# artemis_board.net
KiCad netlist of a schematic drawn in EAGLE
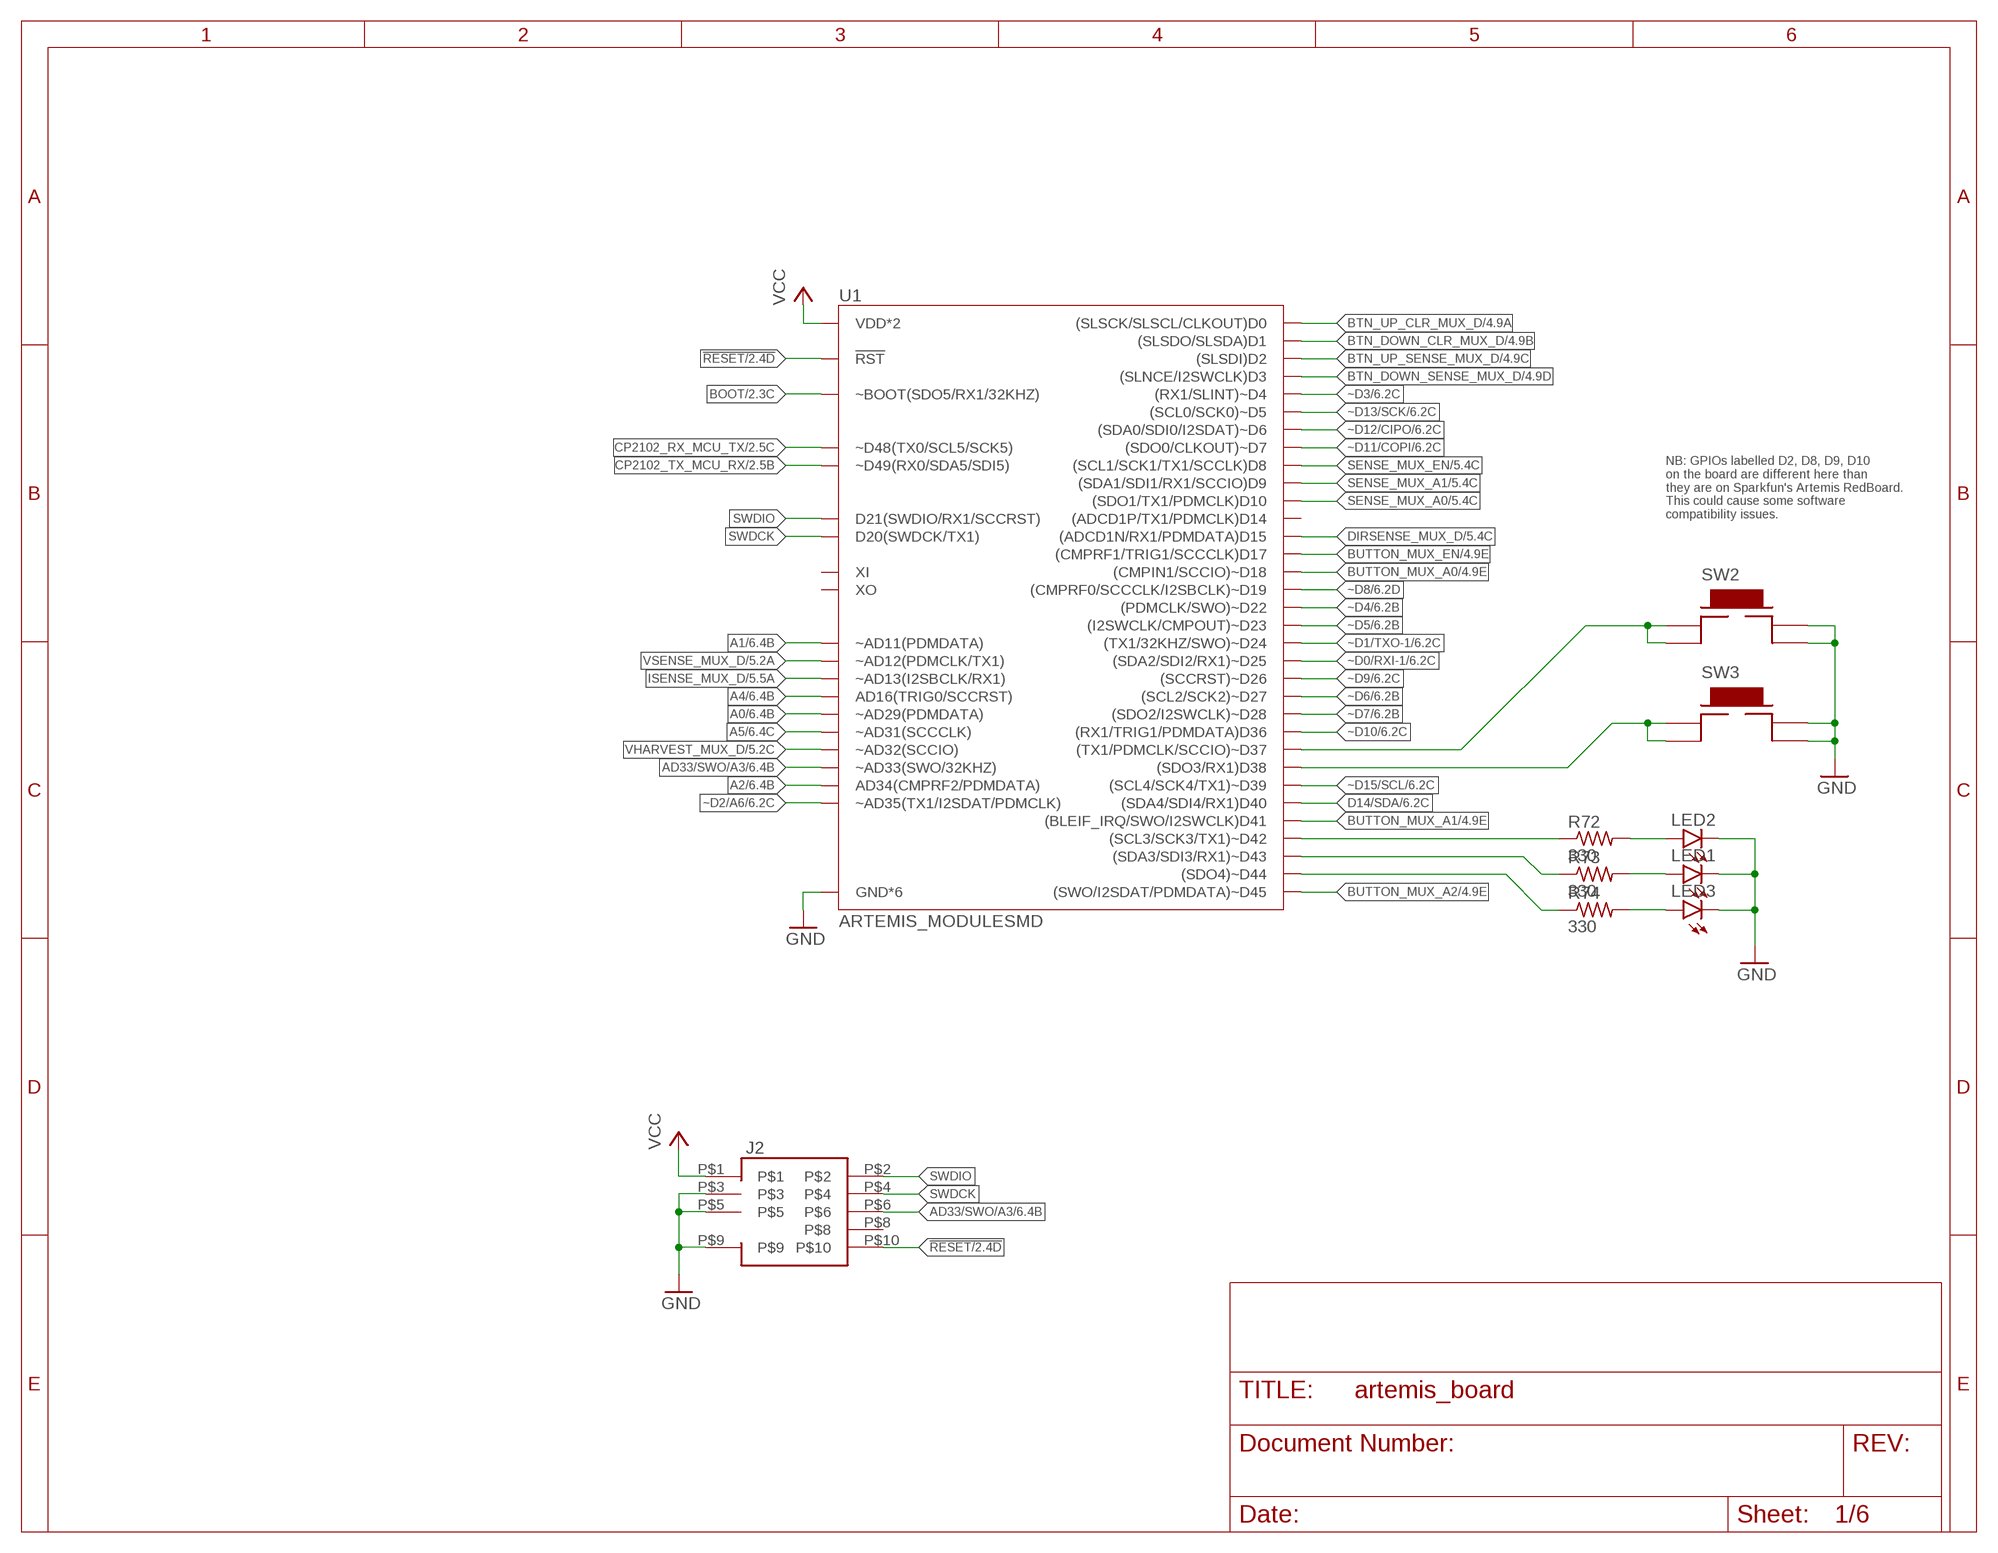
[diagram p0: schematic, sheet 1]
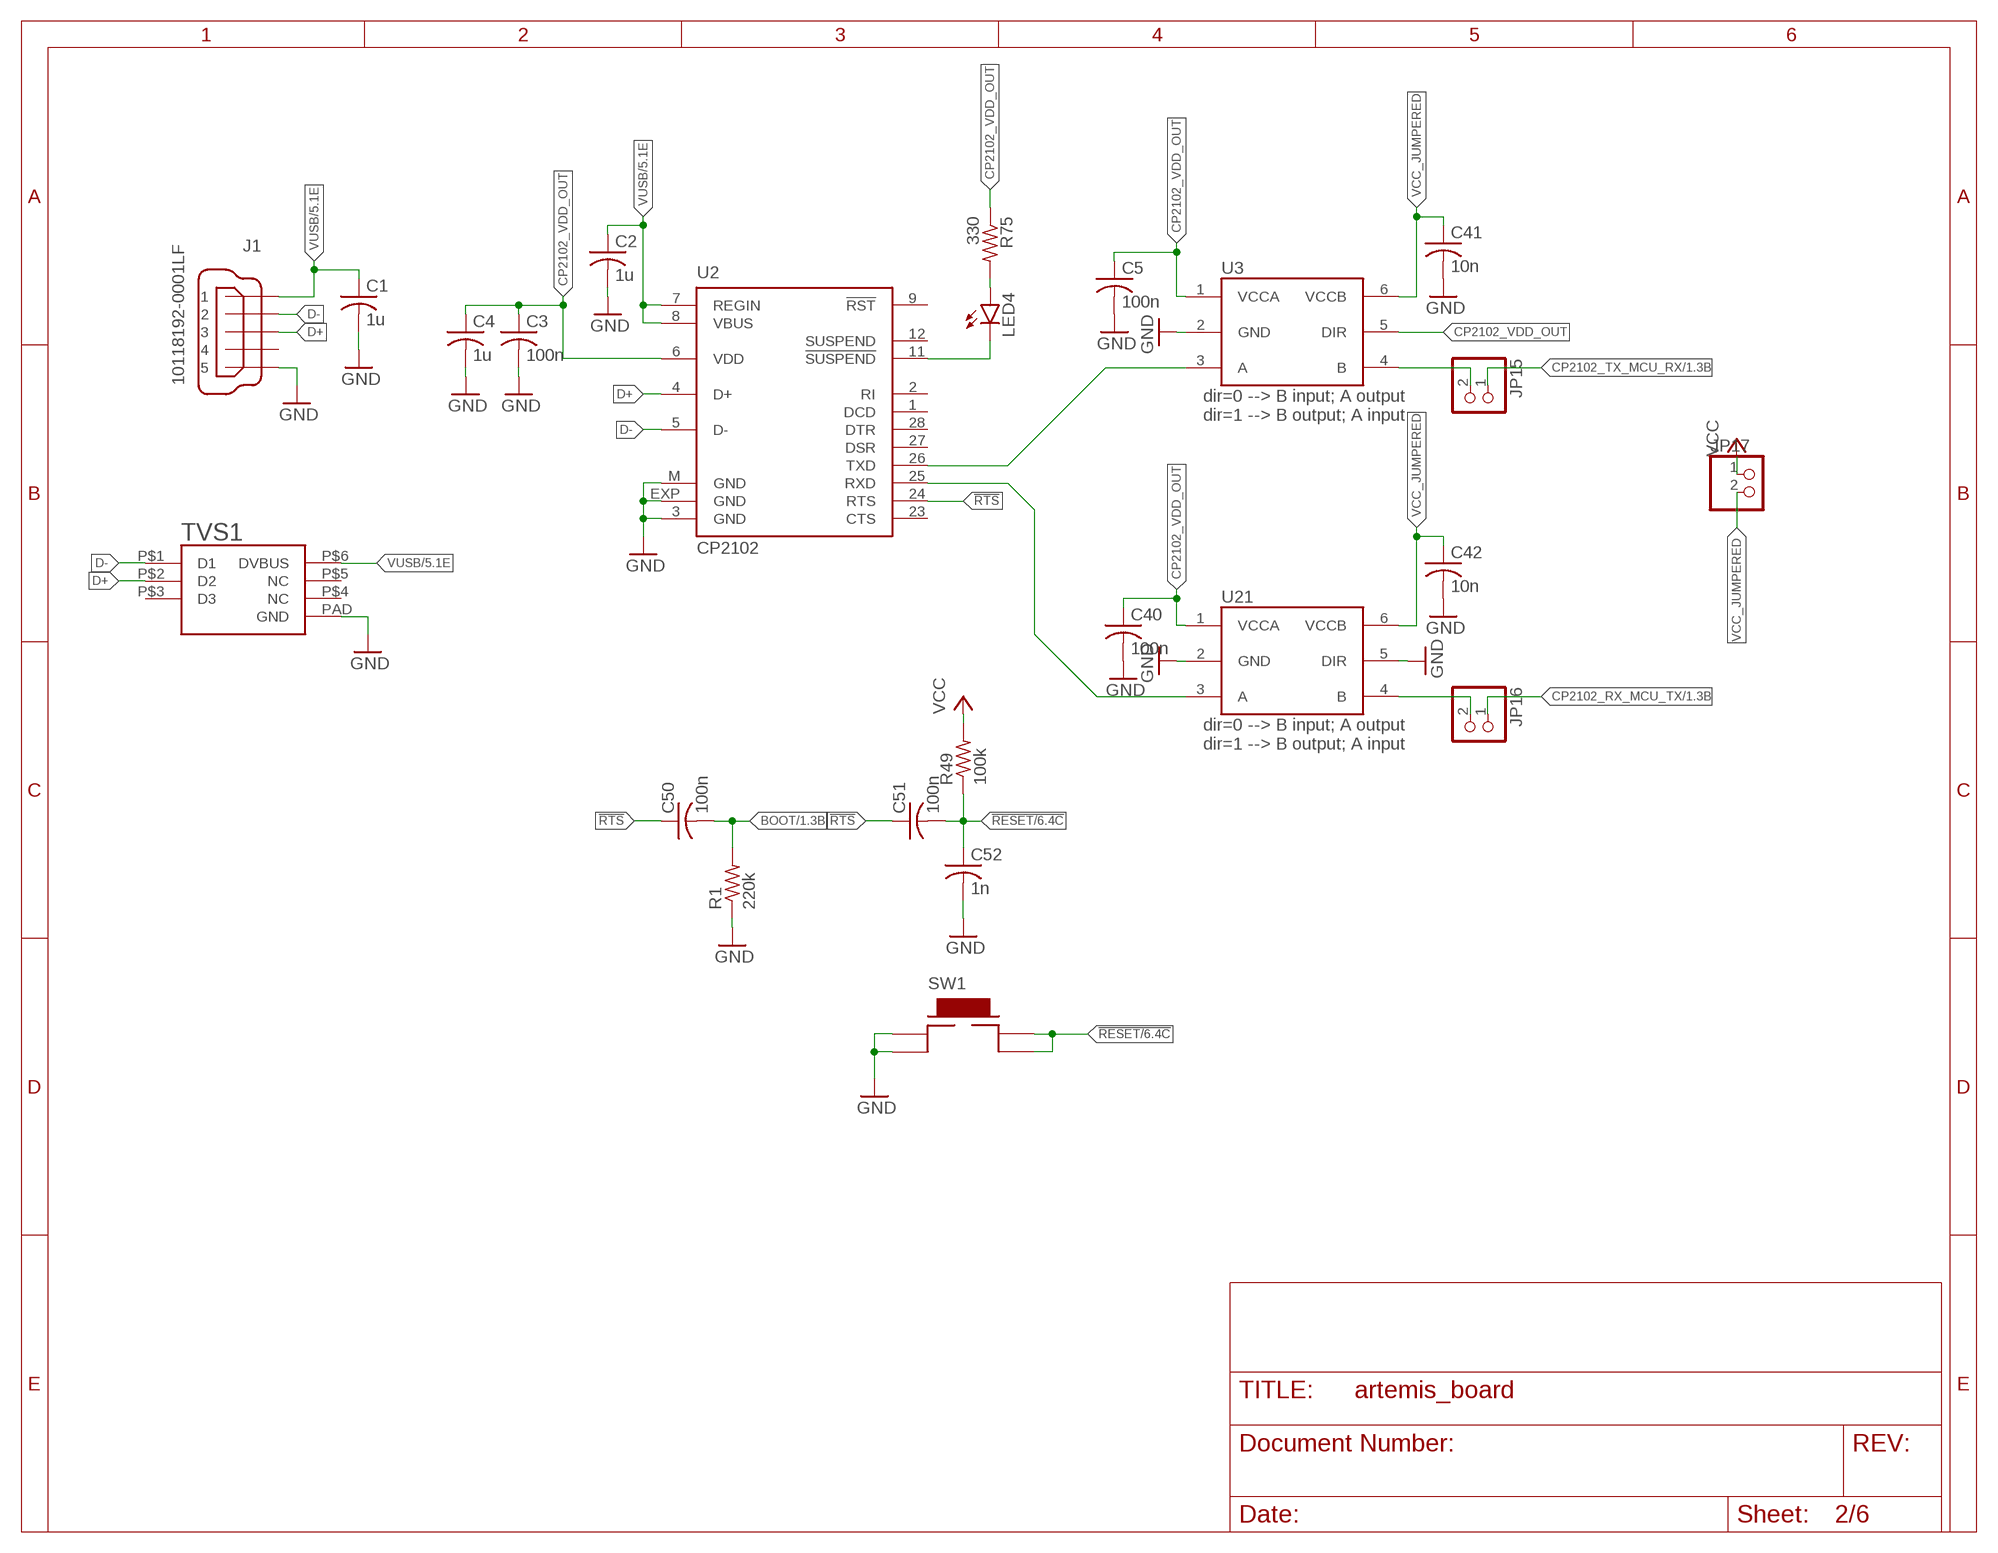
[diagram p1: schematic, sheet 2]
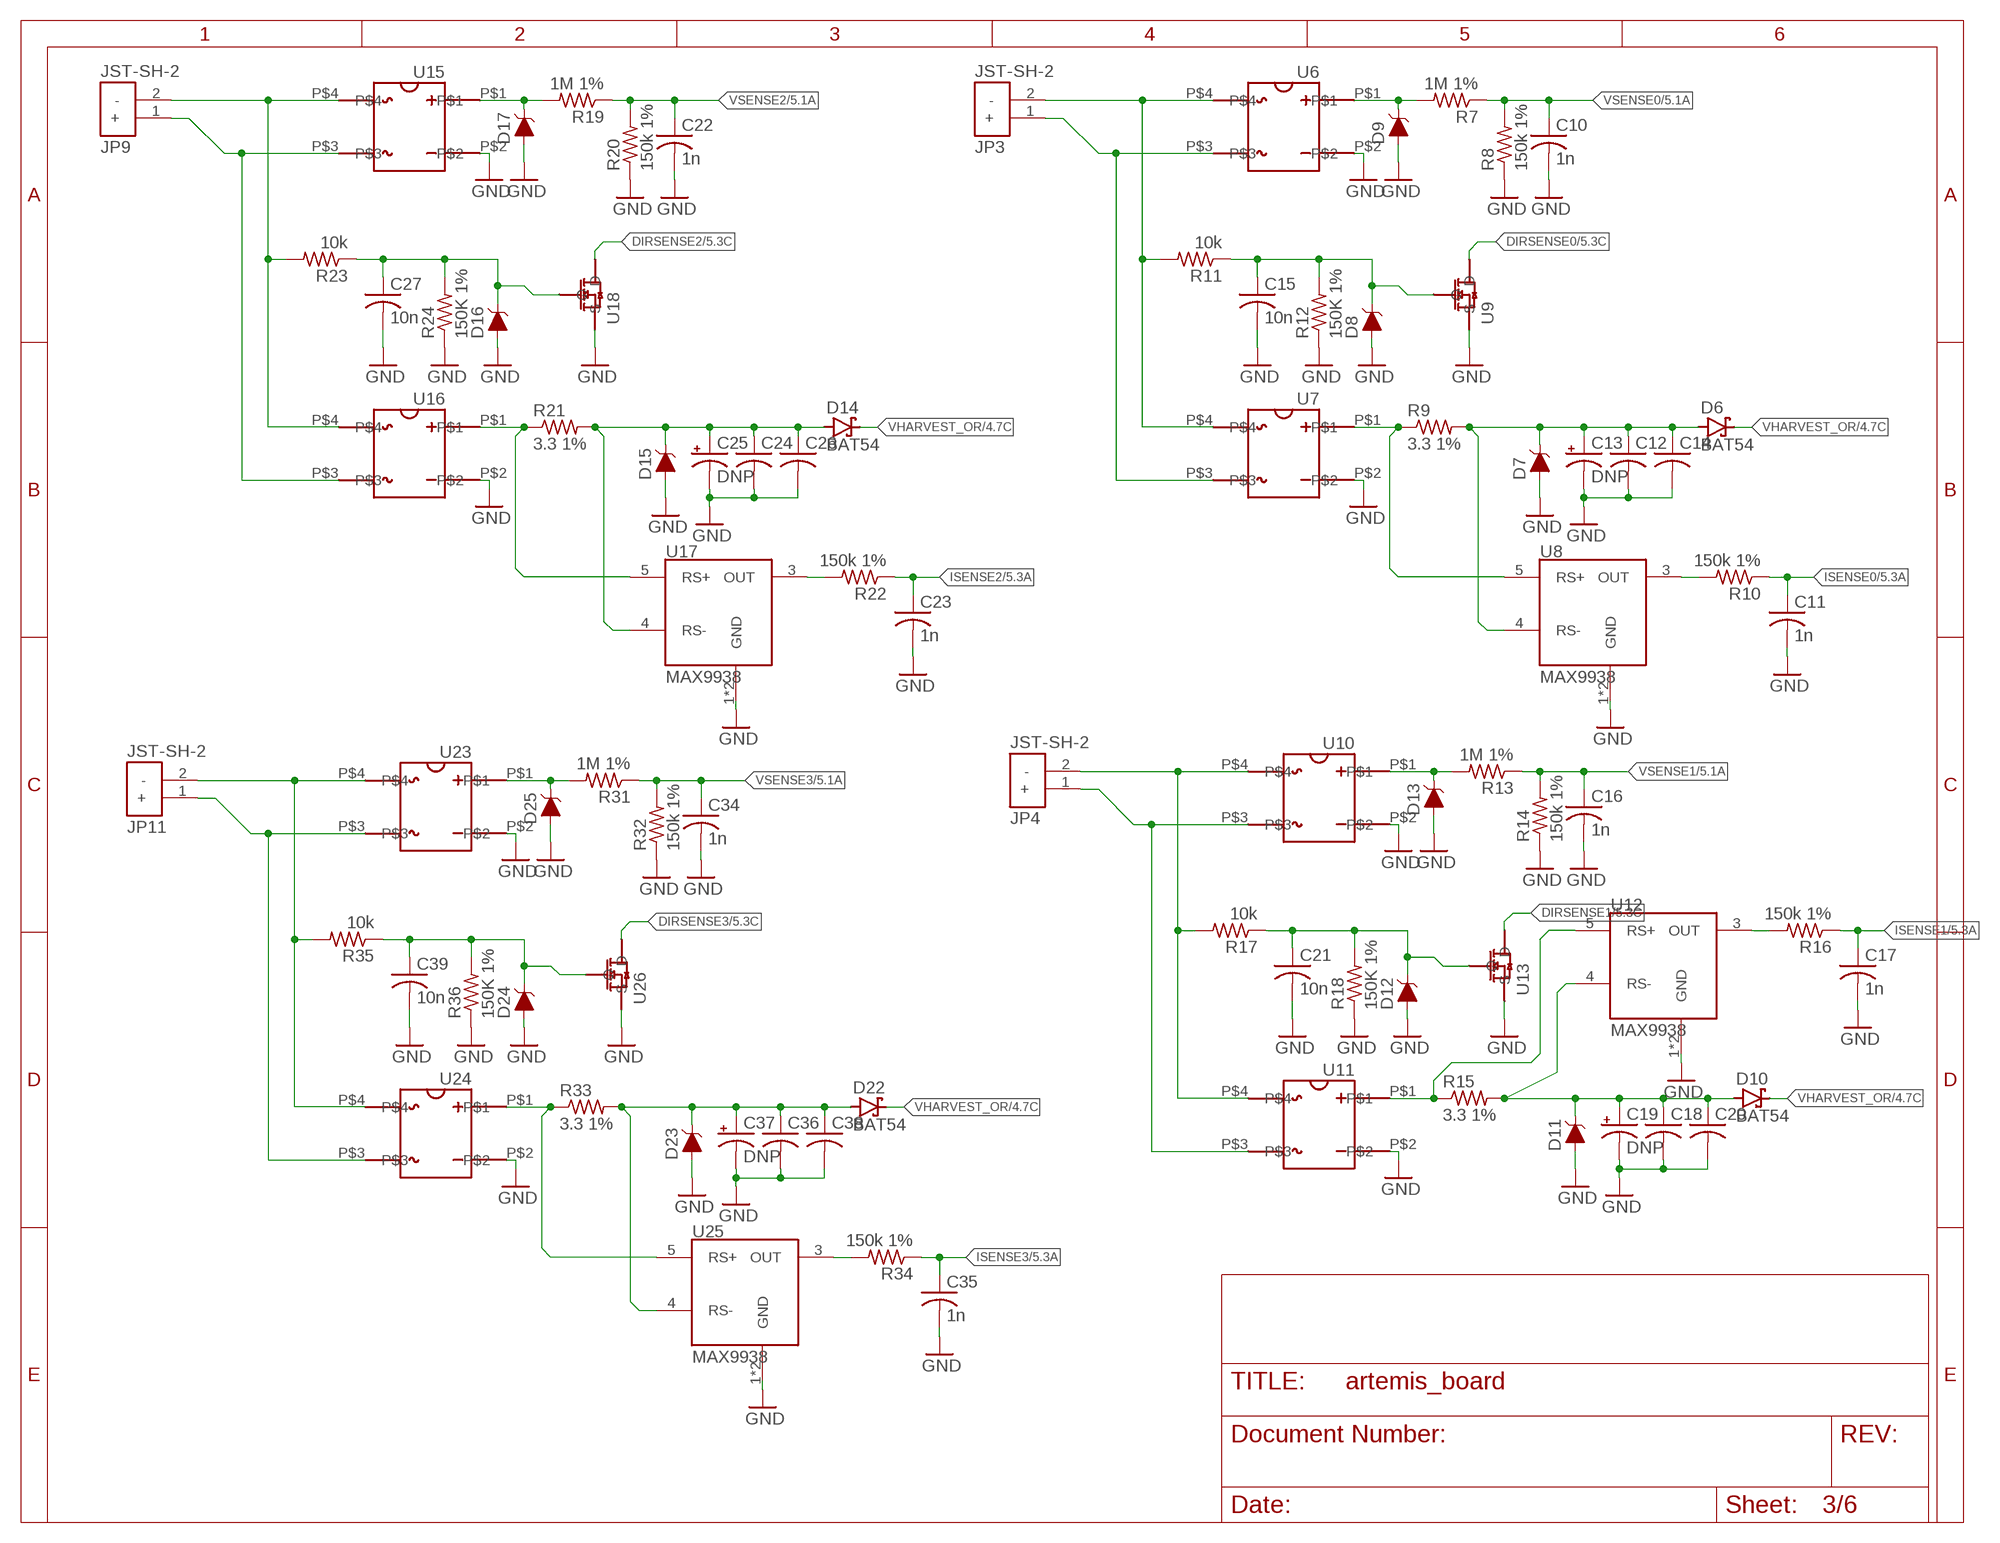
[diagram p2: schematic, sheet 3]
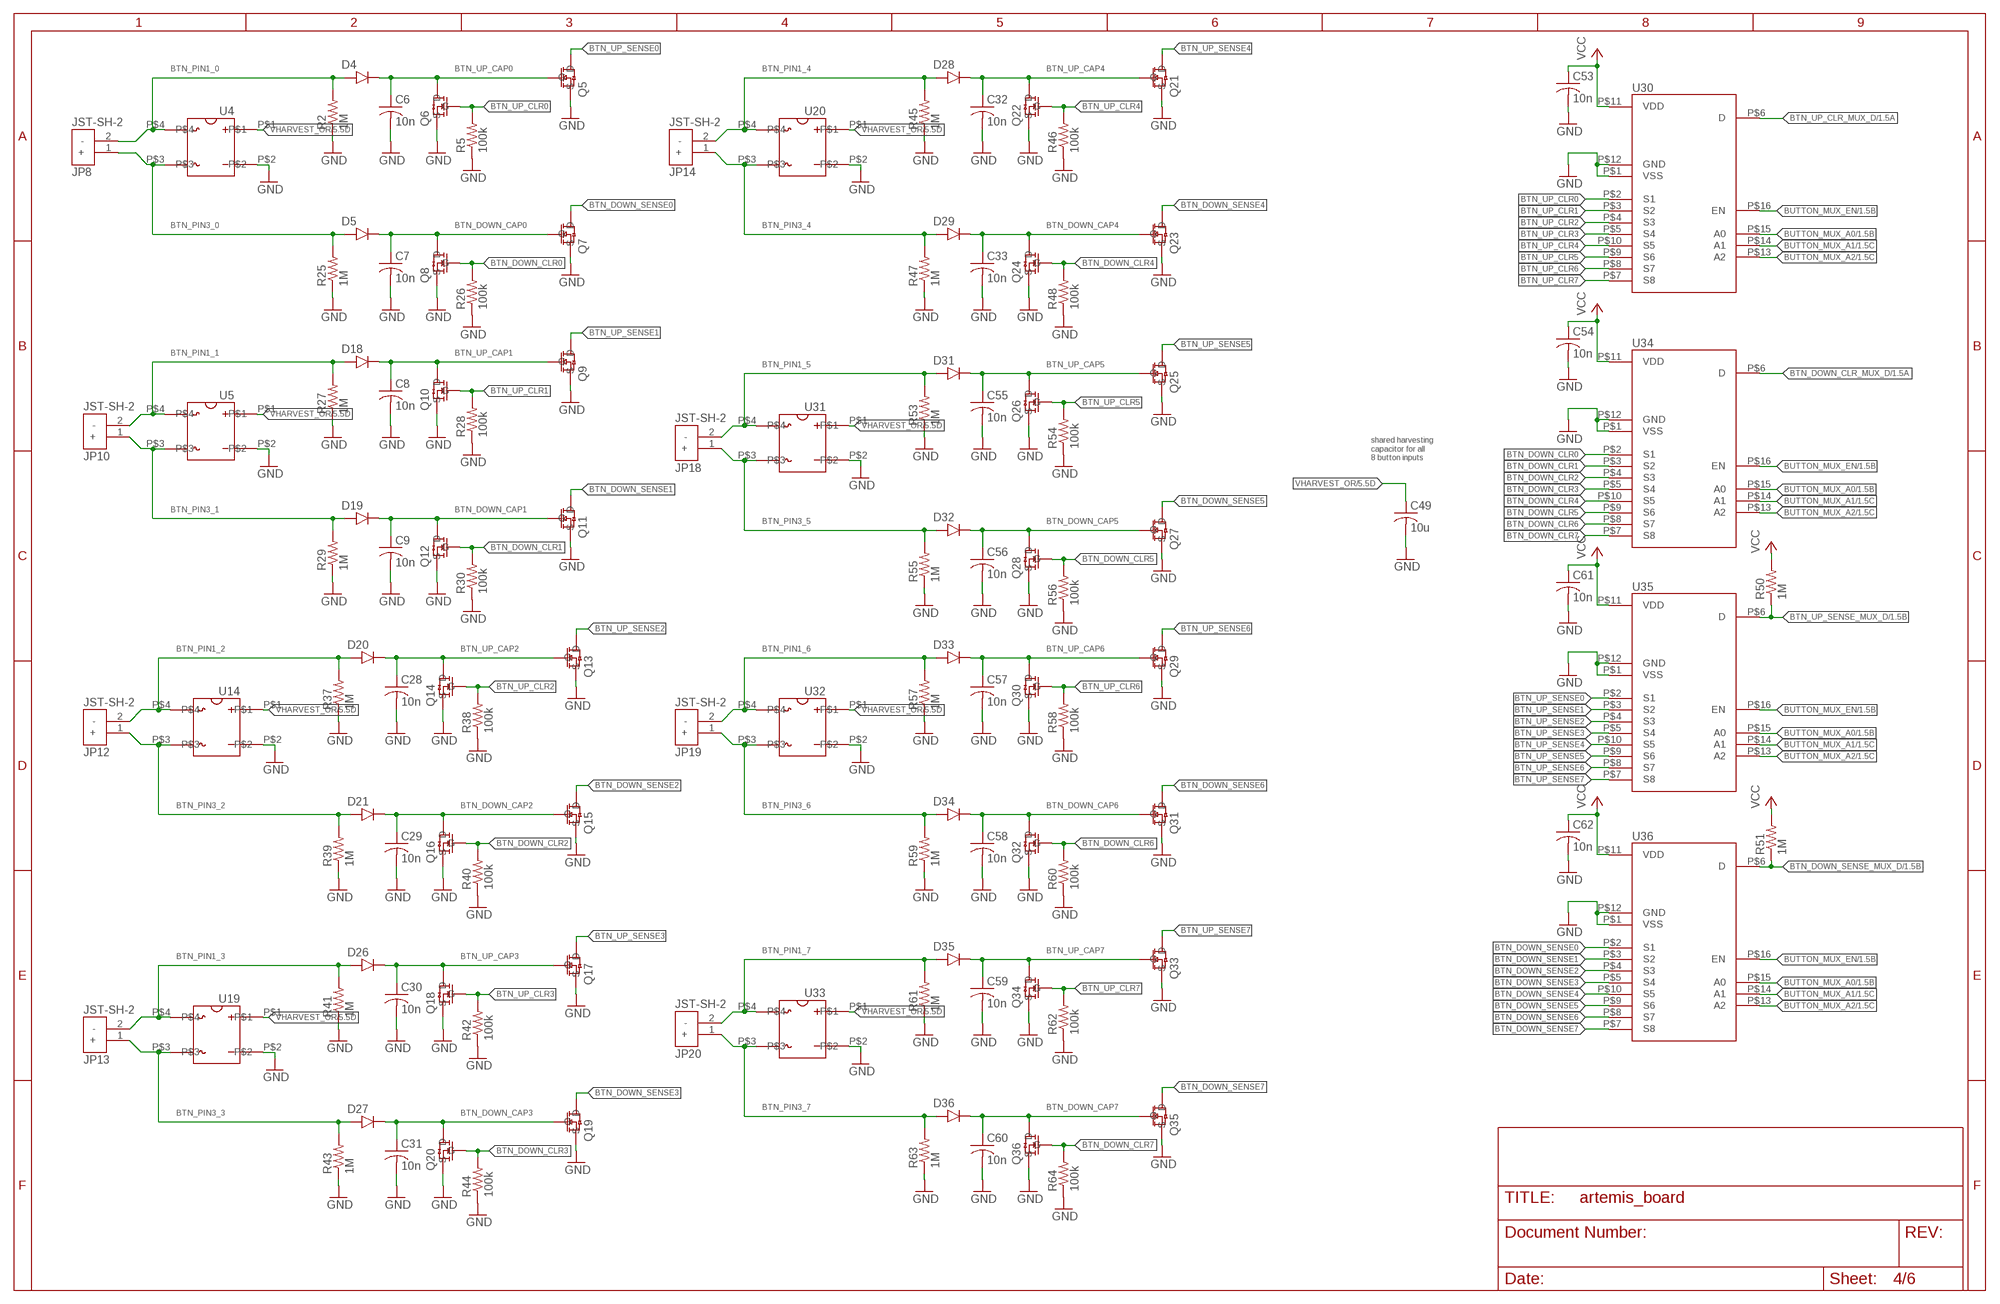
[diagram p3: schematic, sheet 4]
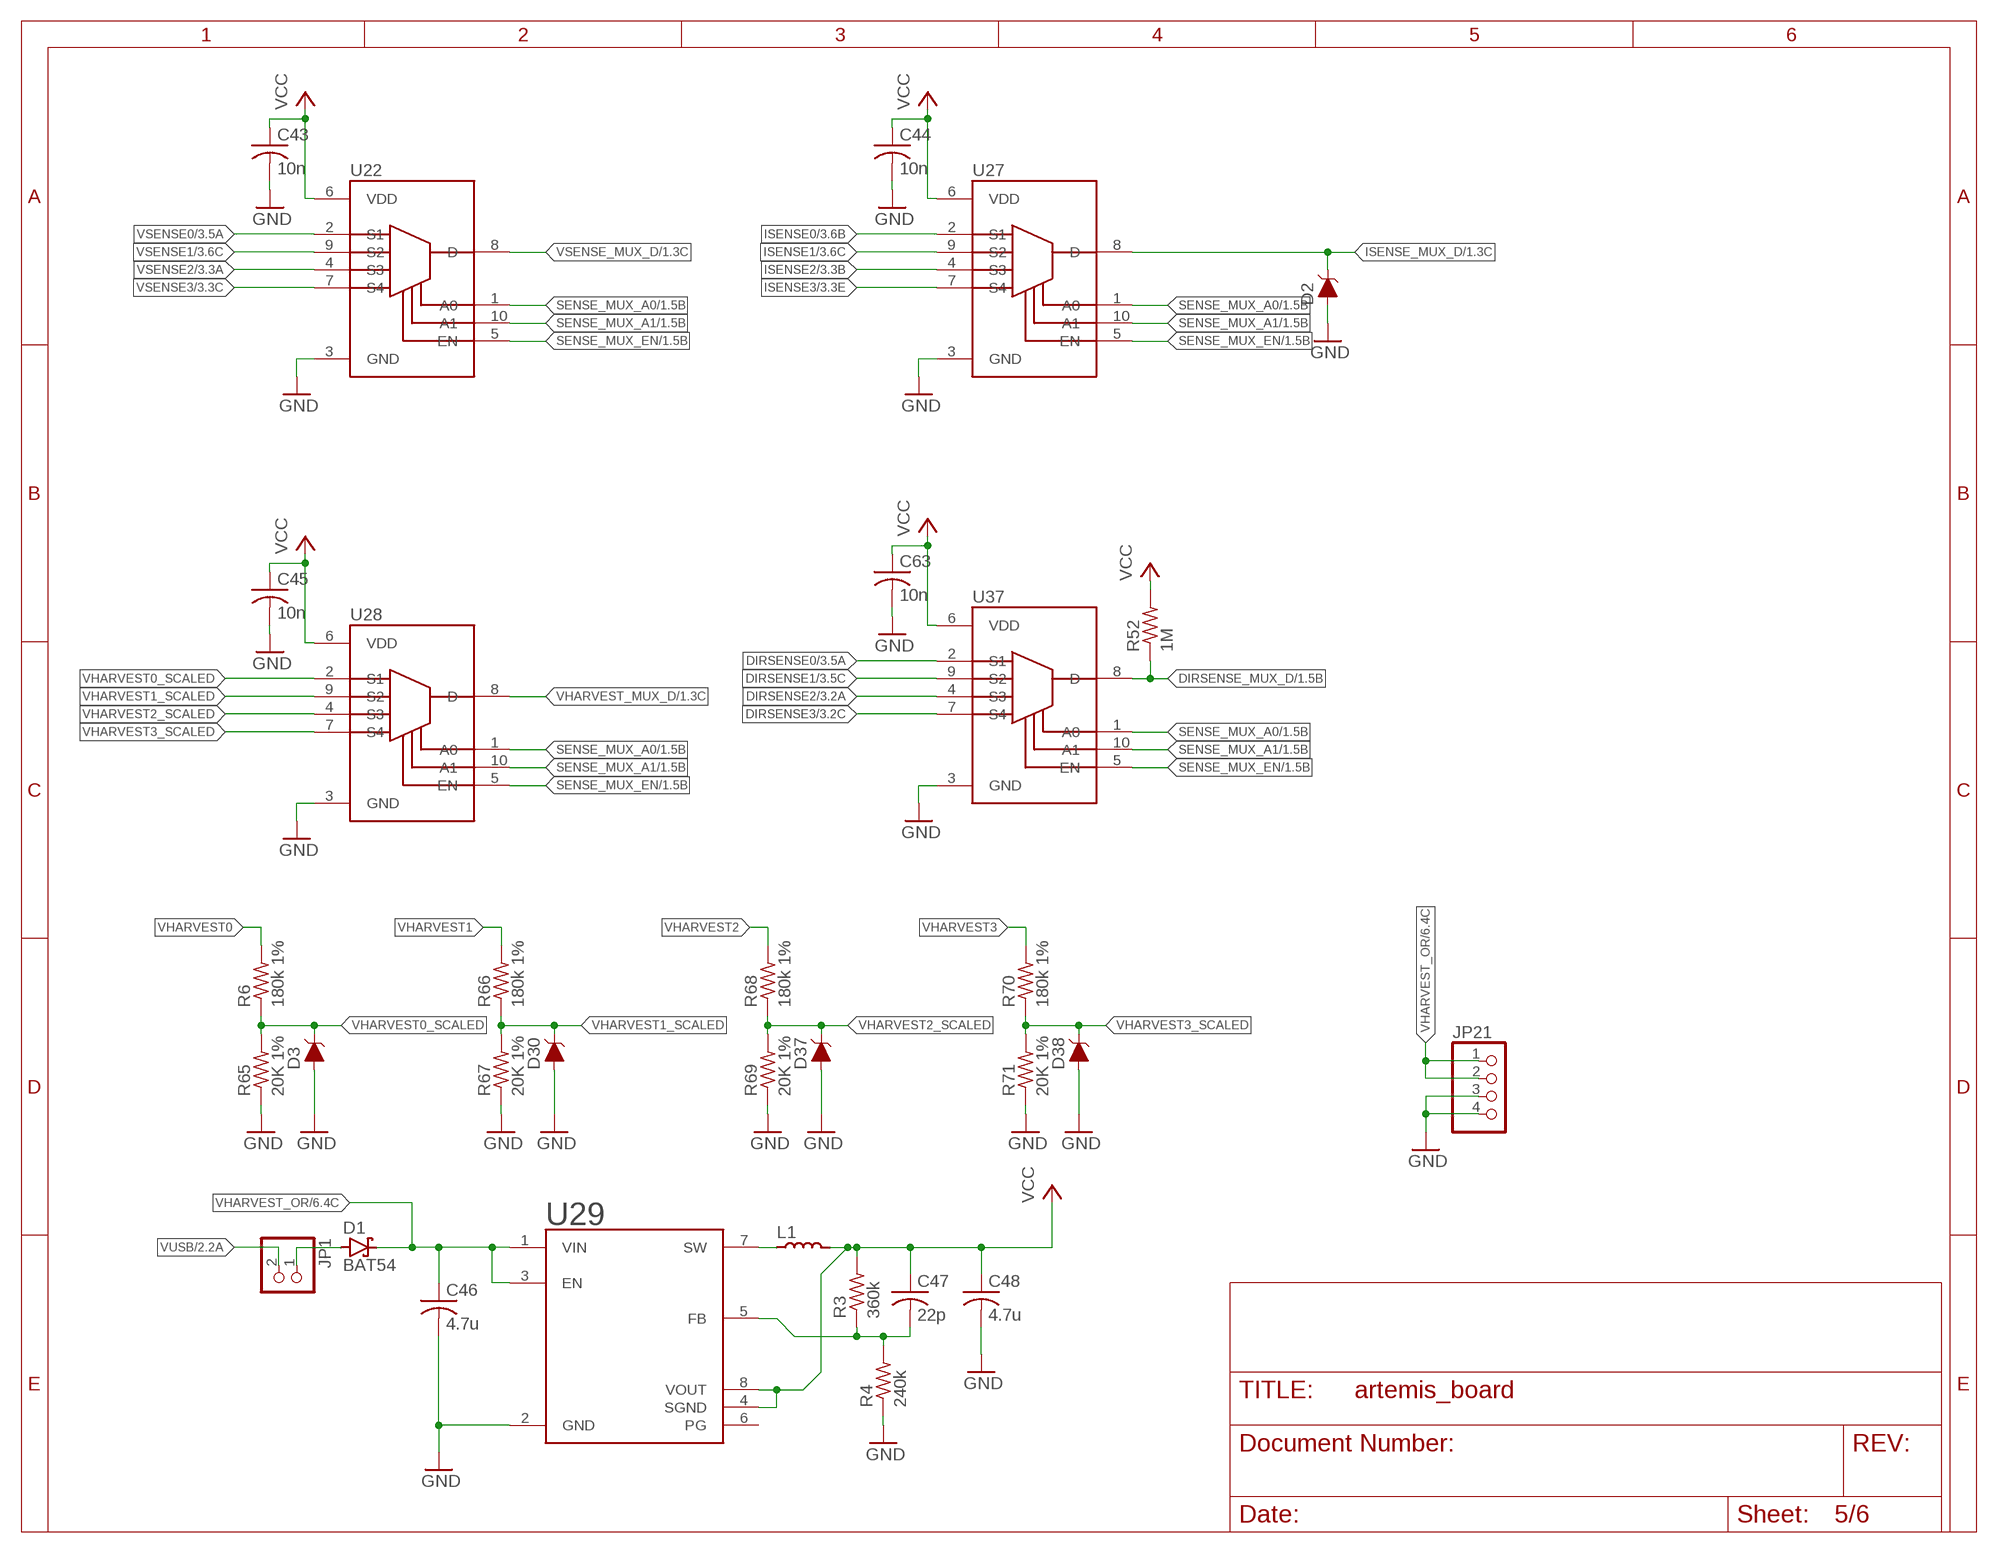
[diagram p4: schematic, sheet 5]
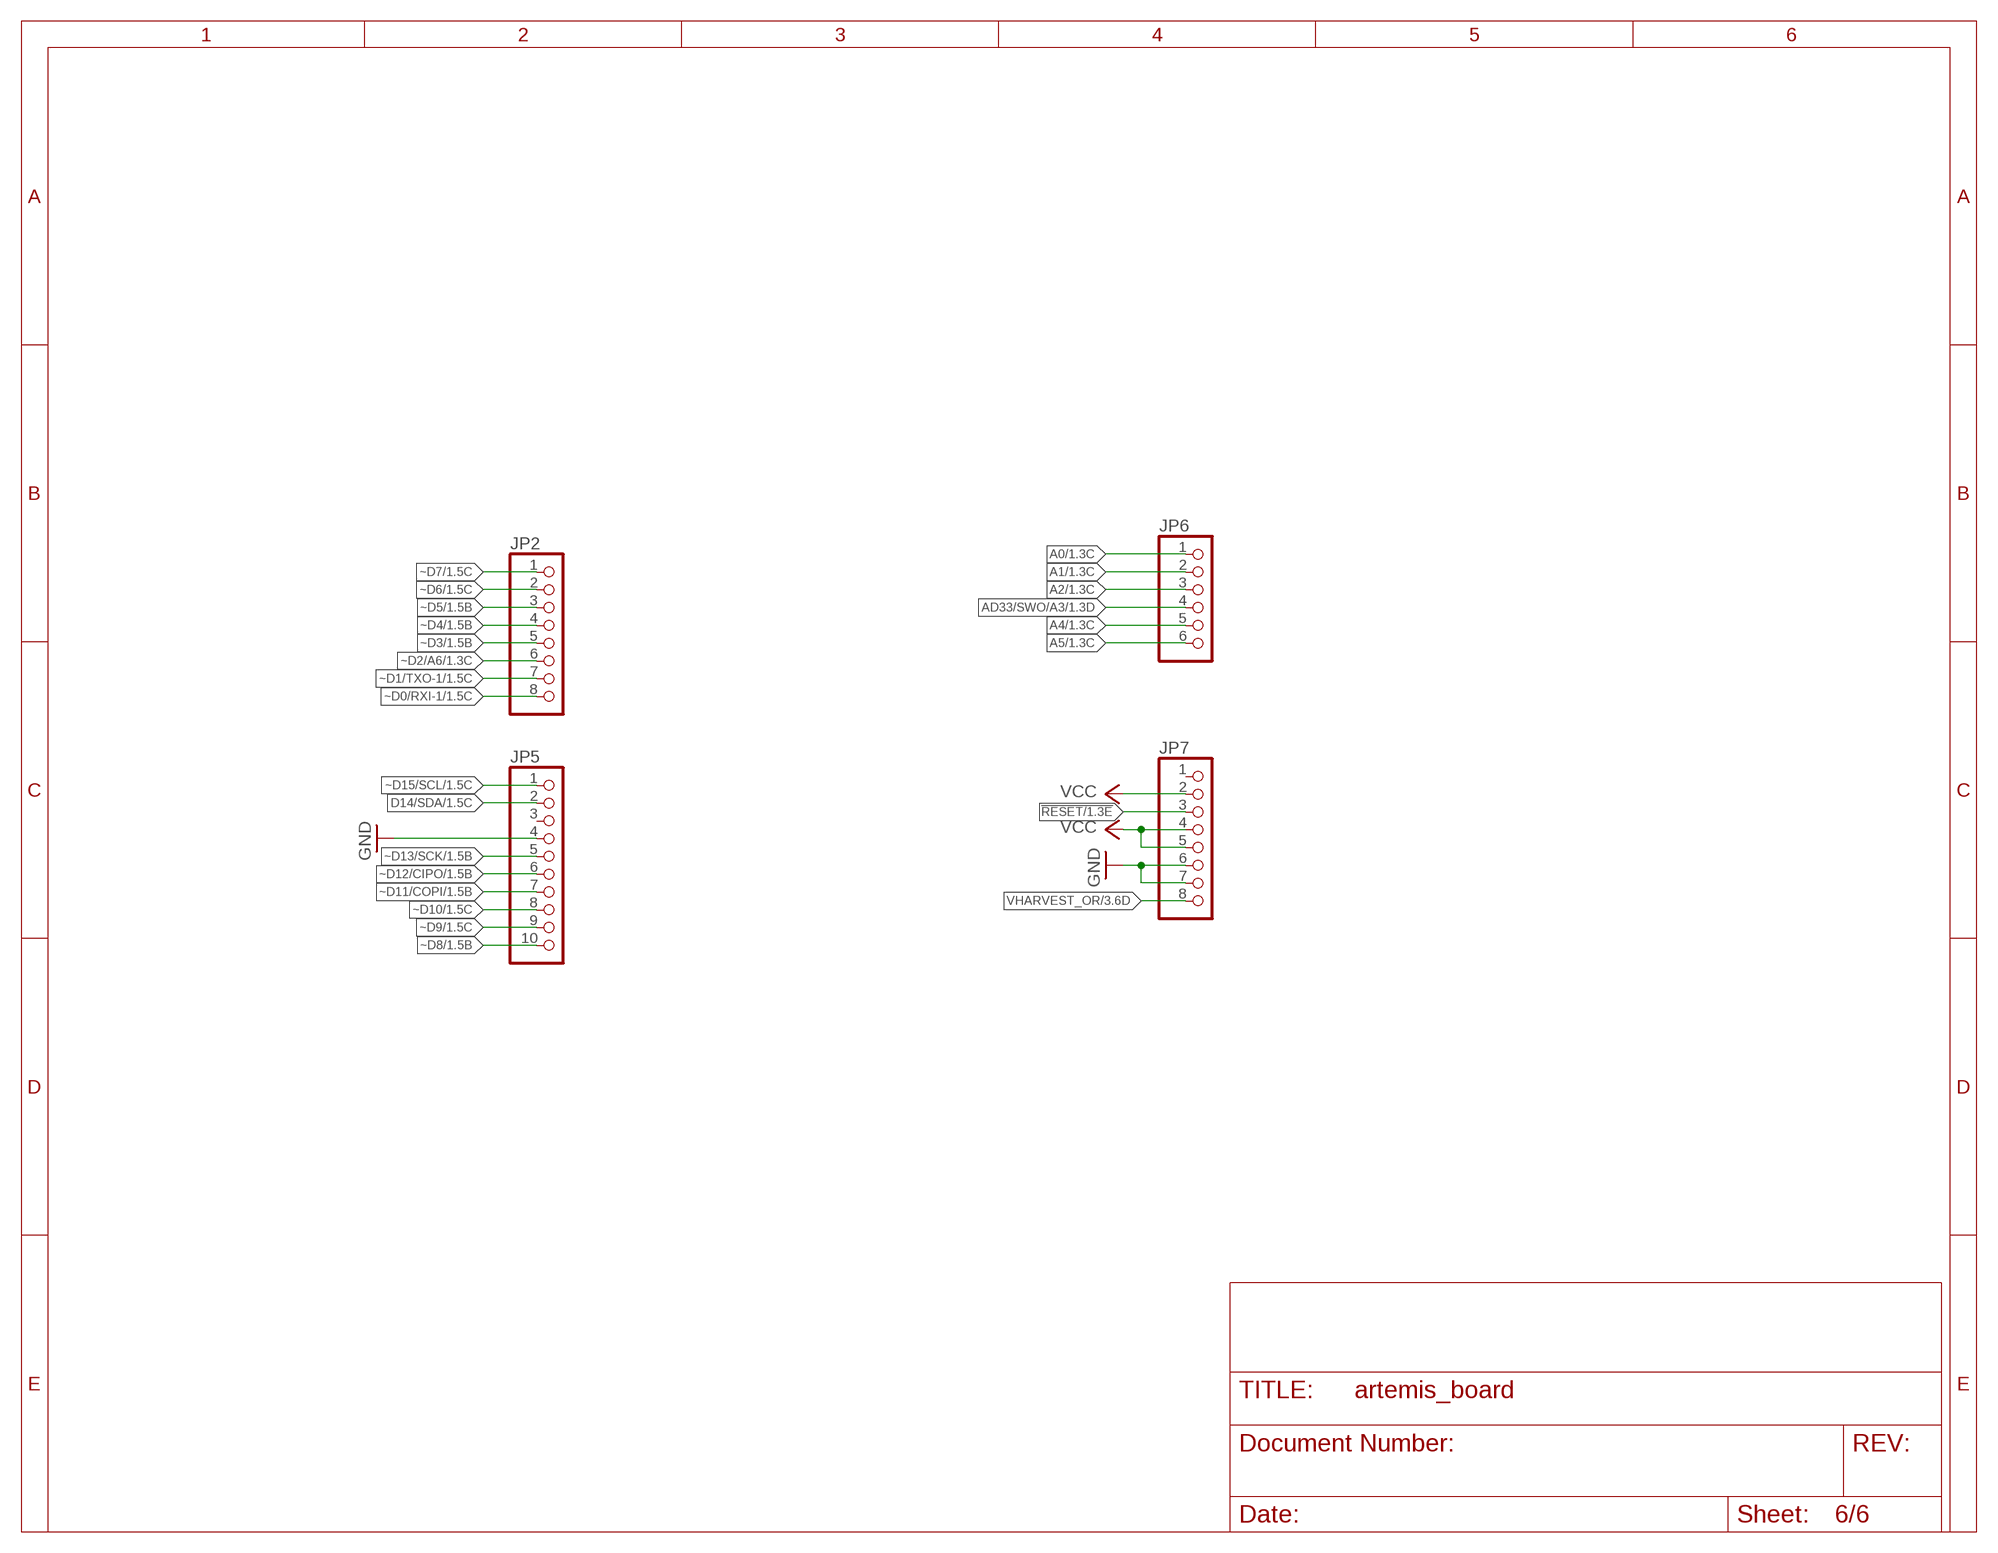
[diagram p5: schematic, sheet 6]

(export (version "E")
  (design (tool "Eeschema 10.0.6"))
  (components
    (comp (ref "C1")
      (value "1u")
      (footprint "eagle-import:C0402")
      (fields (field (name "MFR") "SAMSUNG"))
      (libsource (lib "eagle-import") (part "C-USC0402"))
    )
    (comp (ref "C2")
      (value "1u")
      (footprint "eagle-import:C0402")
      (fields (field (name "MFR") "SAMSUNG"))
      (libsource (lib "eagle-import") (part "C-USC0402"))
    )
    (comp (ref "C3")
      (value "100n")
      (footprint "eagle-import:C0402")
      (fields (field (name "MFR") "SAMSUNG"))
      (libsource (lib "eagle-import") (part "C-USC0402"))
    )
    (comp (ref "C4")
      (value "1u")
      (footprint "eagle-import:C0402")
      (fields (field (name "MFR") "SAMSUNG"))
      (libsource (lib "eagle-import") (part "C-USC0402"))
    )
    (comp (ref "C5")
      (value "100n")
      (footprint "eagle-import:C0402")
      (fields (field (name "MFR") "SAMSUNG"))
      (libsource (lib "eagle-import") (part "C-USC0402"))
    )
    (comp (ref "C40")
      (value "100n")
      (footprint "eagle-import:C0402")
      (fields (field (name "MFR") "SAMSUNG"))
      (libsource (lib "eagle-import") (part "C-USC0402"))
    )
    (comp (ref "C41")
      (value "10n")
      (footprint "eagle-import:C0402")
      (fields (field (name "MFR") "SAMSUNG"))
      (libsource (lib "eagle-import") (part "C-USC0402"))
    )
    (comp (ref "C42")
      (value "10n")
      (footprint "eagle-import:C0402")
      (fields (field (name "MFR") "SAMSUNG"))
      (libsource (lib "eagle-import") (part "C-USC0402"))
    )
    (comp (ref "C50")
      (value "100n")
      (footprint "eagle-import:C0402")
      (fields (field (name "MFR") "SAMSUNG"))
      (libsource (lib "eagle-import") (part "C-USC0402"))
    )
    (comp (ref "C51")
      (value "100n")
      (footprint "eagle-import:C0402")
      (fields (field (name "MFR") "SAMSUNG"))
      (libsource (lib "eagle-import") (part "C-USC0402"))
    )
    (comp (ref "C52")
      (value "1n")
      (footprint "eagle-import:C0402")
      (fields (field (name "MFR") "SAMSUNG"))
      (libsource (lib "eagle-import") (part "C-USC0402"))
    )
    (comp (ref "J1")
      (value "10118192-0001LF")
      (footprint "eagle-import:10118192-0001LF")
      (fields (field (name "MFR") "Amphenol ICC (FCI)"))
      (libsource (lib "eagle-import") (part "10118192-0001LF"))
    )
    (comp (ref "JP15")
      (value "PINHD-1X2")
      (footprint "eagle-import:1X02")
      (libsource (lib "eagle-import") (part "PINHD-1X2"))
    )
    (comp (ref "JP16")
      (value "PINHD-1X2")
      (footprint "eagle-import:1X02")
      (libsource (lib "eagle-import") (part "PINHD-1X2"))
    )
    (comp (ref "JP17")
      (value "PINHD-1X2")
      (footprint "eagle-import:1X02")
      (libsource (lib "eagle-import") (part "PINHD-1X2"))
    )
    (comp (ref "LED4")
      (value "LEDCHIP-LED0603")
      (footprint "eagle-import:CHIP-LED0603")
      (fields (field (name "MFR") "stanley electric co"))
      (libsource (lib "eagle-import") (part "LEDCHIP-LED0603"))
    )
    (comp (ref "R1")
      (value "220k")
      (footprint "eagle-import:R0402")
      (fields (field (name "MFR") "yageo"))
      (libsource (lib "eagle-import") (part "R-US_R0402"))
    )
    (comp (ref "R49")
      (value "100k")
      (footprint "eagle-import:R0402")
      (fields (field (name "MFR") "yageo"))
      (libsource (lib "eagle-import") (part "R-US_R0402"))
    )
    (comp (ref "R75")
      (value "330")
      (footprint "eagle-import:R0402")
      (fields (field (name "MFR") "yageo"))
      (libsource (lib "eagle-import") (part "R-US_R0402"))
    )
    (comp (ref "SW1")
      (value "TE_FSM4JSMA")
      (footprint "eagle-import:TE_FSMJSMA")
      (fields (field (name "MFR") "TE connectivity"))
      (libsource (lib "eagle-import") (part "TE_FSM4JSMA"))
    )
    (comp (ref "TVS1")
      (value "RCLAMP3654PAT")
      (footprint "eagle-import:RCLAMP3654PATCT")
      (fields (field (name "MFR") "SEMTECH"))
      (libsource (lib "eagle-import") (part "RCLAMP3654PAT"))
    )
    (comp (ref "U2")
      (value "CP2102")
      (footprint "eagle-import:MLP28")
      (fields (field (name "MF") "FARNELL") (field (name "MPN") "CP2102-GM"))
      (libsource (lib "eagle-import") (part "CP2102"))
    )
    (comp (ref "U3")
      (value "74AXP1T45GWH")
      (footprint "eagle-import:SOT65P210X110-6N")
      (fields (field (name "MFR") "NEXPERIA"))
      (libsource (lib "eagle-import") (part "74AXP1T45GWH"))
    )
    (comp (ref "U21")
      (value "74AXP1T45GWH")
      (footprint "eagle-import:SOT65P210X110-6N")
      (fields (field (name "MFR") "NEXPERIA"))
      (libsource (lib "eagle-import") (part "74AXP1T45GWH"))
    )
    (comp (ref "C10")
      (value "1n")
      (footprint "eagle-import:C0402")
      (fields (field (name "MFR") "SAMSUNG"))
      (libsource (lib "eagle-import") (part "C-USC0402"))
    )
    (comp (ref "C11")
      (value "1n")
      (footprint "eagle-import:C0402")
      (fields (field (name "MFR") "SAMSUNG"))
      (libsource (lib "eagle-import") (part "C-USC0402"))
    )
    (comp (ref "C12")
      (value "C-USC1206")
      (footprint "eagle-import:C1206")
      (fields (field (name "MFR") "TDK"))
      (libsource (lib "eagle-import") (part "C-USC1206"))
    )
    (comp (ref "C13")
      (value "DNP")
      (footprint "eagle-import:E2,5-5")
      (libsource (lib "eagle-import") (part "CPOL-USE2.5-5"))
    )
    (comp (ref "C14")
      (value "C-USC1206")
      (footprint "eagle-import:C1206")
      (fields (field (name "MFR") "TDK"))
      (libsource (lib "eagle-import") (part "C-USC1206"))
    )
    (comp (ref "C15")
      (value "10n")
      (footprint "eagle-import:C0402")
      (fields (field (name "MFR") "SAMSUNG"))
      (libsource (lib "eagle-import") (part "C-USC0402"))
    )
    (comp (ref "C16")
      (value "1n")
      (footprint "eagle-import:C0402")
      (fields (field (name "MFR") "SAMSUNG"))
      (libsource (lib "eagle-import") (part "C-USC0402"))
    )
    (comp (ref "C17")
      (value "1n")
      (footprint "eagle-import:C0402")
      (fields (field (name "MFR") "SAMSUNG"))
      (libsource (lib "eagle-import") (part "C-USC0402"))
    )
    (comp (ref "C18")
      (value "C-USC1206")
      (footprint "eagle-import:C1206")
      (fields (field (name "MFR") "TDK"))
      (libsource (lib "eagle-import") (part "C-USC1206"))
    )
    (comp (ref "C19")
      (value "DNP")
      (footprint "eagle-import:E2,5-5")
      (libsource (lib "eagle-import") (part "CPOL-USE2.5-5"))
    )
    (comp (ref "C20")
      (value "C-USC1206")
      (footprint "eagle-import:C1206")
      (fields (field (name "MFR") "TDK"))
      (libsource (lib "eagle-import") (part "C-USC1206"))
    )
    (comp (ref "C21")
      (value "10n")
      (footprint "eagle-import:C0402")
      (fields (field (name "MFR") "SAMSUNG"))
      (libsource (lib "eagle-import") (part "C-USC0402"))
    )
    (comp (ref "C22")
      (value "1n")
      (footprint "eagle-import:C0402")
      (fields (field (name "MFR") "SAMSUNG"))
      (libsource (lib "eagle-import") (part "C-USC0402"))
    )
    (comp (ref "C23")
      (value "1n")
      (footprint "eagle-import:C0402")
      (fields (field (name "MFR") "SAMSUNG"))
      (libsource (lib "eagle-import") (part "C-USC0402"))
    )
    (comp (ref "C24")
      (value "C-USC1206")
      (footprint "eagle-import:C1206")
      (fields (field (name "MFR") "TDK"))
      (libsource (lib "eagle-import") (part "C-USC1206"))
    )
    (comp (ref "C25")
      (value "DNP")
      (footprint "eagle-import:E2,5-5")
      (libsource (lib "eagle-import") (part "CPOL-USE2.5-5"))
    )
    (comp (ref "C26")
      (value "C-USC1206")
      (footprint "eagle-import:C1206")
      (fields (field (name "MFR") "TDK"))
      (libsource (lib "eagle-import") (part "C-USC1206"))
    )
    (comp (ref "C27")
      (value "10n")
      (footprint "eagle-import:C0402")
      (fields (field (name "MFR") "SAMSUNG"))
      (libsource (lib "eagle-import") (part "C-USC0402"))
    )
    (comp (ref "C34")
      (value "1n")
      (footprint "eagle-import:C0402")
      (fields (field (name "MFR") "SAMSUNG"))
      (libsource (lib "eagle-import") (part "C-USC0402"))
    )
    (comp (ref "C35")
      (value "1n")
      (footprint "eagle-import:C0402")
      (fields (field (name "MFR") "SAMSUNG"))
      (libsource (lib "eagle-import") (part "C-USC0402"))
    )
    (comp (ref "C36")
      (value "C-USC1206")
      (footprint "eagle-import:C1206")
      (fields (field (name "MFR") "TDK"))
      (libsource (lib "eagle-import") (part "C-USC1206"))
    )
    (comp (ref "C37")
      (value "DNP")
      (footprint "eagle-import:E2,5-5")
      (libsource (lib "eagle-import") (part "CPOL-USE2.5-5"))
    )
    (comp (ref "C38")
      (value "C-USC1206")
      (footprint "eagle-import:C1206")
      (fields (field (name "MFR") "TDK"))
      (libsource (lib "eagle-import") (part "C-USC1206"))
    )
    (comp (ref "C39")
      (value "10n")
      (footprint "eagle-import:C0402")
      (fields (field (name "MFR") "SAMSUNG"))
      (libsource (lib "eagle-import") (part "C-USC0402"))
    )
    (comp (ref "D6")
      (value "BAT54")
      (footprint "eagle-import:SOT23")
      (fields (field (name "MFR") "ON"))
      (libsource (lib "eagle-import") (part "BAT54"))
    )
    (comp (ref "D7")
      (value "3.3V")
      (footprint "eagle-import:SOD-323")
      (fields (field (name "MFR") "DIODES_INCORPORATED"))
      (libsource (lib "eagle-import") (part "DIODE-ZENER-MM3Z3V3T1G"))
    )
    (comp (ref "D8")
      (value "3.3V")
      (footprint "eagle-import:SOD-323")
      (fields (field (name "MFR") "diodes incorporated"))
      (libsource (lib "eagle-import") (part "DIODE-ZENER-MM3Z3V3T1G"))
    )
    (comp (ref "D9")
      (value "3.3V")
      (footprint "eagle-import:SOD-323")
      (fields (field (name "MFR") "DIODES_INCORPORATED"))
      (libsource (lib "eagle-import") (part "DIODE-ZENER-MM3Z3V3T1G"))
    )
    (comp (ref "D10")
      (value "BAT54")
      (footprint "eagle-import:SOT23")
      (fields (field (name "MFR") "ON"))
      (libsource (lib "eagle-import") (part "BAT54"))
    )
    (comp (ref "D11")
      (value "3.3V")
      (footprint "eagle-import:SOD-323")
      (fields (field (name "MFR") "DIODES_INCORPORATED"))
      (libsource (lib "eagle-import") (part "DIODE-ZENER-MM3Z3V3T1G"))
    )
    (comp (ref "D12")
      (value "3.3V")
      (footprint "eagle-import:SOD-323")
      (fields (field (name "MFR") "diodes incorporated"))
      (libsource (lib "eagle-import") (part "DIODE-ZENER-MM3Z3V3T1G"))
    )
    (comp (ref "D13")
      (value "3.3V")
      (footprint "eagle-import:SOD-323")
      (fields (field (name "MFR") "DIODES_INCORPORATED"))
      (libsource (lib "eagle-import") (part "DIODE-ZENER-MM3Z3V3T1G"))
    )
    (comp (ref "D14")
      (value "BAT54")
      (footprint "eagle-import:SOT23")
      (fields (field (name "MFR") "ON"))
      (libsource (lib "eagle-import") (part "BAT54"))
    )
    (comp (ref "D15")
      (value "3.3V")
      (footprint "eagle-import:SOD-323")
      (fields (field (name "MFR") "DIODES_INCORPORATED"))
      (libsource (lib "eagle-import") (part "DIODE-ZENER-MM3Z3V3T1G"))
    )
    (comp (ref "D16")
      (value "3.3V")
      (footprint "eagle-import:SOD-323")
      (fields (field (name "MFR") "diodes incorporated"))
      (libsource (lib "eagle-import") (part "DIODE-ZENER-MM3Z3V3T1G"))
    )
    (comp (ref "D17")
      (value "3.3V")
      (footprint "eagle-import:SOD-323")
      (fields (field (name "MFR") "DIODES_INCORPORATED"))
      (libsource (lib "eagle-import") (part "DIODE-ZENER-MM3Z3V3T1G"))
    )
    (comp (ref "D22")
      (value "BAT54")
      (footprint "eagle-import:SOT23")
      (fields (field (name "MFR") "ON"))
      (libsource (lib "eagle-import") (part "BAT54"))
    )
    (comp (ref "D23")
      (value "3.3V")
      (footprint "eagle-import:SOD-323")
      (fields (field (name "MFR") "DIODES_INCORPORATED"))
      (libsource (lib "eagle-import") (part "DIODE-ZENER-MM3Z3V3T1G"))
    )
    (comp (ref "D24")
      (value "3.3V")
      (footprint "eagle-import:SOD-323")
      (fields (field (name "MFR") "diodes incorporated"))
      (libsource (lib "eagle-import") (part "DIODE-ZENER-MM3Z3V3T1G"))
    )
    (comp (ref "D25")
      (value "3.3V")
      (footprint "eagle-import:SOD-323")
      (fields (field (name "MFR") "DIODES_INCORPORATED"))
      (libsource (lib "eagle-import") (part "DIODE-ZENER-MM3Z3V3T1G"))
    )
    (comp (ref "JP3")
      (value "JST-SH-2")
      (footprint "eagle-import:JST-SH-2")
      (fields (field (name "MFR") "jst"))
      (libsource (lib "eagle-import") (part "JST-SH-2"))
    )
    (comp (ref "JP4")
      (value "JST-SH-2")
      (footprint "eagle-import:JST-SH-2")
      (fields (field (name "MFR") "jst"))
      (libsource (lib "eagle-import") (part "JST-SH-2"))
    )
    (comp (ref "JP9")
      (value "JST-SH-2")
      (footprint "eagle-import:JST-SH-2")
      (fields (field (name "MFR") "jst"))
      (libsource (lib "eagle-import") (part "JST-SH-2"))
    )
    (comp (ref "JP11")
      (value "JST-SH-2")
      (footprint "eagle-import:JST-SH-2")
      (fields (field (name "MFR") "jst"))
      (libsource (lib "eagle-import") (part "JST-SH-2"))
    )
    (comp (ref "R7")
      (value "1M 1%")
      (footprint "eagle-import:R0402")
      (fields (field (name "MFR") "YAGEO"))
      (libsource (lib "eagle-import") (part "R-US_R0402"))
    )
    (comp (ref "R8")
      (value "150k 1%")
      (footprint "eagle-import:R0402")
      (fields (field (name "MFR") "YAGEO"))
      (libsource (lib "eagle-import") (part "R-US_R0402"))
    )
    (comp (ref "R9")
      (value "3.3 1%")
      (footprint "eagle-import:R0603")
      (fields (field (name "MFR") "PANASONIC"))
      (libsource (lib "eagle-import") (part "R-US_R0603"))
    )
    (comp (ref "R10")
      (value "150k 1%")
      (footprint "eagle-import:R0402")
      (fields (field (name "MFR") "YAGEO"))
      (libsource (lib "eagle-import") (part "R-US_R0402"))
    )
    (comp (ref "R11")
      (value "10k")
      (footprint "eagle-import:R0402")
      (fields (field (name "MFR") "YAGEO"))
      (libsource (lib "eagle-import") (part "R-US_R0402"))
    )
    (comp (ref "R12")
      (value "150K 1%")
      (footprint "eagle-import:R0402")
      (fields (field (name "MFR") "YAGEO"))
      (libsource (lib "eagle-import") (part "R-US_R0402"))
    )
    (comp (ref "R13")
      (value "1M 1%")
      (footprint "eagle-import:R0402")
      (fields (field (name "MFR") "YAGEO"))
      (libsource (lib "eagle-import") (part "R-US_R0402"))
    )
    (comp (ref "R14")
      (value "150k 1%")
      (footprint "eagle-import:R0402")
      (fields (field (name "MFR") "YAGEO"))
      (libsource (lib "eagle-import") (part "R-US_R0402"))
    )
    (comp (ref "R15")
      (value "3.3 1%")
      (footprint "eagle-import:R0603")
      (fields (field (name "MFR") "PANASONIC"))
      (libsource (lib "eagle-import") (part "R-US_R0603"))
    )
    (comp (ref "R16")
      (value "150k 1%")
      (footprint "eagle-import:R0402")
      (fields (field (name "MFR") "YAGEO"))
      (libsource (lib "eagle-import") (part "R-US_R0402"))
    )
    (comp (ref "R17")
      (value "10k")
      (footprint "eagle-import:R0402")
      (fields (field (name "MFR") "YAGEO"))
      (libsource (lib "eagle-import") (part "R-US_R0402"))
    )
    (comp (ref "R18")
      (value "150K 1%")
      (footprint "eagle-import:R0402")
      (fields (field (name "MFR") "YAGEO"))
      (libsource (lib "eagle-import") (part "R-US_R0402"))
    )
    (comp (ref "R19")
      (value "1M 1%")
      (footprint "eagle-import:R0402")
      (fields (field (name "MFR") "YAGEO"))
      (libsource (lib "eagle-import") (part "R-US_R0402"))
    )
    (comp (ref "R20")
      (value "150k 1%")
      (footprint "eagle-import:R0402")
      (fields (field (name "MFR") "YAGEO"))
      (libsource (lib "eagle-import") (part "R-US_R0402"))
    )
    (comp (ref "R21")
      (value "3.3 1%")
      (footprint "eagle-import:R0603")
      (fields (field (name "MFR") "PANASONIC"))
      (libsource (lib "eagle-import") (part "R-US_R0603"))
    )
    (comp (ref "R22")
      (value "150k 1%")
      (footprint "eagle-import:R0402")
      (fields (field (name "MFR") "YAGEO"))
      (libsource (lib "eagle-import") (part "R-US_R0402"))
    )
    (comp (ref "R23")
      (value "10k")
      (footprint "eagle-import:R0402")
      (fields (field (name "MFR") "YAGEO"))
      (libsource (lib "eagle-import") (part "R-US_R0402"))
    )
    (comp (ref "R24")
      (value "150K 1%")
      (footprint "eagle-import:R0402")
      (fields (field (name "MFR") "YAGEO"))
      (libsource (lib "eagle-import") (part "R-US_R0402"))
    )
    (comp (ref "R31")
      (value "1M 1%")
      (footprint "eagle-import:R0402")
      (fields (field (name "MFR") "YAGEO"))
      (libsource (lib "eagle-import") (part "R-US_R0402"))
    )
    (comp (ref "R32")
      (value "150k 1%")
      (footprint "eagle-import:R0402")
      (fields (field (name "MFR") "YAGEO"))
      (libsource (lib "eagle-import") (part "R-US_R0402"))
    )
    (comp (ref "R33")
      (value "3.3 1%")
      (footprint "eagle-import:R0603")
      (fields (field (name "MFR") "PANASONIC"))
      (libsource (lib "eagle-import") (part "R-US_R0603"))
    )
    (comp (ref "R34")
      (value "150k 1%")
      (footprint "eagle-import:R0402")
      (fields (field (name "MFR") "YAGEO"))
      (libsource (lib "eagle-import") (part "R-US_R0402"))
    )
    (comp (ref "R35")
      (value "10k")
      (footprint "eagle-import:R0402")
      (fields (field (name "MFR") "YAGEO"))
      (libsource (lib "eagle-import") (part "R-US_R0402"))
    )
    (comp (ref "R36")
      (value "150K 1%")
      (footprint "eagle-import:R0402")
      (fields (field (name "MFR") "YAGEO"))
      (libsource (lib "eagle-import") (part "R-US_R0402"))
    )
    (comp (ref "U6")
      (value "CDBHD140L-G")
      (footprint "eagle-import:CDBHDXX0L-G")
      (fields (field (name "MFR") "COMCHIP"))
      (libsource (lib "eagle-import") (part "CDBHD140L-G"))
    )
    (comp (ref "U7")
      (value "CDBHD140L-G")
      (footprint "eagle-import:CDBHDXX0L-G")
      (fields (field (name "MFR") "COMCHIP"))
      (libsource (lib "eagle-import") (part "CDBHD140L-G"))
    )
    (comp (ref "U8")
      (value "MAX9938")
      (footprint "eagle-import:SOT23-5")
      (fields (field (name "MFR") "MAXIM"))
      (libsource (lib "eagle-import") (part "MAX9938"))
    )
    (comp (ref "U9")
      (value "TN2106K1-G")
      (footprint "eagle-import:TN2106K1-G")
      (fields (field (name "MFR") "MICROCHIP"))
      (libsource (lib "eagle-import") (part "TN2106K1-G"))
    )
    (comp (ref "U10")
      (value "CDBHD140L-G")
      (footprint "eagle-import:CDBHDXX0L-G")
      (fields (field (name "MFR") "COMCHIP"))
      (libsource (lib "eagle-import") (part "CDBHD140L-G"))
    )
    (comp (ref "U11")
      (value "CDBHD140L-G")
      (footprint "eagle-import:CDBHDXX0L-G")
      (fields (field (name "MFR") "COMCHIP"))
      (libsource (lib "eagle-import") (part "CDBHD140L-G"))
    )
    (comp (ref "U12")
      (value "MAX9938")
      (footprint "eagle-import:SOT23-5")
      (fields (field (name "MFR") "MAXIM"))
      (libsource (lib "eagle-import") (part "MAX9938"))
    )
    (comp (ref "U13")
      (value "TN2106K1-G")
      (footprint "eagle-import:TN2106K1-G")
      (fields (field (name "MFR") "MICROCHIP"))
      (libsource (lib "eagle-import") (part "TN2106K1-G"))
    )
    (comp (ref "U15")
      (value "CDBHD140L-G")
      (footprint "eagle-import:CDBHDXX0L-G")
      (fields (field (name "MFR") "COMCHIP"))
      (libsource (lib "eagle-import") (part "CDBHD140L-G"))
    )
    (comp (ref "U16")
      (value "CDBHD140L-G")
      (footprint "eagle-import:CDBHDXX0L-G")
      (fields (field (name "MFR") "COMCHIP"))
      (libsource (lib "eagle-import") (part "CDBHD140L-G"))
    )
    (comp (ref "U17")
      (value "MAX9938")
      (footprint "eagle-import:SOT23-5")
      (fields (field (name "MFR") "MAXIM"))
      (libsource (lib "eagle-import") (part "MAX9938"))
    )
    (comp (ref "U18")
      (value "TN2106K1-G")
      (footprint "eagle-import:TN2106K1-G")
      (fields (field (name "MFR") "MICROCHIP"))
      (libsource (lib "eagle-import") (part "TN2106K1-G"))
    )
    (comp (ref "U23")
      (value "CDBHD140L-G")
      (footprint "eagle-import:CDBHDXX0L-G")
      (fields (field (name "MFR") "COMCHIP"))
      (libsource (lib "eagle-import") (part "CDBHD140L-G"))
    )
    (comp (ref "U24")
      (value "CDBHD140L-G")
      (footprint "eagle-import:CDBHDXX0L-G")
      (fields (field (name "MFR") "COMCHIP"))
      (libsource (lib "eagle-import") (part "CDBHD140L-G"))
    )
    (comp (ref "U25")
      (value "MAX9938")
      (footprint "eagle-import:SOT23-5")
      (fields (field (name "MFR") "MAXIM"))
      (libsource (lib "eagle-import") (part "MAX9938"))
    )
    (comp (ref "U26")
      (value "TN2106K1-G")
      (footprint "eagle-import:TN2106K1-G")
      (fields (field (name "MFR") "MICROCHIP"))
      (libsource (lib "eagle-import") (part "TN2106K1-G"))
    )
    (comp (ref "C43")
      (value "10n")
      (footprint "eagle-import:C0402")
      (fields (field (name "MFR") "SAMSUNG"))
      (libsource (lib "eagle-import") (part "C-USC0402"))
    )
    (comp (ref "C44")
      (value "10n")
      (footprint "eagle-import:C0402")
      (fields (field (name "MFR") "SAMSUNG"))
      (libsource (lib "eagle-import") (part "C-USC0402"))
    )
    (comp (ref "C45")
      (value "10n")
      (footprint "eagle-import:C0402")
      (fields (field (name "MFR") "SAMSUNG"))
      (libsource (lib "eagle-import") (part "C-USC0402"))
    )
    (comp (ref "C46")
      (value "4.7u")
      (footprint "eagle-import:C0603")
      (fields (field (name "MFR") "SAMSUNG"))
      (libsource (lib "eagle-import") (part "C-USC0603"))
    )
    (comp (ref "C47")
      (value "22p")
      (footprint "eagle-import:C0402")
      (fields (field (name "MFR") "KEMET"))
      (libsource (lib "eagle-import") (part "C-USC0402"))
    )
    (comp (ref "C48")
      (value "4.7u")
      (footprint "eagle-import:C0603")
      (fields (field (name "MFR") "SAMSUNG"))
      (libsource (lib "eagle-import") (part "C-USC0603"))
    )
    (comp (ref "C63")
      (value "10n")
      (footprint "eagle-import:C0402")
      (fields (field (name "MFR") "SAMSUNG"))
      (libsource (lib "eagle-import") (part "C-USC0402"))
    )
    (comp (ref "D1")
      (value "BAT54")
      (footprint "eagle-import:SOT23")
      (fields (field (name "MFR") "ON"))
      (libsource (lib "eagle-import") (part "BAT54"))
    )
    (comp (ref "D2")
      (value "3.3V")
      (footprint "eagle-import:SOD-323")
      (fields (field (name "MFR") "DIODES_INCORPORATED"))
      (libsource (lib "eagle-import") (part "DIODE-ZENER-MM3Z3V3T1G"))
    )
    (comp (ref "D3")
      (value "3.3V")
      (footprint "eagle-import:SOD-323")
      (fields (field (name "MFR") "DIODES_INCORPORATED"))
      (libsource (lib "eagle-import") (part "DIODE-ZENER-MM3Z3V3T1G"))
    )
    (comp (ref "D30")
      (value "3.3V")
      (footprint "eagle-import:SOD-323")
      (fields (field (name "MFR") "DIODES_INCORPORATED"))
      (libsource (lib "eagle-import") (part "DIODE-ZENER-MM3Z3V3T1G"))
    )
    (comp (ref "D37")
      (value "3.3V")
      (footprint "eagle-import:SOD-323")
      (fields (field (name "MFR") "DIODES_INCORPORATED"))
      (libsource (lib "eagle-import") (part "DIODE-ZENER-MM3Z3V3T1G"))
    )
    (comp (ref "D38")
      (value "3.3V")
      (footprint "eagle-import:SOD-323")
      (fields (field (name "MFR") "DIODES_INCORPORATED"))
      (libsource (lib "eagle-import") (part "DIODE-ZENER-MM3Z3V3T1G"))
    )
    (comp (ref "JP1")
      (value "PINHD-1X2")
      (footprint "eagle-import:1X02")
      (libsource (lib "eagle-import") (part "pinhead_325_PINHD-1X2"))
    )
    (comp (ref "JP21")
      (value "PINHD-1X4")
      (footprint "eagle-import:1X04")
      (libsource (lib "eagle-import") (part "PINHD-1X4"))
    )
    (comp (ref "L1")
      (value "22u")
      (footprint "eagle-import:LQH3NPNXXXXMEX")
      (fields (field (name "MFR") "MURATA"))
      (libsource (lib "eagle-import") (part "LQH3NPN220MMEL"))
    )
    (comp (ref "R3")
      (value "360k")
      (footprint "eagle-import:R0603")
      (fields (field (name "MFR") "PANASONIC"))
      (libsource (lib "eagle-import") (part "R-US_R0603"))
    )
    (comp (ref "R4")
      (value "240k")
      (footprint "eagle-import:R0603")
      (fields (field (name "MFR") "PANASONIC"))
      (libsource (lib "eagle-import") (part "R-US_R0603"))
    )
    (comp (ref "R6")
      (value "180k 1%")
      (footprint "eagle-import:R0402")
      (fields (field (name "MFR") "PANASONIC"))
      (libsource (lib "eagle-import") (part "R-US_R0402"))
    )
    (comp (ref "R52")
      (value "1M")
      (footprint "eagle-import:R0402")
      (fields (field (name "MFR") "yageo"))
      (libsource (lib "eagle-import") (part "R-US_R0402"))
    )
    (comp (ref "R65")
      (value "20K 1%")
      (footprint "eagle-import:R0402")
      (fields (field (name "MFR") "PANASONIC"))
      (libsource (lib "eagle-import") (part "R-US_R0402"))
    )
    (comp (ref "R66")
      (value "180k 1%")
      (footprint "eagle-import:R0402")
      (fields (field (name "MFR") "PANASONIC"))
      (libsource (lib "eagle-import") (part "R-US_R0402"))
    )
    (comp (ref "R67")
      (value "20K 1%")
      (footprint "eagle-import:R0402")
      (fields (field (name "MFR") "PANASONIC"))
      (libsource (lib "eagle-import") (part "R-US_R0402"))
    )
    (comp (ref "R68")
      (value "180k 1%")
      (footprint "eagle-import:R0402")
      (fields (field (name "MFR") "PANASONIC"))
      (libsource (lib "eagle-import") (part "R-US_R0402"))
    )
    (comp (ref "R69")
      (value "20K 1%")
      (footprint "eagle-import:R0402")
      (fields (field (name "MFR") "PANASONIC"))
      (libsource (lib "eagle-import") (part "R-US_R0402"))
    )
    (comp (ref "R70")
      (value "180k 1%")
      (footprint "eagle-import:R0402")
      (fields (field (name "MFR") "PANASONIC"))
      (libsource (lib "eagle-import") (part "R-US_R0402"))
    )
    (comp (ref "R71")
      (value "20K 1%")
      (footprint "eagle-import:R0402")
      (fields (field (name "MFR") "PANASONIC"))
      (libsource (lib "eagle-import") (part "R-US_R0402"))
    )
    (comp (ref "U22")
      (value "TMUX1104DGSR")
      (footprint "eagle-import:SOP50P490X110-10N")
      (fields (field (name "MFR") "texas instruments"))
      (libsource (lib "eagle-import") (part "TMUX1104DGSR"))
    )
    (comp (ref "U27")
      (value "TMUX1104DGSR")
      (footprint "eagle-import:SOP50P490X110-10N")
      (fields (field (name "MFR") "texas instruments"))
      (libsource (lib "eagle-import") (part "TMUX1104DGSR"))
    )
    (comp (ref "U28")
      (value "TMUX1104DGSR")
      (footprint "eagle-import:SOP50P490X110-10N")
      (fields (field (name "MFR") "texas instruments"))
      (libsource (lib "eagle-import") (part "TMUX1104DGSR"))
    )
    (comp (ref "U29")
      (value "TPS62120")
      (footprint "eagle-import:SOP65P280X145-8N")
      (fields (field (name "MFR") "TI"))
      (libsource (lib "eagle-import") (part "TPS62120"))
    )
    (comp (ref "U37")
      (value "TMUX1104DGSR")
      (footprint "eagle-import:SOP50P490X110-10N")
      (fields (field (name "MFR") "texas instruments"))
      (libsource (lib "eagle-import") (part "TMUX1104DGSR"))
    )
    (comp (ref "C6")
      (value "10n")
      (footprint "eagle-import:C0402")
      (fields (field (name "MFR") "SAMSUNG"))
      (libsource (lib "eagle-import") (part "C-USC0402"))
    )
    (comp (ref "C7")
      (value "10n")
      (footprint "eagle-import:C0402")
      (fields (field (name "MFR") "SAMSUNG"))
      (libsource (lib "eagle-import") (part "C-USC0402"))
    )
    (comp (ref "C8")
      (value "10n")
      (footprint "eagle-import:C0402")
      (fields (field (name "MFR") "SAMSUNG"))
      (libsource (lib "eagle-import") (part "C-USC0402"))
    )
    (comp (ref "C9")
      (value "10n")
      (footprint "eagle-import:C0402")
      (fields (field (name "MFR") "SAMSUNG"))
      (libsource (lib "eagle-import") (part "C-USC0402"))
    )
    (comp (ref "C28")
      (value "10n")
      (footprint "eagle-import:C0402")
      (fields (field (name "MFR") "SAMSUNG"))
      (libsource (lib "eagle-import") (part "C-USC0402"))
    )
    (comp (ref "C29")
      (value "10n")
      (footprint "eagle-import:C0402")
      (fields (field (name "MFR") "SAMSUNG"))
      (libsource (lib "eagle-import") (part "C-USC0402"))
    )
    (comp (ref "C30")
      (value "10n")
      (footprint "eagle-import:C0402")
      (fields (field (name "MFR") "SAMSUNG"))
      (libsource (lib "eagle-import") (part "C-USC0402"))
    )
    (comp (ref "C31")
      (value "10n")
      (footprint "eagle-import:C0402")
      (fields (field (name "MFR") "SAMSUNG"))
      (libsource (lib "eagle-import") (part "C-USC0402"))
    )
    (comp (ref "C32")
      (value "10n")
      (footprint "eagle-import:C0402")
      (fields (field (name "MFR") "SAMSUNG"))
      (libsource (lib "eagle-import") (part "C-USC0402"))
    )
    (comp (ref "C33")
      (value "10n")
      (footprint "eagle-import:C0402")
      (fields (field (name "MFR") "SAMSUNG"))
      (libsource (lib "eagle-import") (part "C-USC0402"))
    )
    (comp (ref "C49")
      (value "10u")
      (footprint "eagle-import:C0603")
      (fields (field (name "MFR") "SAMSUNG"))
      (libsource (lib "eagle-import") (part "C-USC0603"))
    )
    (comp (ref "C53")
      (value "10n")
      (footprint "eagle-import:C0402")
      (fields (field (name "MFR") "SAMSUNG"))
      (libsource (lib "eagle-import") (part "C-USC0402"))
    )
    (comp (ref "C54")
      (value "10n")
      (footprint "eagle-import:C0402")
      (fields (field (name "MFR") "SAMSUNG"))
      (libsource (lib "eagle-import") (part "C-USC0402"))
    )
    (comp (ref "C55")
      (value "10n")
      (footprint "eagle-import:C0402")
      (fields (field (name "MFR") "SAMSUNG"))
      (libsource (lib "eagle-import") (part "C-USC0402"))
    )
    (comp (ref "C56")
      (value "10n")
      (footprint "eagle-import:C0402")
      (fields (field (name "MFR") "SAMSUNG"))
      (libsource (lib "eagle-import") (part "C-USC0402"))
    )
    (comp (ref "C57")
      (value "10n")
      (footprint "eagle-import:C0402")
      (fields (field (name "MFR") "SAMSUNG"))
      (libsource (lib "eagle-import") (part "C-USC0402"))
    )
    (comp (ref "C58")
      (value "10n")
      (footprint "eagle-import:C0402")
      (fields (field (name "MFR") "SAMSUNG"))
      (libsource (lib "eagle-import") (part "C-USC0402"))
    )
    (comp (ref "C59")
      (value "10n")
      (footprint "eagle-import:C0402")
      (fields (field (name "MFR") "SAMSUNG"))
      (libsource (lib "eagle-import") (part "C-USC0402"))
    )
    (comp (ref "C60")
      (value "10n")
      (footprint "eagle-import:C0402")
      (fields (field (name "MFR") "SAMSUNG"))
      (libsource (lib "eagle-import") (part "C-USC0402"))
    )
    (comp (ref "C61")
      (value "10n")
      (footprint "eagle-import:C0402")
      (fields (field (name "MFR") "SAMSUNG"))
      (libsource (lib "eagle-import") (part "C-USC0402"))
    )
    (comp (ref "C62")
      (value "10n")
      (footprint "eagle-import:C0402")
      (fields (field (name "MFR") "SAMSUNG"))
      (libsource (lib "eagle-import") (part "C-USC0402"))
    )
    (comp (ref "D4")
      (value "DFLU1200")
      (footprint "eagle-import:DFLU1200")
      (fields (field (name "MFR") "diodes incorporated"))
      (libsource (lib "eagle-import") (part "DFLU1200"))
    )
    (comp (ref "D5")
      (value "DFLU1200")
      (footprint "eagle-import:DFLU1200")
      (fields (field (name "MFR") "diodes incorporated"))
      (libsource (lib "eagle-import") (part "DFLU1200"))
    )
    (comp (ref "D18")
      (value "DFLU1200")
      (footprint "eagle-import:DFLU1200")
      (fields (field (name "MFR") "diodes incorporated"))
      (libsource (lib "eagle-import") (part "DFLU1200"))
    )
    (comp (ref "D19")
      (value "DFLU1200")
      (footprint "eagle-import:DFLU1200")
      (fields (field (name "MFR") "diodes incorporated"))
      (libsource (lib "eagle-import") (part "DFLU1200"))
    )
    (comp (ref "D20")
      (value "DFLU1200")
      (footprint "eagle-import:DFLU1200")
      (fields (field (name "MFR") "diodes incorporated"))
      (libsource (lib "eagle-import") (part "DFLU1200"))
    )
    (comp (ref "D21")
      (value "DFLU1200")
      (footprint "eagle-import:DFLU1200")
      (fields (field (name "MFR") "diodes incorporated"))
      (libsource (lib "eagle-import") (part "DFLU1200"))
    )
    (comp (ref "D26")
      (value "DFLU1200")
      (footprint "eagle-import:DFLU1200")
      (fields (field (name "MFR") "diodes incorporated"))
      (libsource (lib "eagle-import") (part "DFLU1200"))
    )
    (comp (ref "D27")
      (value "DFLU1200")
      (footprint "eagle-import:DFLU1200")
      (fields (field (name "MFR") "diodes incorporated"))
      (libsource (lib "eagle-import") (part "DFLU1200"))
    )
    (comp (ref "D28")
      (value "DFLU1200")
      (footprint "eagle-import:DFLU1200")
      (fields (field (name "MFR") "diodes incorporated"))
      (libsource (lib "eagle-import") (part "DFLU1200"))
    )
    (comp (ref "D29")
      (value "DFLU1200")
      (footprint "eagle-import:DFLU1200")
      (fields (field (name "MFR") "diodes incorporated"))
      (libsource (lib "eagle-import") (part "DFLU1200"))
    )
    (comp (ref "D31")
      (value "DFLU1200")
      (footprint "eagle-import:DFLU1200")
      (fields (field (name "MFR") "diodes incorporated"))
      (libsource (lib "eagle-import") (part "DFLU1200"))
    )
    (comp (ref "D32")
      (value "DFLU1200")
      (footprint "eagle-import:DFLU1200")
      (fields (field (name "MFR") "diodes incorporated"))
      (libsource (lib "eagle-import") (part "DFLU1200"))
    )
    (comp (ref "D33")
      (value "DFLU1200")
      (footprint "eagle-import:DFLU1200")
      (fields (field (name "MFR") "diodes incorporated"))
      (libsource (lib "eagle-import") (part "DFLU1200"))
    )
    (comp (ref "D34")
      (value "DFLU1200")
      (footprint "eagle-import:DFLU1200")
      (fields (field (name "MFR") "diodes incorporated"))
      (libsource (lib "eagle-import") (part "DFLU1200"))
    )
    (comp (ref "D35")
      (value "DFLU1200")
      (footprint "eagle-import:DFLU1200")
      (fields (field (name "MFR") "diodes incorporated"))
      (libsource (lib "eagle-import") (part "DFLU1200"))
    )
    (comp (ref "D36")
      (value "DFLU1200")
      (footprint "eagle-import:DFLU1200")
      (fields (field (name "MFR") "diodes incorporated"))
      (libsource (lib "eagle-import") (part "DFLU1200"))
    )
    (comp (ref "JP8")
      (value "JST-SH-2")
      (footprint "eagle-import:JST-SH-2")
      (fields (field (name "MFR") "jst"))
      (libsource (lib "eagle-import") (part "JST-SH-2"))
    )
    (comp (ref "JP10")
      (value "JST-SH-2")
      (footprint "eagle-import:JST-SH-2")
      (fields (field (name "MFR") "jst"))
      (libsource (lib "eagle-import") (part "JST-SH-2"))
    )
    (comp (ref "JP12")
      (value "JST-SH-2")
      (footprint "eagle-import:JST-SH-2")
      (fields (field (name "MFR") "jst"))
      (libsource (lib "eagle-import") (part "JST-SH-2"))
    )
    (comp (ref "JP13")
      (value "JST-SH-2")
      (footprint "eagle-import:JST-SH-2")
      (fields (field (name "MFR") "jst"))
      (libsource (lib "eagle-import") (part "JST-SH-2"))
    )
    (comp (ref "JP14")
      (value "JST-SH-2")
      (footprint "eagle-import:JST-SH-2")
      (fields (field (name "MFR") "jst"))
      (libsource (lib "eagle-import") (part "JST-SH-2"))
    )
    (comp (ref "JP18")
      (value "JST-SH-2")
      (footprint "eagle-import:JST-SH-2")
      (fields (field (name "MFR") "jst"))
      (libsource (lib "eagle-import") (part "JST-SH-2"))
    )
    (comp (ref "JP19")
      (value "JST-SH-2")
      (footprint "eagle-import:JST-SH-2")
      (fields (field (name "MFR") "jst"))
      (libsource (lib "eagle-import") (part "JST-SH-2"))
    )
    (comp (ref "JP20")
      (value "JST-SH-2")
      (footprint "eagle-import:JST-SH-2")
      (fields (field (name "MFR") "jst"))
      (libsource (lib "eagle-import") (part "JST-SH-2"))
    )
    (comp (ref "Q5")
      (value "2N7002K-7")
      (footprint "eagle-import:2N7002K-7")
      (fields (field (name "MFR") "diodes incorporated"))
      (libsource (lib "eagle-import") (part "2N7002K-7"))
    )
    (comp (ref "Q6")
      (value "BSS138K")
      (footprint "eagle-import:BSS138K")
      (fields (field (name "MFR") "on semiconductor"))
      (libsource (lib "eagle-import") (part "BSS138K"))
    )
    (comp (ref "Q7")
      (value "2N7002K-7")
      (footprint "eagle-import:2N7002K-7")
      (fields (field (name "MFR") "diodes incorporated"))
      (libsource (lib "eagle-import") (part "2N7002K-7"))
    )
    (comp (ref "Q8")
      (value "BSS138K")
      (footprint "eagle-import:BSS138K")
      (fields (field (name "MFR") "on semiconductor"))
      (libsource (lib "eagle-import") (part "BSS138K"))
    )
    (comp (ref "Q9")
      (value "2N7002K-7")
      (footprint "eagle-import:2N7002K-7")
      (fields (field (name "MFR") "diodes incorporated"))
      (libsource (lib "eagle-import") (part "2N7002K-7"))
    )
    (comp (ref "Q10")
      (value "BSS138K")
      (footprint "eagle-import:BSS138K")
      (fields (field (name "MFR") "on semiconductor"))
      (libsource (lib "eagle-import") (part "BSS138K"))
    )
    (comp (ref "Q11")
      (value "2N7002K-7")
      (footprint "eagle-import:2N7002K-7")
      (fields (field (name "MFR") "diodes incorporated"))
      (libsource (lib "eagle-import") (part "2N7002K-7"))
    )
    (comp (ref "Q12")
      (value "BSS138K")
      (footprint "eagle-import:BSS138K")
      (fields (field (name "MFR") "on semiconductor"))
      (libsource (lib "eagle-import") (part "BSS138K"))
    )
    (comp (ref "Q13")
      (value "2N7002K-7")
      (footprint "eagle-import:2N7002K-7")
      (fields (field (name "MFR") "diodes incorporated"))
      (libsource (lib "eagle-import") (part "2N7002K-7"))
    )
    (comp (ref "Q14")
      (value "BSS138K")
      (footprint "eagle-import:BSS138K")
      (fields (field (name "MFR") "on semiconductor"))
      (libsource (lib "eagle-import") (part "BSS138K"))
    )
    (comp (ref "Q15")
      (value "2N7002K-7")
      (footprint "eagle-import:2N7002K-7")
      (fields (field (name "MFR") "diodes incorporated"))
      (libsource (lib "eagle-import") (part "2N7002K-7"))
    )
    (comp (ref "Q16")
      (value "BSS138K")
      (footprint "eagle-import:BSS138K")
      (fields (field (name "MFR") "on semiconductor"))
      (libsource (lib "eagle-import") (part "BSS138K"))
    )
    (comp (ref "Q17")
      (value "2N7002K-7")
      (footprint "eagle-import:2N7002K-7")
      (fields (field (name "MFR") "diodes incorporated"))
      (libsource (lib "eagle-import") (part "2N7002K-7"))
    )
    (comp (ref "Q18")
      (value "BSS138K")
      (footprint "eagle-import:BSS138K")
      (fields (field (name "MFR") "on semiconductor"))
      (libsource (lib "eagle-import") (part "BSS138K"))
    )
    (comp (ref "Q19")
      (value "2N7002K-7")
      (footprint "eagle-import:2N7002K-7")
      (fields (field (name "MFR") "diodes incorporated"))
      (libsource (lib "eagle-import") (part "2N7002K-7"))
    )
    (comp (ref "Q20")
      (value "BSS138K")
      (footprint "eagle-import:BSS138K")
      (fields (field (name "MFR") "on semiconductor"))
      (libsource (lib "eagle-import") (part "BSS138K"))
    )
    (comp (ref "Q21")
      (value "2N7002K-7")
      (footprint "eagle-import:2N7002K-7")
      (fields (field (name "MFR") "diodes incorporated"))
      (libsource (lib "eagle-import") (part "2N7002K-7"))
    )
    (comp (ref "Q22")
      (value "BSS138K")
      (footprint "eagle-import:BSS138K")
      (fields (field (name "MFR") "on semiconductor"))
      (libsource (lib "eagle-import") (part "BSS138K"))
    )
    (comp (ref "Q23")
      (value "2N7002K-7")
      (footprint "eagle-import:2N7002K-7")
      (fields (field (name "MFR") "diodes incorporated"))
      (libsource (lib "eagle-import") (part "2N7002K-7"))
    )
    (comp (ref "Q24")
      (value "BSS138K")
      (footprint "eagle-import:BSS138K")
      (fields (field (name "MFR") "on semiconductor"))
      (libsource (lib "eagle-import") (part "BSS138K"))
    )
    (comp (ref "Q25")
      (value "2N7002K-7")
      (footprint "eagle-import:2N7002K-7")
      (fields (field (name "MFR") "diodes incorporated"))
      (libsource (lib "eagle-import") (part "2N7002K-7"))
    )
    (comp (ref "Q26")
      (value "BSS138K")
      (footprint "eagle-import:BSS138K")
      (fields (field (name "MFR") "on semiconductor"))
      (libsource (lib "eagle-import") (part "BSS138K"))
    )
    (comp (ref "Q27")
      (value "2N7002K-7")
      (footprint "eagle-import:2N7002K-7")
      (fields (field (name "MFR") "diodes incorporated"))
      (libsource (lib "eagle-import") (part "2N7002K-7"))
    )
    (comp (ref "Q28")
      (value "BSS138K")
      (footprint "eagle-import:BSS138K")
      (fields (field (name "MFR") "on semiconductor"))
      (libsource (lib "eagle-import") (part "BSS138K"))
    )
    (comp (ref "Q29")
      (value "2N7002K-7")
      (footprint "eagle-import:2N7002K-7")
      (fields (field (name "MFR") "diodes incorporated"))
      (libsource (lib "eagle-import") (part "2N7002K-7"))
    )
    (comp (ref "Q30")
      (value "BSS138K")
      (footprint "eagle-import:BSS138K")
      (fields (field (name "MFR") "on semiconductor"))
      (libsource (lib "eagle-import") (part "BSS138K"))
    )
    (comp (ref "Q31")
      (value "2N7002K-7")
      (footprint "eagle-import:2N7002K-7")
      (fields (field (name "MFR") "diodes incorporated"))
      (libsource (lib "eagle-import") (part "2N7002K-7"))
    )
    (comp (ref "Q32")
      (value "BSS138K")
      (footprint "eagle-import:BSS138K")
      (fields (field (name "MFR") "on semiconductor"))
      (libsource (lib "eagle-import") (part "BSS138K"))
    )
    (comp (ref "Q33")
      (value "2N7002K-7")
      (footprint "eagle-import:2N7002K-7")
      (fields (field (name "MFR") "diodes incorporated"))
      (libsource (lib "eagle-import") (part "2N7002K-7"))
    )
    (comp (ref "Q34")
      (value "BSS138K")
      (footprint "eagle-import:BSS138K")
      (fields (field (name "MFR") "on semiconductor"))
      (libsource (lib "eagle-import") (part "BSS138K"))
    )
    (comp (ref "Q35")
      (value "2N7002K-7")
      (footprint "eagle-import:2N7002K-7")
      (fields (field (name "MFR") "diodes incorporated"))
      (libsource (lib "eagle-import") (part "2N7002K-7"))
    )
    (comp (ref "Q36")
      (value "BSS138K")
      (footprint "eagle-import:BSS138K")
      (fields (field (name "MFR") "on semiconductor"))
      (libsource (lib "eagle-import") (part "BSS138K"))
    )
    (comp (ref "R2")
      (value "1M")
      (footprint "eagle-import:R0402")
      (fields (field (name "MFR") "yageo"))
      (libsource (lib "eagle-import") (part "R-US_R0402"))
    )
    (comp (ref "R5")
      (value "100k")
      (footprint "eagle-import:R0402")
      (fields (field (name "MFR") "yageo"))
      (libsource (lib "eagle-import") (part "R-US_R0402"))
    )
    (comp (ref "R25")
      (value "1M")
      (footprint "eagle-import:R0402")
      (fields (field (name "MFR") "yageo"))
      (libsource (lib "eagle-import") (part "R-US_R0402"))
    )
    (comp (ref "R26")
      (value "100k")
      (footprint "eagle-import:R0402")
      (fields (field (name "MFR") "yageo"))
      (libsource (lib "eagle-import") (part "R-US_R0402"))
    )
    (comp (ref "R27")
      (value "1M")
      (footprint "eagle-import:R0402")
      (fields (field (name "MFR") "yageo"))
      (libsource (lib "eagle-import") (part "R-US_R0402"))
    )
    (comp (ref "R28")
      (value "100k")
      (footprint "eagle-import:R0402")
      (fields (field (name "MFR") "yageo"))
      (libsource (lib "eagle-import") (part "R-US_R0402"))
    )
    (comp (ref "R29")
      (value "1M")
      (footprint "eagle-import:R0402")
      (fields (field (name "MFR") "yageo"))
      (libsource (lib "eagle-import") (part "R-US_R0402"))
    )
    (comp (ref "R30")
      (value "100k")
      (footprint "eagle-import:R0402")
      (fields (field (name "MFR") "yageo"))
      (libsource (lib "eagle-import") (part "R-US_R0402"))
    )
    (comp (ref "R37")
      (value "1M")
      (footprint "eagle-import:R0402")
      (fields (field (name "MFR") "yageo"))
      (libsource (lib "eagle-import") (part "R-US_R0402"))
    )
    (comp (ref "R38")
      (value "100k")
      (footprint "eagle-import:R0402")
      (fields (field (name "MFR") "yageo"))
      (libsource (lib "eagle-import") (part "R-US_R0402"))
    )
    (comp (ref "R39")
      (value "1M")
      (footprint "eagle-import:R0402")
      (fields (field (name "MFR") "yageo"))
      (libsource (lib "eagle-import") (part "R-US_R0402"))
    )
    (comp (ref "R40")
      (value "100k")
      (footprint "eagle-import:R0402")
      (fields (field (name "MFR") "yageo"))
      (libsource (lib "eagle-import") (part "R-US_R0402"))
    )
    (comp (ref "R41")
      (value "1M")
      (footprint "eagle-import:R0402")
      (fields (field (name "MFR") "yageo"))
      (libsource (lib "eagle-import") (part "R-US_R0402"))
    )
    (comp (ref "R42")
      (value "100k")
      (footprint "eagle-import:R0402")
      (fields (field (name "MFR") "yageo"))
      (libsource (lib "eagle-import") (part "R-US_R0402"))
    )
    (comp (ref "R43")
      (value "1M")
      (footprint "eagle-import:R0402")
      (fields (field (name "MFR") "yageo"))
      (libsource (lib "eagle-import") (part "R-US_R0402"))
    )
    (comp (ref "R44")
      (value "100k")
      (footprint "eagle-import:R0402")
      (fields (field (name "MFR") "yageo"))
      (libsource (lib "eagle-import") (part "R-US_R0402"))
    )
    (comp (ref "R45")
      (value "1M")
      (footprint "eagle-import:R0402")
      (fields (field (name "MFR") "yageo"))
      (libsource (lib "eagle-import") (part "R-US_R0402"))
    )
    (comp (ref "R46")
      (value "100k")
      (footprint "eagle-import:R0402")
      (fields (field (name "MFR") "yageo"))
      (libsource (lib "eagle-import") (part "R-US_R0402"))
    )
    (comp (ref "R47")
      (value "1M")
      (footprint "eagle-import:R0402")
      (fields (field (name "MFR") "yageo"))
      (libsource (lib "eagle-import") (part "R-US_R0402"))
    )
    (comp (ref "R48")
      (value "100k")
      (footprint "eagle-import:R0402")
      (fields (field (name "MFR") "yageo"))
      (libsource (lib "eagle-import") (part "R-US_R0402"))
    )
    (comp (ref "R50")
      (value "1M")
      (footprint "eagle-import:R0402")
      (fields (field (name "MFR") "yageo"))
      (libsource (lib "eagle-import") (part "R-US_R0402"))
    )
    (comp (ref "R51")
      (value "1M")
      (footprint "eagle-import:R0402")
      (fields (field (name "MFR") "yageo"))
      (libsource (lib "eagle-import") (part "R-US_R0402"))
    )
    (comp (ref "R53")
      (value "1M")
      (footprint "eagle-import:R0402")
      (fields (field (name "MFR") "yageo"))
      (libsource (lib "eagle-import") (part "R-US_R0402"))
    )
    (comp (ref "R54")
      (value "100k")
      (footprint "eagle-import:R0402")
      (fields (field (name "MFR") "yageo"))
      (libsource (lib "eagle-import") (part "R-US_R0402"))
    )
    (comp (ref "R55")
      (value "1M")
      (footprint "eagle-import:R0402")
      (fields (field (name "MFR") "yageo"))
      (libsource (lib "eagle-import") (part "R-US_R0402"))
    )
    (comp (ref "R56")
      (value "100k")
      (footprint "eagle-import:R0402")
      (fields (field (name "MFR") "yageo"))
      (libsource (lib "eagle-import") (part "R-US_R0402"))
    )
    (comp (ref "R57")
      (value "1M")
      (footprint "eagle-import:R0402")
      (fields (field (name "MFR") "yageo"))
      (libsource (lib "eagle-import") (part "R-US_R0402"))
    )
    (comp (ref "R58")
      (value "100k")
      (footprint "eagle-import:R0402")
      (fields (field (name "MFR") "yageo"))
      (libsource (lib "eagle-import") (part "R-US_R0402"))
    )
    (comp (ref "R59")
      (value "1M")
      (footprint "eagle-import:R0402")
      (fields (field (name "MFR") "yageo"))
      (libsource (lib "eagle-import") (part "R-US_R0402"))
    )
    (comp (ref "R60")
      (value "100k")
      (footprint "eagle-import:R0402")
      (fields (field (name "MFR") "yageo"))
      (libsource (lib "eagle-import") (part "R-US_R0402"))
    )
    (comp (ref "R61")
      (value "1M")
      (footprint "eagle-import:R0402")
      (fields (field (name "MFR") "yageo"))
      (libsource (lib "eagle-import") (part "R-US_R0402"))
    )
    (comp (ref "R62")
      (value "100k")
      (footprint "eagle-import:R0402")
      (fields (field (name "MFR") "yageo"))
      (libsource (lib "eagle-import") (part "R-US_R0402"))
    )
    (comp (ref "R63")
      (value "1M")
      (footprint "eagle-import:R0402")
      (fields (field (name "MFR") "yageo"))
      (libsource (lib "eagle-import") (part "R-US_R0402"))
    )
    (comp (ref "R64")
      (value "100k")
      (footprint "eagle-import:R0402")
      (fields (field (name "MFR") "yageo"))
      (libsource (lib "eagle-import") (part "R-US_R0402"))
    )
    (comp (ref "U4")
      (value "CDBHD140L-G")
      (footprint "eagle-import:CDBHDXX0L-G")
      (fields (field (name "MFR") "comchip"))
      (libsource (lib "eagle-import") (part "CDBHD140L-G"))
    )
    (comp (ref "U5")
      (value "CDBHD140L-G")
      (footprint "eagle-import:CDBHDXX0L-G")
      (fields (field (name "MFR") "comchip"))
      (libsource (lib "eagle-import") (part "CDBHD140L-G"))
    )
    (comp (ref "U14")
      (value "CDBHD140L-G")
      (footprint "eagle-import:CDBHDXX0L-G")
      (fields (field (name "MFR") "comchip"))
      (libsource (lib "eagle-import") (part "CDBHD140L-G"))
    )
    (comp (ref "U19")
      (value "CDBHD140L-G")
      (footprint "eagle-import:CDBHDXX0L-G")
      (fields (field (name "MFR") "comchip"))
      (libsource (lib "eagle-import") (part "CDBHD140L-G"))
    )
    (comp (ref "U20")
      (value "CDBHD140L-G")
      (footprint "eagle-import:CDBHDXX0L-G")
      (fields (field (name "MFR") "comchip"))
      (libsource (lib "eagle-import") (part "CDBHD140L-G"))
    )
    (comp (ref "U30")
      (value "TMUX1108RSVR")
      (footprint "eagle-import:UQFN16-RSV0016A")
      (fields (field (name "MFR") "TI"))
      (libsource (lib "eagle-import") (part "TMUX1108RSVR"))
    )
    (comp (ref "U31")
      (value "CDBHD140L-G")
      (footprint "eagle-import:CDBHDXX0L-G")
      (fields (field (name "MFR") "comchip"))
      (libsource (lib "eagle-import") (part "CDBHD140L-G"))
    )
    (comp (ref "U32")
      (value "CDBHD140L-G")
      (footprint "eagle-import:CDBHDXX0L-G")
      (fields (field (name "MFR") "comchip"))
      (libsource (lib "eagle-import") (part "CDBHD140L-G"))
    )
    (comp (ref "U33")
      (value "CDBHD140L-G")
      (footprint "eagle-import:CDBHDXX0L-G")
      (fields (field (name "MFR") "comchip"))
      (libsource (lib "eagle-import") (part "CDBHD140L-G"))
    )
    (comp (ref "U34")
      (value "TMUX1108RSVR")
      (footprint "eagle-import:UQFN16-RSV0016A")
      (fields (field (name "MFR") "TI"))
      (libsource (lib "eagle-import") (part "TMUX1108RSVR"))
    )
    (comp (ref "U35")
      (value "TMUX1108RSVR")
      (footprint "eagle-import:UQFN16-RSV0016A")
      (fields (field (name "MFR") "TI"))
      (libsource (lib "eagle-import") (part "TMUX1108RSVR"))
    )
    (comp (ref "U36")
      (value "TMUX1108RSVR")
      (footprint "eagle-import:UQFN16-RSV0016A")
      (fields (field (name "MFR") "TI"))
      (libsource (lib "eagle-import") (part "TMUX1108RSVR"))
    )
    (comp (ref "JP2")
      (value "PINHD-1X8")
      (footprint "eagle-import:1X08")
      (libsource (lib "eagle-import") (part "PINHD-1X8"))
    )
    (comp (ref "JP5")
      (value "PINHD-1X10")
      (footprint "eagle-import:1X10")
      (libsource (lib "eagle-import") (part "PINHD-1X10"))
    )
    (comp (ref "JP6")
      (value "PINHD-1X6")
      (footprint "eagle-import:1X06")
      (libsource (lib "eagle-import") (part "PINHD-1X6"))
    )
    (comp (ref "JP7")
      (value "PINHD-1X8")
      (footprint "eagle-import:1X08")
      (libsource (lib "eagle-import") (part "PINHD-1X8"))
    )
    (comp (ref "J2")
      (value "FTSH-105-01-F-DV-007-K-P")
      (footprint "eagle-import:FTSH-105-01-F-DV-007-K-P")
      (fields (field (name "MFR") "samtec"))
      (libsource (lib "eagle-import") (part "FTSH-105-01-F-DV-007-K-P"))
    )
    (comp (ref "LED1")
      (value "LEDCHIP-LED0603")
      (footprint "eagle-import:CHIP-LED0603")
      (fields (field (name "MFR") "stanley electric co"))
      (libsource (lib "eagle-import") (part "LEDCHIP-LED0603"))
    )
    (comp (ref "LED2")
      (value "LEDCHIP-LED0603")
      (footprint "eagle-import:CHIP-LED0603")
      (fields (field (name "MFR") "stanley electric co"))
      (libsource (lib "eagle-import") (part "LEDCHIP-LED0603"))
    )
    (comp (ref "LED3")
      (value "LEDCHIP-LED0603")
      (footprint "eagle-import:CHIP-LED0603")
      (fields (field (name "MFR") "stanley electric co"))
      (libsource (lib "eagle-import") (part "LEDCHIP-LED0603"))
    )
    (comp (ref "R72")
      (value "330")
      (footprint "eagle-import:R0402")
      (fields (field (name "MFR") "yageo"))
      (libsource (lib "eagle-import") (part "R-US_R0402"))
    )
    (comp (ref "R73")
      (value "330")
      (footprint "eagle-import:R0402")
      (fields (field (name "MFR") "yageo"))
      (libsource (lib "eagle-import") (part "R-US_R0402"))
    )
    (comp (ref "R74")
      (value "330")
      (footprint "eagle-import:R0402")
      (fields (field (name "MFR") "yageo"))
      (libsource (lib "eagle-import") (part "R-US_R0402"))
    )
    (comp (ref "SW2")
      (value "TE_FSM4JSMA")
      (footprint "eagle-import:TE_FSMJSMA")
      (fields (field (name "MFR") "TE connectivity"))
      (libsource (lib "eagle-import") (part "TE_FSM4JSMA"))
    )
    (comp (ref "SW3")
      (value "TE_FSM4JSMA")
      (footprint "eagle-import:TE_FSMJSMA")
      (fields (field (name "MFR") "TE connectivity"))
      (libsource (lib "eagle-import") (part "TE_FSM4JSMA"))
    )
    (comp (ref "U1")
      (value "ARTEMIS_MODULESMD")
      (footprint "eagle-import:ARTEMIS_FP")
      (fields (field (name "MFR") "sparkfun"))
      (libsource (lib "eagle-import") (part "ARTEMIS_MODULESMD"))
    )
  )
  (nets
    (net (code "1") (name "A0") (class "Default")
      (node (ref "JP6") (pin "1") (pinfunction "1_1") (pintype "passive"))
      (node (ref "U1") (pin "~AD29") (pinfunction "~{AD29(PDMDATA})_~AD29") (pintype "bidirectional"))
    )
    (net (code "2") (name "A1") (class "Default")
      (node (ref "JP6") (pin "2") (pinfunction "2_2") (pintype "passive"))
      (node (ref "U1") (pin "~AD11") (pinfunction "~{AD11(PDMDATA})_~AD11") (pintype "bidirectional"))
    )
    (net (code "3") (name "A2") (class "Default")
      (node (ref "JP6") (pin "3") (pinfunction "3_3") (pintype "passive"))
      (node (ref "U1") (pin "AD34") (pinfunction "AD34(CMPRF2/PDMDATA)_AD34") (pintype "bidirectional"))
    )
    (net (code "4") (name "A4") (class "Default")
      (node (ref "JP6") (pin "5") (pinfunction "5_5") (pintype "passive"))
      (node (ref "U1") (pin "AD16") (pinfunction "AD16(TRIG0/SCCRST)_AD16") (pintype "bidirectional"))
    )
    (net (code "5") (name "A5") (class "Default")
      (node (ref "JP6") (pin "6") (pinfunction "6_6") (pintype "passive"))
      (node (ref "U1") (pin "~AD31") (pinfunction "~{AD31(SCCCLK})_~AD31") (pintype "bidirectional"))
    )
    (net (code "6") (name "AD33{slash}SWO{slash}A3") (class "Default")
      (node (ref "J2") (pin "P$6") (pinfunction "P$6_P$6") (pintype "bidirectional"))
      (node (ref "JP6") (pin "4") (pinfunction "4_4") (pintype "passive"))
      (node (ref "U1") (pin "~AD33/SWO") (pinfunction "~{AD33(SWO/32KHZ})_~AD33/SWO") (pintype "bidirectional"))
    )
    (net (code "7") (name "BOOT") (class "Default")
      (node (ref "C50") (pin "2") (pinfunction "2_2") (pintype "passive"))
      (node (ref "R1") (pin "2") (pinfunction "2_2") (pintype "passive"))
      (node (ref "U1") (pin "BOOT") (pinfunction "~{BOOT(SDO5/RX1/32KHZ})_BOOT") (pintype "bidirectional"))
    )
    (net (code "8") (name "BTN_DOWN_CAP0") (class "Default")
      (node (ref "C7") (pin "1") (pinfunction "1_1") (pintype "passive"))
      (node (ref "D5") (pin "K") (pinfunction "K_K") (pintype "bidirectional"))
      (node (ref "Q7") (pin "G") (pinfunction "G_G") (pintype "bidirectional"))
      (node (ref "Q8") (pin "D") (pinfunction "D_D") (pintype "bidirectional"))
    )
    (net (code "9") (name "BTN_DOWN_CAP1") (class "Default")
      (node (ref "C9") (pin "1") (pinfunction "1_1") (pintype "passive"))
      (node (ref "D19") (pin "K") (pinfunction "K_K") (pintype "bidirectional"))
      (node (ref "Q11") (pin "G") (pinfunction "G_G") (pintype "bidirectional"))
      (node (ref "Q12") (pin "D") (pinfunction "D_D") (pintype "bidirectional"))
    )
    (net (code "10") (name "BTN_DOWN_CAP2") (class "Default")
      (node (ref "C29") (pin "1") (pinfunction "1_1") (pintype "passive"))
      (node (ref "D21") (pin "K") (pinfunction "K_K") (pintype "bidirectional"))
      (node (ref "Q15") (pin "G") (pinfunction "G_G") (pintype "bidirectional"))
      (node (ref "Q16") (pin "D") (pinfunction "D_D") (pintype "bidirectional"))
    )
    (net (code "11") (name "BTN_DOWN_CAP3") (class "Default")
      (node (ref "C31") (pin "1") (pinfunction "1_1") (pintype "passive"))
      (node (ref "D27") (pin "K") (pinfunction "K_K") (pintype "bidirectional"))
      (node (ref "Q19") (pin "G") (pinfunction "G_G") (pintype "bidirectional"))
      (node (ref "Q20") (pin "D") (pinfunction "D_D") (pintype "bidirectional"))
    )
    (net (code "12") (name "BTN_DOWN_CAP4") (class "Default")
      (node (ref "C33") (pin "1") (pinfunction "1_1") (pintype "passive"))
      (node (ref "D29") (pin "K") (pinfunction "K_K") (pintype "bidirectional"))
      (node (ref "Q23") (pin "G") (pinfunction "G_G") (pintype "bidirectional"))
      (node (ref "Q24") (pin "D") (pinfunction "D_D") (pintype "bidirectional"))
    )
    (net (code "13") (name "BTN_DOWN_CAP5") (class "Default")
      (node (ref "C56") (pin "1") (pinfunction "1_1") (pintype "passive"))
      (node (ref "D32") (pin "K") (pinfunction "K_K") (pintype "bidirectional"))
      (node (ref "Q27") (pin "G") (pinfunction "G_G") (pintype "bidirectional"))
      (node (ref "Q28") (pin "D") (pinfunction "D_D") (pintype "bidirectional"))
    )
    (net (code "14") (name "BTN_DOWN_CAP6") (class "Default")
      (node (ref "C58") (pin "1") (pinfunction "1_1") (pintype "passive"))
      (node (ref "D34") (pin "K") (pinfunction "K_K") (pintype "bidirectional"))
      (node (ref "Q31") (pin "G") (pinfunction "G_G") (pintype "bidirectional"))
      (node (ref "Q32") (pin "D") (pinfunction "D_D") (pintype "bidirectional"))
    )
    (net (code "15") (name "BTN_DOWN_CAP7") (class "Default")
      (node (ref "C60") (pin "1") (pinfunction "1_1") (pintype "passive"))
      (node (ref "D36") (pin "K") (pinfunction "K_K") (pintype "bidirectional"))
      (node (ref "Q35") (pin "G") (pinfunction "G_G") (pintype "bidirectional"))
      (node (ref "Q36") (pin "D") (pinfunction "D_D") (pintype "bidirectional"))
    )
    (net (code "16") (name "BTN_DOWN_CLR0") (class "Default")
      (node (ref "Q8") (pin "G") (pinfunction "G_G") (pintype "bidirectional"))
      (node (ref "R26") (pin "2") (pinfunction "2_2") (pintype "passive"))
      (node (ref "U34") (pin "P$2") (pinfunction "S1_P$2") (pintype "bidirectional"))
    )
    (net (code "17") (name "BTN_DOWN_CLR1") (class "Default")
      (node (ref "Q12") (pin "G") (pinfunction "G_G") (pintype "bidirectional"))
      (node (ref "R30") (pin "2") (pinfunction "2_2") (pintype "passive"))
      (node (ref "U34") (pin "P$3") (pinfunction "S2_P$3") (pintype "bidirectional"))
    )
    (net (code "18") (name "BTN_DOWN_CLR2") (class "Default")
      (node (ref "Q16") (pin "G") (pinfunction "G_G") (pintype "bidirectional"))
      (node (ref "R40") (pin "2") (pinfunction "2_2") (pintype "passive"))
      (node (ref "U34") (pin "P$4") (pinfunction "S3_P$4") (pintype "bidirectional"))
    )
    (net (code "19") (name "BTN_DOWN_CLR3") (class "Default")
      (node (ref "Q20") (pin "G") (pinfunction "G_G") (pintype "bidirectional"))
      (node (ref "R44") (pin "2") (pinfunction "2_2") (pintype "passive"))
      (node (ref "U34") (pin "P$5") (pinfunction "S4_P$5") (pintype "bidirectional"))
    )
    (net (code "20") (name "BTN_DOWN_CLR4") (class "Default")
      (node (ref "Q24") (pin "G") (pinfunction "G_G") (pintype "bidirectional"))
      (node (ref "R48") (pin "2") (pinfunction "2_2") (pintype "passive"))
      (node (ref "U34") (pin "P$10") (pinfunction "S5_P$10") (pintype "bidirectional"))
    )
    (net (code "21") (name "BTN_DOWN_CLR5") (class "Default")
      (node (ref "Q28") (pin "G") (pinfunction "G_G") (pintype "bidirectional"))
      (node (ref "R56") (pin "2") (pinfunction "2_2") (pintype "passive"))
      (node (ref "U34") (pin "P$9") (pinfunction "S6_P$9") (pintype "bidirectional"))
    )
    (net (code "22") (name "BTN_DOWN_CLR6") (class "Default")
      (node (ref "Q32") (pin "G") (pinfunction "G_G") (pintype "bidirectional"))
      (node (ref "R60") (pin "2") (pinfunction "2_2") (pintype "passive"))
      (node (ref "U34") (pin "P$8") (pinfunction "S7_P$8") (pintype "bidirectional"))
    )
    (net (code "23") (name "BTN_DOWN_CLR7") (class "Default")
      (node (ref "Q36") (pin "G") (pinfunction "G_G") (pintype "bidirectional"))
      (node (ref "R64") (pin "2") (pinfunction "2_2") (pintype "passive"))
      (node (ref "U34") (pin "P$7") (pinfunction "S8_P$7") (pintype "bidirectional"))
    )
    (net (code "24") (name "BTN_DOWN_CLR_MUX_D") (class "Default")
      (node (ref "U1") (pin "D1") (pinfunction "(SLSDO/SLSDA)D1_D1") (pintype "bidirectional"))
      (node (ref "U34") (pin "P$6") (pinfunction "D_P$6") (pintype "bidirectional"))
    )
    (net (code "25") (name "BTN_DOWN_SENSE0") (class "Default")
      (node (ref "Q7") (pin "D") (pinfunction "D_D") (pintype "bidirectional"))
      (node (ref "U36") (pin "P$2") (pinfunction "S1_P$2") (pintype "bidirectional"))
    )
    (net (code "26") (name "BTN_DOWN_SENSE1") (class "Default")
      (node (ref "Q11") (pin "D") (pinfunction "D_D") (pintype "bidirectional"))
      (node (ref "U36") (pin "P$3") (pinfunction "S2_P$3") (pintype "bidirectional"))
    )
    (net (code "27") (name "BTN_DOWN_SENSE2") (class "Default")
      (node (ref "Q15") (pin "D") (pinfunction "D_D") (pintype "bidirectional"))
      (node (ref "U36") (pin "P$4") (pinfunction "S3_P$4") (pintype "bidirectional"))
    )
    (net (code "28") (name "BTN_DOWN_SENSE3") (class "Default")
      (node (ref "Q19") (pin "D") (pinfunction "D_D") (pintype "bidirectional"))
      (node (ref "U36") (pin "P$5") (pinfunction "S4_P$5") (pintype "bidirectional"))
    )
    (net (code "29") (name "BTN_DOWN_SENSE4") (class "Default")
      (node (ref "Q23") (pin "D") (pinfunction "D_D") (pintype "bidirectional"))
      (node (ref "U36") (pin "P$10") (pinfunction "S5_P$10") (pintype "bidirectional"))
    )
    (net (code "30") (name "BTN_DOWN_SENSE5") (class "Default")
      (node (ref "Q27") (pin "D") (pinfunction "D_D") (pintype "bidirectional"))
      (node (ref "U36") (pin "P$9") (pinfunction "S6_P$9") (pintype "bidirectional"))
    )
    (net (code "31") (name "BTN_DOWN_SENSE6") (class "Default")
      (node (ref "Q31") (pin "D") (pinfunction "D_D") (pintype "bidirectional"))
      (node (ref "U36") (pin "P$8") (pinfunction "S7_P$8") (pintype "bidirectional"))
    )
    (net (code "32") (name "BTN_DOWN_SENSE7") (class "Default")
      (node (ref "Q35") (pin "D") (pinfunction "D_D") (pintype "bidirectional"))
      (node (ref "U36") (pin "P$7") (pinfunction "S8_P$7") (pintype "bidirectional"))
    )
    (net (code "33") (name "BTN_DOWN_SENSE_MUX_D") (class "Default")
      (node (ref "R51") (pin "1") (pinfunction "1_1") (pintype "passive"))
      (node (ref "U1") (pin "D3") (pinfunction "(SLNCE/I2SWCLK)D3_D3") (pintype "bidirectional"))
      (node (ref "U36") (pin "P$6") (pinfunction "D_P$6") (pintype "bidirectional"))
    )
    (net (code "34") (name "BTN_PIN1_0") (class "Default")
      (node (ref "D4") (pin "A") (pinfunction "A_A") (pintype "bidirectional"))
      (node (ref "JP8") (pin "2") (pinfunction "-_2") (pintype "bidirectional"))
      (node (ref "R2") (pin "2") (pinfunction "2_2") (pintype "passive"))
      (node (ref "U4") (pin "P$4") (pinfunction "P$4_P$4") (pintype "bidirectional"))
    )
    (net (code "35") (name "BTN_PIN1_1") (class "Default")
      (node (ref "D18") (pin "A") (pinfunction "A_A") (pintype "bidirectional"))
      (node (ref "JP10") (pin "2") (pinfunction "-_2") (pintype "bidirectional"))
      (node (ref "R27") (pin "2") (pinfunction "2_2") (pintype "passive"))
      (node (ref "U5") (pin "P$4") (pinfunction "P$4_P$4") (pintype "bidirectional"))
    )
    (net (code "36") (name "BTN_PIN1_2") (class "Default")
      (node (ref "D20") (pin "A") (pinfunction "A_A") (pintype "bidirectional"))
      (node (ref "JP12") (pin "2") (pinfunction "-_2") (pintype "bidirectional"))
      (node (ref "R37") (pin "2") (pinfunction "2_2") (pintype "passive"))
      (node (ref "U14") (pin "P$4") (pinfunction "P$4_P$4") (pintype "bidirectional"))
    )
    (net (code "37") (name "BTN_PIN1_3") (class "Default")
      (node (ref "D26") (pin "A") (pinfunction "A_A") (pintype "bidirectional"))
      (node (ref "JP13") (pin "2") (pinfunction "-_2") (pintype "bidirectional"))
      (node (ref "R41") (pin "2") (pinfunction "2_2") (pintype "passive"))
      (node (ref "U19") (pin "P$4") (pinfunction "P$4_P$4") (pintype "bidirectional"))
    )
    (net (code "38") (name "BTN_PIN1_4") (class "Default")
      (node (ref "D28") (pin "A") (pinfunction "A_A") (pintype "bidirectional"))
      (node (ref "JP14") (pin "2") (pinfunction "-_2") (pintype "bidirectional"))
      (node (ref "R45") (pin "2") (pinfunction "2_2") (pintype "passive"))
      (node (ref "U20") (pin "P$4") (pinfunction "P$4_P$4") (pintype "bidirectional"))
    )
    (net (code "39") (name "BTN_PIN1_5") (class "Default")
      (node (ref "D31") (pin "A") (pinfunction "A_A") (pintype "bidirectional"))
      (node (ref "JP18") (pin "2") (pinfunction "-_2") (pintype "bidirectional"))
      (node (ref "R53") (pin "2") (pinfunction "2_2") (pintype "passive"))
      (node (ref "U31") (pin "P$4") (pinfunction "P$4_P$4") (pintype "bidirectional"))
    )
    (net (code "40") (name "BTN_PIN1_6") (class "Default")
      (node (ref "D33") (pin "A") (pinfunction "A_A") (pintype "bidirectional"))
      (node (ref "JP19") (pin "2") (pinfunction "-_2") (pintype "bidirectional"))
      (node (ref "R57") (pin "2") (pinfunction "2_2") (pintype "passive"))
      (node (ref "U32") (pin "P$4") (pinfunction "P$4_P$4") (pintype "bidirectional"))
    )
    (net (code "41") (name "BTN_PIN1_7") (class "Default")
      (node (ref "D35") (pin "A") (pinfunction "A_A") (pintype "bidirectional"))
      (node (ref "JP20") (pin "2") (pinfunction "-_2") (pintype "bidirectional"))
      (node (ref "R61") (pin "2") (pinfunction "2_2") (pintype "passive"))
      (node (ref "U33") (pin "P$4") (pinfunction "P$4_P$4") (pintype "bidirectional"))
    )
    (net (code "42") (name "BTN_PIN3_0") (class "Default")
      (node (ref "D5") (pin "A") (pinfunction "A_A") (pintype "bidirectional"))
      (node (ref "JP8") (pin "1") (pinfunction "+_1") (pintype "bidirectional"))
      (node (ref "R25") (pin "2") (pinfunction "2_2") (pintype "passive"))
      (node (ref "U4") (pin "P$3") (pinfunction "P$3_P$3") (pintype "bidirectional"))
    )
    (net (code "43") (name "BTN_PIN3_1") (class "Default")
      (node (ref "D19") (pin "A") (pinfunction "A_A") (pintype "bidirectional"))
      (node (ref "JP10") (pin "1") (pinfunction "+_1") (pintype "bidirectional"))
      (node (ref "R29") (pin "2") (pinfunction "2_2") (pintype "passive"))
      (node (ref "U5") (pin "P$3") (pinfunction "P$3_P$3") (pintype "bidirectional"))
    )
    (net (code "44") (name "BTN_PIN3_2") (class "Default")
      (node (ref "D21") (pin "A") (pinfunction "A_A") (pintype "bidirectional"))
      (node (ref "JP12") (pin "1") (pinfunction "+_1") (pintype "bidirectional"))
      (node (ref "R39") (pin "2") (pinfunction "2_2") (pintype "passive"))
      (node (ref "U14") (pin "P$3") (pinfunction "P$3_P$3") (pintype "bidirectional"))
    )
    (net (code "45") (name "BTN_PIN3_3") (class "Default")
      (node (ref "D27") (pin "A") (pinfunction "A_A") (pintype "bidirectional"))
      (node (ref "JP13") (pin "1") (pinfunction "+_1") (pintype "bidirectional"))
      (node (ref "R43") (pin "2") (pinfunction "2_2") (pintype "passive"))
      (node (ref "U19") (pin "P$3") (pinfunction "P$3_P$3") (pintype "bidirectional"))
    )
    (net (code "46") (name "BTN_PIN3_4") (class "Default")
      (node (ref "D29") (pin "A") (pinfunction "A_A") (pintype "bidirectional"))
      (node (ref "JP14") (pin "1") (pinfunction "+_1") (pintype "bidirectional"))
      (node (ref "R47") (pin "2") (pinfunction "2_2") (pintype "passive"))
      (node (ref "U20") (pin "P$3") (pinfunction "P$3_P$3") (pintype "bidirectional"))
    )
    (net (code "47") (name "BTN_PIN3_5") (class "Default")
      (node (ref "D32") (pin "A") (pinfunction "A_A") (pintype "bidirectional"))
      (node (ref "JP18") (pin "1") (pinfunction "+_1") (pintype "bidirectional"))
      (node (ref "R55") (pin "2") (pinfunction "2_2") (pintype "passive"))
      (node (ref "U31") (pin "P$3") (pinfunction "P$3_P$3") (pintype "bidirectional"))
    )
    (net (code "48") (name "BTN_PIN3_6") (class "Default")
      (node (ref "D34") (pin "A") (pinfunction "A_A") (pintype "bidirectional"))
      (node (ref "JP19") (pin "1") (pinfunction "+_1") (pintype "bidirectional"))
      (node (ref "R59") (pin "2") (pinfunction "2_2") (pintype "passive"))
      (node (ref "U32") (pin "P$3") (pinfunction "P$3_P$3") (pintype "bidirectional"))
    )
    (net (code "49") (name "BTN_PIN3_7") (class "Default")
      (node (ref "D36") (pin "A") (pinfunction "A_A") (pintype "bidirectional"))
      (node (ref "JP20") (pin "1") (pinfunction "+_1") (pintype "bidirectional"))
      (node (ref "R63") (pin "2") (pinfunction "2_2") (pintype "passive"))
      (node (ref "U33") (pin "P$3") (pinfunction "P$3_P$3") (pintype "bidirectional"))
    )
    (net (code "50") (name "BTN_UP_CAP0") (class "Default")
      (node (ref "C6") (pin "1") (pinfunction "1_1") (pintype "passive"))
      (node (ref "D4") (pin "K") (pinfunction "K_K") (pintype "bidirectional"))
      (node (ref "Q5") (pin "G") (pinfunction "G_G") (pintype "bidirectional"))
      (node (ref "Q6") (pin "D") (pinfunction "D_D") (pintype "bidirectional"))
    )
    (net (code "51") (name "BTN_UP_CAP1") (class "Default")
      (node (ref "C8") (pin "1") (pinfunction "1_1") (pintype "passive"))
      (node (ref "D18") (pin "K") (pinfunction "K_K") (pintype "bidirectional"))
      (node (ref "Q10") (pin "D") (pinfunction "D_D") (pintype "bidirectional"))
      (node (ref "Q9") (pin "G") (pinfunction "G_G") (pintype "bidirectional"))
    )
    (net (code "52") (name "BTN_UP_CAP2") (class "Default")
      (node (ref "C28") (pin "1") (pinfunction "1_1") (pintype "passive"))
      (node (ref "D20") (pin "K") (pinfunction "K_K") (pintype "bidirectional"))
      (node (ref "Q13") (pin "G") (pinfunction "G_G") (pintype "bidirectional"))
      (node (ref "Q14") (pin "D") (pinfunction "D_D") (pintype "bidirectional"))
    )
    (net (code "53") (name "BTN_UP_CAP3") (class "Default")
      (node (ref "C30") (pin "1") (pinfunction "1_1") (pintype "passive"))
      (node (ref "D26") (pin "K") (pinfunction "K_K") (pintype "bidirectional"))
      (node (ref "Q17") (pin "G") (pinfunction "G_G") (pintype "bidirectional"))
      (node (ref "Q18") (pin "D") (pinfunction "D_D") (pintype "bidirectional"))
    )
    (net (code "54") (name "BTN_UP_CAP4") (class "Default")
      (node (ref "C32") (pin "1") (pinfunction "1_1") (pintype "passive"))
      (node (ref "D28") (pin "K") (pinfunction "K_K") (pintype "bidirectional"))
      (node (ref "Q21") (pin "G") (pinfunction "G_G") (pintype "bidirectional"))
      (node (ref "Q22") (pin "D") (pinfunction "D_D") (pintype "bidirectional"))
    )
    (net (code "55") (name "BTN_UP_CAP5") (class "Default")
      (node (ref "C55") (pin "1") (pinfunction "1_1") (pintype "passive"))
      (node (ref "D31") (pin "K") (pinfunction "K_K") (pintype "bidirectional"))
      (node (ref "Q25") (pin "G") (pinfunction "G_G") (pintype "bidirectional"))
      (node (ref "Q26") (pin "D") (pinfunction "D_D") (pintype "bidirectional"))
    )
    (net (code "56") (name "BTN_UP_CAP6") (class "Default")
      (node (ref "C57") (pin "1") (pinfunction "1_1") (pintype "passive"))
      (node (ref "D33") (pin "K") (pinfunction "K_K") (pintype "bidirectional"))
      (node (ref "Q29") (pin "G") (pinfunction "G_G") (pintype "bidirectional"))
      (node (ref "Q30") (pin "D") (pinfunction "D_D") (pintype "bidirectional"))
    )
    (net (code "57") (name "BTN_UP_CAP7") (class "Default")
      (node (ref "C59") (pin "1") (pinfunction "1_1") (pintype "passive"))
      (node (ref "D35") (pin "K") (pinfunction "K_K") (pintype "bidirectional"))
      (node (ref "Q33") (pin "G") (pinfunction "G_G") (pintype "bidirectional"))
      (node (ref "Q34") (pin "D") (pinfunction "D_D") (pintype "bidirectional"))
    )
    (net (code "58") (name "BTN_UP_CLR0") (class "Default")
      (node (ref "Q6") (pin "G") (pinfunction "G_G") (pintype "bidirectional"))
      (node (ref "R5") (pin "2") (pinfunction "2_2") (pintype "passive"))
      (node (ref "U30") (pin "P$2") (pinfunction "S1_P$2") (pintype "bidirectional"))
    )
    (net (code "59") (name "BTN_UP_CLR1") (class "Default")
      (node (ref "Q10") (pin "G") (pinfunction "G_G") (pintype "bidirectional"))
      (node (ref "R28") (pin "2") (pinfunction "2_2") (pintype "passive"))
      (node (ref "U30") (pin "P$3") (pinfunction "S2_P$3") (pintype "bidirectional"))
    )
    (net (code "60") (name "BTN_UP_CLR2") (class "Default")
      (node (ref "Q14") (pin "G") (pinfunction "G_G") (pintype "bidirectional"))
      (node (ref "R38") (pin "2") (pinfunction "2_2") (pintype "passive"))
      (node (ref "U30") (pin "P$4") (pinfunction "S3_P$4") (pintype "bidirectional"))
    )
    (net (code "61") (name "BTN_UP_CLR3") (class "Default")
      (node (ref "Q18") (pin "G") (pinfunction "G_G") (pintype "bidirectional"))
      (node (ref "R42") (pin "2") (pinfunction "2_2") (pintype "passive"))
      (node (ref "U30") (pin "P$5") (pinfunction "S4_P$5") (pintype "bidirectional"))
    )
    (net (code "62") (name "BTN_UP_CLR4") (class "Default")
      (node (ref "Q22") (pin "G") (pinfunction "G_G") (pintype "bidirectional"))
      (node (ref "R46") (pin "2") (pinfunction "2_2") (pintype "passive"))
      (node (ref "U30") (pin "P$10") (pinfunction "S5_P$10") (pintype "bidirectional"))
    )
    (net (code "63") (name "BTN_UP_CLR5") (class "Default")
      (node (ref "Q26") (pin "G") (pinfunction "G_G") (pintype "bidirectional"))
      (node (ref "R54") (pin "2") (pinfunction "2_2") (pintype "passive"))
      (node (ref "U30") (pin "P$9") (pinfunction "S6_P$9") (pintype "bidirectional"))
    )
    (net (code "64") (name "BTN_UP_CLR6") (class "Default")
      (node (ref "Q30") (pin "G") (pinfunction "G_G") (pintype "bidirectional"))
      (node (ref "R58") (pin "2") (pinfunction "2_2") (pintype "passive"))
      (node (ref "U30") (pin "P$8") (pinfunction "S7_P$8") (pintype "bidirectional"))
    )
    (net (code "65") (name "BTN_UP_CLR7") (class "Default")
      (node (ref "Q34") (pin "G") (pinfunction "G_G") (pintype "bidirectional"))
      (node (ref "R62") (pin "2") (pinfunction "2_2") (pintype "passive"))
      (node (ref "U30") (pin "P$7") (pinfunction "S8_P$7") (pintype "bidirectional"))
    )
    (net (code "66") (name "BTN_UP_CLR_MUX_D") (class "Default")
      (node (ref "U1") (pin "D0") (pinfunction "(SLSCK/SLSCL/CLKOUT)D0_D0") (pintype "bidirectional"))
      (node (ref "U30") (pin "P$6") (pinfunction "D_P$6") (pintype "bidirectional"))
    )
    (net (code "67") (name "BTN_UP_SENSE0") (class "Default")
      (node (ref "Q5") (pin "D") (pinfunction "D_D") (pintype "bidirectional"))
      (node (ref "U35") (pin "P$2") (pinfunction "S1_P$2") (pintype "bidirectional"))
    )
    (net (code "68") (name "BTN_UP_SENSE1") (class "Default")
      (node (ref "Q9") (pin "D") (pinfunction "D_D") (pintype "bidirectional"))
      (node (ref "U35") (pin "P$3") (pinfunction "S2_P$3") (pintype "bidirectional"))
    )
    (net (code "69") (name "BTN_UP_SENSE2") (class "Default")
      (node (ref "Q13") (pin "D") (pinfunction "D_D") (pintype "bidirectional"))
      (node (ref "U35") (pin "P$4") (pinfunction "S3_P$4") (pintype "bidirectional"))
    )
    (net (code "70") (name "BTN_UP_SENSE3") (class "Default")
      (node (ref "Q17") (pin "D") (pinfunction "D_D") (pintype "bidirectional"))
      (node (ref "U35") (pin "P$5") (pinfunction "S4_P$5") (pintype "bidirectional"))
    )
    (net (code "71") (name "BTN_UP_SENSE4") (class "Default")
      (node (ref "Q21") (pin "D") (pinfunction "D_D") (pintype "bidirectional"))
      (node (ref "U35") (pin "P$10") (pinfunction "S5_P$10") (pintype "bidirectional"))
    )
    (net (code "72") (name "BTN_UP_SENSE5") (class "Default")
      (node (ref "Q25") (pin "D") (pinfunction "D_D") (pintype "bidirectional"))
      (node (ref "U35") (pin "P$9") (pinfunction "S6_P$9") (pintype "bidirectional"))
    )
    (net (code "73") (name "BTN_UP_SENSE6") (class "Default")
      (node (ref "Q29") (pin "D") (pinfunction "D_D") (pintype "bidirectional"))
      (node (ref "U35") (pin "P$8") (pinfunction "S7_P$8") (pintype "bidirectional"))
    )
    (net (code "74") (name "BTN_UP_SENSE7") (class "Default")
      (node (ref "Q33") (pin "D") (pinfunction "D_D") (pintype "bidirectional"))
      (node (ref "U35") (pin "P$7") (pinfunction "S8_P$7") (pintype "bidirectional"))
    )
    (net (code "75") (name "BTN_UP_SENSE_MUX_D") (class "Default")
      (node (ref "R50") (pin "1") (pinfunction "1_1") (pintype "passive"))
      (node (ref "U1") (pin "D2") (pinfunction "(SLSDI)D2_D2") (pintype "bidirectional"))
      (node (ref "U35") (pin "P$6") (pinfunction "D_P$6") (pintype "bidirectional"))
    )
    (net (code "76") (name "BUTTON_MUX_A0") (class "Default")
      (node (ref "U1") (pin "~D18") (pinfunction "(CMPIN1/SCCIO)~{D18}_~D18") (pintype "bidirectional"))
      (node (ref "U30") (pin "P$15") (pinfunction "A0_P$15") (pintype "bidirectional"))
      (node (ref "U34") (pin "P$15") (pinfunction "A0_P$15") (pintype "bidirectional"))
      (node (ref "U35") (pin "P$15") (pinfunction "A0_P$15") (pintype "bidirectional"))
      (node (ref "U36") (pin "P$15") (pinfunction "A0_P$15") (pintype "bidirectional"))
    )
    (net (code "77") (name "BUTTON_MUX_A1") (class "Default")
      (node (ref "U1") (pin "D41") (pinfunction "(BLEIF_IRQ/SWO/I2SWCLK)D41_D41") (pintype "bidirectional"))
      (node (ref "U30") (pin "P$14") (pinfunction "A1_P$14") (pintype "bidirectional"))
      (node (ref "U34") (pin "P$14") (pinfunction "A1_P$14") (pintype "bidirectional"))
      (node (ref "U35") (pin "P$14") (pinfunction "A1_P$14") (pintype "bidirectional"))
      (node (ref "U36") (pin "P$14") (pinfunction "A1_P$14") (pintype "bidirectional"))
    )
    (net (code "78") (name "BUTTON_MUX_A2") (class "Default")
      (node (ref "U1") (pin "~D45") (pinfunction "(SWO/I2SDAT/PDMDATA)~{D45}_~D45") (pintype "bidirectional"))
      (node (ref "U30") (pin "P$13") (pinfunction "A2_P$13") (pintype "bidirectional"))
      (node (ref "U34") (pin "P$13") (pinfunction "A2_P$13") (pintype "bidirectional"))
      (node (ref "U35") (pin "P$13") (pinfunction "A2_P$13") (pintype "bidirectional"))
      (node (ref "U36") (pin "P$13") (pinfunction "A2_P$13") (pintype "bidirectional"))
    )
    (net (code "79") (name "BUTTON_MUX_EN") (class "Default")
      (node (ref "U1") (pin "D17") (pinfunction "(CMPRF1/TRIG1/SCCCLK)D17_D17") (pintype "bidirectional"))
      (node (ref "U30") (pin "P$16") (pinfunction "EN_P$16") (pintype "bidirectional"))
      (node (ref "U34") (pin "P$16") (pinfunction "EN_P$16") (pintype "bidirectional"))
      (node (ref "U35") (pin "P$16") (pinfunction "EN_P$16") (pintype "bidirectional"))
      (node (ref "U36") (pin "P$16") (pinfunction "EN_P$16") (pintype "bidirectional"))
    )
    (net (code "80") (name "CP2102_RX_MCU_TX") (class "Default")
      (node (ref "JP16") (pin "1") (pinfunction "1_1") (pintype "passive"))
      (node (ref "U1") (pin "TXO-0") (pinfunction "~{D48(TX0/SCL5/SCK5})_TXO-0") (pintype "bidirectional"))
    )
    (net (code "81") (name "CP2102_TX_MCU_RX") (class "Default")
      (node (ref "JP15") (pin "1") (pinfunction "1_1") (pintype "passive"))
      (node (ref "U1") (pin "RXI-0") (pinfunction "~{D49(RX0/SDA5/SDI5})_RXI-0") (pintype "bidirectional"))
    )
    (net (code "82") (name "CP2102_VDD_OUT") (class "Default")
      (node (ref "C3") (pin "1") (pinfunction "1_1") (pintype "passive"))
      (node (ref "C4") (pin "1") (pinfunction "1_1") (pintype "passive"))
      (node (ref "C40") (pin "1") (pinfunction "1_1") (pintype "passive"))
      (node (ref "C5") (pin "1") (pinfunction "1_1") (pintype "passive"))
      (node (ref "R75") (pin "1") (pinfunction "1_1") (pintype "passive"))
      (node (ref "U2") (pin "6") (pinfunction "VDD_6") (pintype "power_in"))
      (node (ref "U21") (pin "1") (pinfunction "VCCA_1") (pintype "bidirectional"))
      (node (ref "U3") (pin "1") (pinfunction "VCCA_1") (pintype "bidirectional"))
      (node (ref "U3") (pin "5") (pinfunction "DIR_5") (pintype "bidirectional"))
    )
    (net (code "83") (name "D+") (class "Default")
      (node (ref "J1") (pin "3") (pinfunction "3_3") (pintype "bidirectional"))
      (node (ref "TVS1") (pin "P$2") (pinfunction "D2_P$2") (pintype "bidirectional"))
      (node (ref "U2") (pin "4") (pinfunction "D+_4") (pintype "bidirectional"))
    )
    (net (code "84") (name "D-") (class "Default")
      (node (ref "J1") (pin "2") (pinfunction "2_2") (pintype "bidirectional"))
      (node (ref "TVS1") (pin "P$1") (pinfunction "D1_P$1") (pintype "bidirectional"))
      (node (ref "U2") (pin "5") (pinfunction "D-_5") (pintype "bidirectional"))
    )
    (net (code "85") (name "D14{slash}SDA") (class "Default")
      (node (ref "JP5") (pin "2") (pinfunction "2_2") (pintype "passive"))
      (node (ref "U1") (pin "D40") (pinfunction "(SDA4/SDI4/RX1)D40_D40") (pintype "bidirectional"))
    )
    (net (code "86") (name "DIRSENSE0") (class "Default")
      (node (ref "U37") (pin "2") (pinfunction "S1_2") (pintype "bidirectional"))
      (node (ref "U9") (pin "D") (pinfunction "D_D") (pintype "bidirectional"))
    )
    (net (code "87") (name "DIRSENSE1") (class "Default")
      (node (ref "U13") (pin "D") (pinfunction "D_D") (pintype "bidirectional"))
      (node (ref "U37") (pin "9") (pinfunction "S2_9") (pintype "bidirectional"))
    )
    (net (code "88") (name "DIRSENSE2") (class "Default")
      (node (ref "U18") (pin "D") (pinfunction "D_D") (pintype "bidirectional"))
      (node (ref "U37") (pin "4") (pinfunction "S3_4") (pintype "bidirectional"))
    )
    (net (code "89") (name "DIRSENSE3") (class "Default")
      (node (ref "U26") (pin "D") (pinfunction "D_D") (pintype "bidirectional"))
      (node (ref "U37") (pin "7") (pinfunction "S4_7") (pintype "bidirectional"))
    )
    (net (code "90") (name "DIRSENSE_MUX_D") (class "Default")
      (node (ref "R52") (pin "1") (pinfunction "1_1") (pintype "passive"))
      (node (ref "U1") (pin "D15") (pinfunction "(ADCD1N/RX1/PDMDATA)D15_D15") (pintype "bidirectional"))
      (node (ref "U37") (pin "8") (pinfunction "D_8") (pintype "bidirectional"))
    )
    (net (code "91") (name "GND") (class "Default")
      (node (ref "C1") (pin "2") (pinfunction "2_2") (pintype "passive"))
      (node (ref "C10") (pin "2") (pinfunction "2_2") (pintype "passive"))
      (node (ref "C11") (pin "2") (pinfunction "2_2") (pintype "passive"))
      (node (ref "C12") (pin "2") (pinfunction "2_2") (pintype "passive"))
      (node (ref "C13") (pin "-") (pinfunction "-_-") (pintype "passive"))
      (node (ref "C14") (pin "2") (pinfunction "2_2") (pintype "passive"))
      (node (ref "C15") (pin "2") (pinfunction "2_2") (pintype "passive"))
      (node (ref "C16") (pin "2") (pinfunction "2_2") (pintype "passive"))
      (node (ref "C17") (pin "2") (pinfunction "2_2") (pintype "passive"))
      (node (ref "C18") (pin "2") (pinfunction "2_2") (pintype "passive"))
      (node (ref "C19") (pin "-") (pinfunction "-_-") (pintype "passive"))
      (node (ref "C2") (pin "2") (pinfunction "2_2") (pintype "passive"))
      (node (ref "C20") (pin "2") (pinfunction "2_2") (pintype "passive"))
      (node (ref "C21") (pin "2") (pinfunction "2_2") (pintype "passive"))
      (node (ref "C22") (pin "2") (pinfunction "2_2") (pintype "passive"))
      (node (ref "C23") (pin "2") (pinfunction "2_2") (pintype "passive"))
      (node (ref "C24") (pin "2") (pinfunction "2_2") (pintype "passive"))
      (node (ref "C25") (pin "-") (pinfunction "-_-") (pintype "passive"))
      (node (ref "C26") (pin "2") (pinfunction "2_2") (pintype "passive"))
      (node (ref "C27") (pin "2") (pinfunction "2_2") (pintype "passive"))
      (node (ref "C28") (pin "2") (pinfunction "2_2") (pintype "passive"))
      (node (ref "C29") (pin "2") (pinfunction "2_2") (pintype "passive"))
      (node (ref "C3") (pin "2") (pinfunction "2_2") (pintype "passive"))
      (node (ref "C30") (pin "2") (pinfunction "2_2") (pintype "passive"))
      (node (ref "C31") (pin "2") (pinfunction "2_2") (pintype "passive"))
      (node (ref "C32") (pin "2") (pinfunction "2_2") (pintype "passive"))
      (node (ref "C33") (pin "2") (pinfunction "2_2") (pintype "passive"))
      (node (ref "C34") (pin "2") (pinfunction "2_2") (pintype "passive"))
      (node (ref "C35") (pin "2") (pinfunction "2_2") (pintype "passive"))
      (node (ref "C36") (pin "2") (pinfunction "2_2") (pintype "passive"))
      (node (ref "C37") (pin "-") (pinfunction "-_-") (pintype "passive"))
      (node (ref "C38") (pin "2") (pinfunction "2_2") (pintype "passive"))
      (node (ref "C39") (pin "2") (pinfunction "2_2") (pintype "passive"))
      (node (ref "C4") (pin "2") (pinfunction "2_2") (pintype "passive"))
      (node (ref "C40") (pin "2") (pinfunction "2_2") (pintype "passive"))
      (node (ref "C41") (pin "2") (pinfunction "2_2") (pintype "passive"))
      (node (ref "C42") (pin "2") (pinfunction "2_2") (pintype "passive"))
      (node (ref "C43") (pin "2") (pinfunction "2_2") (pintype "passive"))
      (node (ref "C44") (pin "2") (pinfunction "2_2") (pintype "passive"))
      (node (ref "C45") (pin "2") (pinfunction "2_2") (pintype "passive"))
      (node (ref "C46") (pin "2") (pinfunction "2_2") (pintype "passive"))
      (node (ref "C48") (pin "2") (pinfunction "2_2") (pintype "passive"))
      (node (ref "C49") (pin "2") (pinfunction "2_2") (pintype "passive"))
      (node (ref "C5") (pin "2") (pinfunction "2_2") (pintype "passive"))
      (node (ref "C52") (pin "2") (pinfunction "2_2") (pintype "passive"))
      (node (ref "C53") (pin "2") (pinfunction "2_2") (pintype "passive"))
      (node (ref "C54") (pin "2") (pinfunction "2_2") (pintype "passive"))
      (node (ref "C55") (pin "2") (pinfunction "2_2") (pintype "passive"))
      (node (ref "C56") (pin "2") (pinfunction "2_2") (pintype "passive"))
      (node (ref "C57") (pin "2") (pinfunction "2_2") (pintype "passive"))
      (node (ref "C58") (pin "2") (pinfunction "2_2") (pintype "passive"))
      (node (ref "C59") (pin "2") (pinfunction "2_2") (pintype "passive"))
      (node (ref "C6") (pin "2") (pinfunction "2_2") (pintype "passive"))
      (node (ref "C60") (pin "2") (pinfunction "2_2") (pintype "passive"))
      (node (ref "C61") (pin "2") (pinfunction "2_2") (pintype "passive"))
      (node (ref "C62") (pin "2") (pinfunction "2_2") (pintype "passive"))
      (node (ref "C63") (pin "2") (pinfunction "2_2") (pintype "passive"))
      (node (ref "C7") (pin "2") (pinfunction "2_2") (pintype "passive"))
      (node (ref "C8") (pin "2") (pinfunction "2_2") (pintype "passive"))
      (node (ref "C9") (pin "2") (pinfunction "2_2") (pintype "passive"))
      (node (ref "D11") (pin "A") (pinfunction "A_A") (pintype "passive"))
      (node (ref "D12") (pin "A") (pinfunction "A_A") (pintype "passive"))
      (node (ref "D13") (pin "A") (pinfunction "A_A") (pintype "passive"))
      (node (ref "D15") (pin "A") (pinfunction "A_A") (pintype "passive"))
      (node (ref "D16") (pin "A") (pinfunction "A_A") (pintype "passive"))
      (node (ref "D17") (pin "A") (pinfunction "A_A") (pintype "passive"))
      (node (ref "D2") (pin "A") (pinfunction "A_A") (pintype "passive"))
      (node (ref "D23") (pin "A") (pinfunction "A_A") (pintype "passive"))
      (node (ref "D24") (pin "A") (pinfunction "A_A") (pintype "passive"))
      (node (ref "D25") (pin "A") (pinfunction "A_A") (pintype "passive"))
      (node (ref "D3") (pin "A") (pinfunction "A_A") (pintype "passive"))
      (node (ref "D30") (pin "A") (pinfunction "A_A") (pintype "passive"))
      (node (ref "D37") (pin "A") (pinfunction "A_A") (pintype "passive"))
      (node (ref "D38") (pin "A") (pinfunction "A_A") (pintype "passive"))
      (node (ref "D7") (pin "A") (pinfunction "A_A") (pintype "passive"))
      (node (ref "D8") (pin "A") (pinfunction "A_A") (pintype "passive"))
      (node (ref "D9") (pin "A") (pinfunction "A_A") (pintype "passive"))
      (node (ref "J1") (pin "5") (pinfunction "5_5") (pintype "power_in"))
      (node (ref "J2") (pin "P$3") (pinfunction "P$3_P$3") (pintype "bidirectional"))
      (node (ref "J2") (pin "P$5") (pinfunction "P$5_P$5") (pintype "bidirectional"))
      (node (ref "J2") (pin "P$9") (pinfunction "P$9_P$9") (pintype "bidirectional"))
      (node (ref "JP21") (pin "3") (pinfunction "3_3") (pintype "passive"))
      (node (ref "JP21") (pin "4") (pinfunction "4_4") (pintype "passive"))
      (node (ref "JP5") (pin "4") (pinfunction "4_4") (pintype "passive"))
      (node (ref "JP7") (pin "6") (pinfunction "6_6") (pintype "passive"))
      (node (ref "JP7") (pin "7") (pinfunction "7_7") (pintype "passive"))
      (node (ref "LED1") (pin "C") (pinfunction "C_C") (pintype "passive"))
      (node (ref "LED2") (pin "C") (pinfunction "C_C") (pintype "passive"))
      (node (ref "LED3") (pin "C") (pinfunction "C_C") (pintype "passive"))
      (node (ref "Q10") (pin "S") (pinfunction "S_S") (pintype "bidirectional"))
      (node (ref "Q11") (pin "S") (pinfunction "S_S") (pintype "bidirectional"))
      (node (ref "Q12") (pin "S") (pinfunction "S_S") (pintype "bidirectional"))
      (node (ref "Q13") (pin "S") (pinfunction "S_S") (pintype "bidirectional"))
      (node (ref "Q14") (pin "S") (pinfunction "S_S") (pintype "bidirectional"))
      (node (ref "Q15") (pin "S") (pinfunction "S_S") (pintype "bidirectional"))
      (node (ref "Q16") (pin "S") (pinfunction "S_S") (pintype "bidirectional"))
      (node (ref "Q17") (pin "S") (pinfunction "S_S") (pintype "bidirectional"))
      (node (ref "Q18") (pin "S") (pinfunction "S_S") (pintype "bidirectional"))
      (node (ref "Q19") (pin "S") (pinfunction "S_S") (pintype "bidirectional"))
      (node (ref "Q20") (pin "S") (pinfunction "S_S") (pintype "bidirectional"))
      (node (ref "Q21") (pin "S") (pinfunction "S_S") (pintype "bidirectional"))
      (node (ref "Q22") (pin "S") (pinfunction "S_S") (pintype "bidirectional"))
      (node (ref "Q23") (pin "S") (pinfunction "S_S") (pintype "bidirectional"))
      (node (ref "Q24") (pin "S") (pinfunction "S_S") (pintype "bidirectional"))
      (node (ref "Q25") (pin "S") (pinfunction "S_S") (pintype "bidirectional"))
      (node (ref "Q26") (pin "S") (pinfunction "S_S") (pintype "bidirectional"))
      (node (ref "Q27") (pin "S") (pinfunction "S_S") (pintype "bidirectional"))
      (node (ref "Q28") (pin "S") (pinfunction "S_S") (pintype "bidirectional"))
      (node (ref "Q29") (pin "S") (pinfunction "S_S") (pintype "bidirectional"))
      (node (ref "Q30") (pin "S") (pinfunction "S_S") (pintype "bidirectional"))
      (node (ref "Q31") (pin "S") (pinfunction "S_S") (pintype "bidirectional"))
      (node (ref "Q32") (pin "S") (pinfunction "S_S") (pintype "bidirectional"))
      (node (ref "Q33") (pin "S") (pinfunction "S_S") (pintype "bidirectional"))
      (node (ref "Q34") (pin "S") (pinfunction "S_S") (pintype "bidirectional"))
      (node (ref "Q35") (pin "S") (pinfunction "S_S") (pintype "bidirectional"))
      (node (ref "Q36") (pin "S") (pinfunction "S_S") (pintype "bidirectional"))
      (node (ref "Q5") (pin "S") (pinfunction "S_S") (pintype "bidirectional"))
      (node (ref "Q6") (pin "S") (pinfunction "S_S") (pintype "bidirectional"))
      (node (ref "Q7") (pin "S") (pinfunction "S_S") (pintype "bidirectional"))
      (node (ref "Q8") (pin "S") (pinfunction "S_S") (pintype "bidirectional"))
      (node (ref "Q9") (pin "S") (pinfunction "S_S") (pintype "bidirectional"))
      (node (ref "R1") (pin "1") (pinfunction "1_1") (pintype "passive"))
      (node (ref "R12") (pin "1") (pinfunction "1_1") (pintype "passive"))
      (node (ref "R14") (pin "1") (pinfunction "1_1") (pintype "passive"))
      (node (ref "R18") (pin "1") (pinfunction "1_1") (pintype "passive"))
      (node (ref "R2") (pin "1") (pinfunction "1_1") (pintype "passive"))
      (node (ref "R20") (pin "1") (pinfunction "1_1") (pintype "passive"))
      (node (ref "R24") (pin "1") (pinfunction "1_1") (pintype "passive"))
      (node (ref "R25") (pin "1") (pinfunction "1_1") (pintype "passive"))
      (node (ref "R26") (pin "1") (pinfunction "1_1") (pintype "passive"))
      (node (ref "R27") (pin "1") (pinfunction "1_1") (pintype "passive"))
      (node (ref "R28") (pin "1") (pinfunction "1_1") (pintype "passive"))
      (node (ref "R29") (pin "1") (pinfunction "1_1") (pintype "passive"))
      (node (ref "R30") (pin "1") (pinfunction "1_1") (pintype "passive"))
      (node (ref "R32") (pin "1") (pinfunction "1_1") (pintype "passive"))
      (node (ref "R36") (pin "1") (pinfunction "1_1") (pintype "passive"))
      (node (ref "R37") (pin "1") (pinfunction "1_1") (pintype "passive"))
      (node (ref "R38") (pin "1") (pinfunction "1_1") (pintype "passive"))
      (node (ref "R39") (pin "1") (pinfunction "1_1") (pintype "passive"))
      (node (ref "R4") (pin "1") (pinfunction "1_1") (pintype "passive"))
      (node (ref "R40") (pin "1") (pinfunction "1_1") (pintype "passive"))
      (node (ref "R41") (pin "1") (pinfunction "1_1") (pintype "passive"))
      (node (ref "R42") (pin "1") (pinfunction "1_1") (pintype "passive"))
      (node (ref "R43") (pin "1") (pinfunction "1_1") (pintype "passive"))
      (node (ref "R44") (pin "1") (pinfunction "1_1") (pintype "passive"))
      (node (ref "R45") (pin "1") (pinfunction "1_1") (pintype "passive"))
      (node (ref "R46") (pin "1") (pinfunction "1_1") (pintype "passive"))
      (node (ref "R47") (pin "1") (pinfunction "1_1") (pintype "passive"))
      (node (ref "R48") (pin "1") (pinfunction "1_1") (pintype "passive"))
      (node (ref "R5") (pin "1") (pinfunction "1_1") (pintype "passive"))
      (node (ref "R53") (pin "1") (pinfunction "1_1") (pintype "passive"))
      (node (ref "R54") (pin "1") (pinfunction "1_1") (pintype "passive"))
      (node (ref "R55") (pin "1") (pinfunction "1_1") (pintype "passive"))
      (node (ref "R56") (pin "1") (pinfunction "1_1") (pintype "passive"))
      (node (ref "R57") (pin "1") (pinfunction "1_1") (pintype "passive"))
      (node (ref "R58") (pin "1") (pinfunction "1_1") (pintype "passive"))
      (node (ref "R59") (pin "1") (pinfunction "1_1") (pintype "passive"))
      (node (ref "R60") (pin "1") (pinfunction "1_1") (pintype "passive"))
      (node (ref "R61") (pin "1") (pinfunction "1_1") (pintype "passive"))
      (node (ref "R62") (pin "1") (pinfunction "1_1") (pintype "passive"))
      (node (ref "R63") (pin "1") (pinfunction "1_1") (pintype "passive"))
      (node (ref "R64") (pin "1") (pinfunction "1_1") (pintype "passive"))
      (node (ref "R65") (pin "1") (pinfunction "1_1") (pintype "passive"))
      (node (ref "R67") (pin "1") (pinfunction "1_1") (pintype "passive"))
      (node (ref "R69") (pin "1") (pinfunction "1_1") (pintype "passive"))
      (node (ref "R71") (pin "1") (pinfunction "1_1") (pintype "passive"))
      (node (ref "R8") (pin "1") (pinfunction "1_1") (pintype "passive"))
      (node (ref "SW1") (pin "P$1") (pinfunction "P$1_P$1") (pintype "bidirectional"))
      (node (ref "SW1") (pin "P$2") (pinfunction "P$2_P$2") (pintype "bidirectional"))
      (node (ref "SW2") (pin "P$3") (pinfunction "P$3_P$3") (pintype "bidirectional"))
      (node (ref "SW2") (pin "P$4") (pinfunction "P$4_P$4") (pintype "bidirectional"))
      (node (ref "SW3") (pin "P$3") (pinfunction "P$3_P$3") (pintype "bidirectional"))
      (node (ref "SW3") (pin "P$4") (pinfunction "P$4_P$4") (pintype "bidirectional"))
      (node (ref "TVS1") (pin "PAD") (pinfunction "GND_PAD") (pintype "bidirectional"))
      (node (ref "U1") (pin "GND@1") (pinfunction "GND*6_GND@1") (pintype "bidirectional"))
      (node (ref "U1") (pin "GND@22") (pinfunction "GND*6_GND@22") (pintype "bidirectional"))
      (node (ref "U1") (pin "GND@38") (pinfunction "GND*6_GND@38") (pintype "bidirectional"))
      (node (ref "U1") (pin "GND@39") (pinfunction "GND*6_GND@39") (pintype "bidirectional"))
      (node (ref "U1") (pin "GND@47") (pinfunction "GND*6_GND@47") (pintype "bidirectional"))
      (node (ref "U1") (pin "GND@59") (pinfunction "GND*6_GND@59") (pintype "bidirectional"))
      (node (ref "U10") (pin "P$2") (pinfunction "P$2_P$2") (pintype "bidirectional"))
      (node (ref "U11") (pin "P$2") (pinfunction "P$2_P$2") (pintype "bidirectional"))
      (node (ref "U12") (pin "1") (pinfunction "GND_1") (pintype "bidirectional"))
      (node (ref "U12") (pin "2") (pinfunction "GND_2") (pintype "bidirectional"))
      (node (ref "U13") (pin "S") (pinfunction "S_S") (pintype "bidirectional"))
      (node (ref "U14") (pin "P$2") (pinfunction "P$2_P$2") (pintype "bidirectional"))
      (node (ref "U15") (pin "P$2") (pinfunction "P$2_P$2") (pintype "bidirectional"))
      (node (ref "U16") (pin "P$2") (pinfunction "P$2_P$2") (pintype "bidirectional"))
      (node (ref "U17") (pin "1") (pinfunction "GND_1") (pintype "bidirectional"))
      (node (ref "U17") (pin "2") (pinfunction "GND_2") (pintype "bidirectional"))
      (node (ref "U18") (pin "S") (pinfunction "S_S") (pintype "bidirectional"))
      (node (ref "U19") (pin "P$2") (pinfunction "P$2_P$2") (pintype "bidirectional"))
      (node (ref "U2") (pin "3") (pinfunction "GND_3") (pintype "power_in"))
      (node (ref "U2") (pin "EXP") (pinfunction "GND_EXP") (pintype "power_in"))
      (node (ref "U2") (pin "M") (pinfunction "GND_M") (pintype "power_in"))
      (node (ref "U20") (pin "P$2") (pinfunction "P$2_P$2") (pintype "bidirectional"))
      (node (ref "U21") (pin "2") (pinfunction "GND_2") (pintype "bidirectional"))
      (node (ref "U21") (pin "5") (pinfunction "DIR_5") (pintype "bidirectional"))
      (node (ref "U22") (pin "3") (pinfunction "GND_3") (pintype "bidirectional"))
      (node (ref "U23") (pin "P$2") (pinfunction "P$2_P$2") (pintype "bidirectional"))
      (node (ref "U24") (pin "P$2") (pinfunction "P$2_P$2") (pintype "bidirectional"))
      (node (ref "U25") (pin "1") (pinfunction "GND_1") (pintype "bidirectional"))
      (node (ref "U25") (pin "2") (pinfunction "GND_2") (pintype "bidirectional"))
      (node (ref "U26") (pin "S") (pinfunction "S_S") (pintype "bidirectional"))
      (node (ref "U27") (pin "3") (pinfunction "GND_3") (pintype "bidirectional"))
      (node (ref "U28") (pin "3") (pinfunction "GND_3") (pintype "bidirectional"))
      (node (ref "U29") (pin "2") (pinfunction "GND_2") (pintype "bidirectional"))
      (node (ref "U3") (pin "2") (pinfunction "GND_2") (pintype "bidirectional"))
      (node (ref "U30") (pin "P$1") (pinfunction "VSS_P$1") (pintype "bidirectional"))
      (node (ref "U30") (pin "P$12") (pinfunction "GND_P$12") (pintype "bidirectional"))
      (node (ref "U31") (pin "P$2") (pinfunction "P$2_P$2") (pintype "bidirectional"))
      (node (ref "U32") (pin "P$2") (pinfunction "P$2_P$2") (pintype "bidirectional"))
      (node (ref "U33") (pin "P$2") (pinfunction "P$2_P$2") (pintype "bidirectional"))
      (node (ref "U34") (pin "P$1") (pinfunction "VSS_P$1") (pintype "bidirectional"))
      (node (ref "U34") (pin "P$12") (pinfunction "GND_P$12") (pintype "bidirectional"))
      (node (ref "U35") (pin "P$1") (pinfunction "VSS_P$1") (pintype "bidirectional"))
      (node (ref "U35") (pin "P$12") (pinfunction "GND_P$12") (pintype "bidirectional"))
      (node (ref "U36") (pin "P$1") (pinfunction "VSS_P$1") (pintype "bidirectional"))
      (node (ref "U36") (pin "P$12") (pinfunction "GND_P$12") (pintype "bidirectional"))
      (node (ref "U37") (pin "3") (pinfunction "GND_3") (pintype "bidirectional"))
      (node (ref "U4") (pin "P$2") (pinfunction "P$2_P$2") (pintype "bidirectional"))
      (node (ref "U5") (pin "P$2") (pinfunction "P$2_P$2") (pintype "bidirectional"))
      (node (ref "U6") (pin "P$2") (pinfunction "P$2_P$2") (pintype "bidirectional"))
      (node (ref "U7") (pin "P$2") (pinfunction "P$2_P$2") (pintype "bidirectional"))
      (node (ref "U8") (pin "1") (pinfunction "GND_1") (pintype "bidirectional"))
      (node (ref "U8") (pin "2") (pinfunction "GND_2") (pintype "bidirectional"))
      (node (ref "U9") (pin "S") (pinfunction "S_S") (pintype "bidirectional"))
    )
    (net (code "92") (name "ISENSE0") (class "Default")
      (node (ref "C11") (pin "1") (pinfunction "1_1") (pintype "passive"))
      (node (ref "R10") (pin "1") (pinfunction "1_1") (pintype "passive"))
      (node (ref "U27") (pin "2") (pinfunction "S1_2") (pintype "bidirectional"))
    )
    (net (code "93") (name "ISENSE1") (class "Default")
      (node (ref "C17") (pin "1") (pinfunction "1_1") (pintype "passive"))
      (node (ref "R16") (pin "1") (pinfunction "1_1") (pintype "passive"))
      (node (ref "U27") (pin "9") (pinfunction "S2_9") (pintype "bidirectional"))
    )
    (net (code "94") (name "ISENSE2") (class "Default")
      (node (ref "C23") (pin "1") (pinfunction "1_1") (pintype "passive"))
      (node (ref "R22") (pin "1") (pinfunction "1_1") (pintype "passive"))
      (node (ref "U27") (pin "4") (pinfunction "S3_4") (pintype "bidirectional"))
    )
    (net (code "95") (name "ISENSE3") (class "Default")
      (node (ref "C35") (pin "1") (pinfunction "1_1") (pintype "passive"))
      (node (ref "R34") (pin "1") (pinfunction "1_1") (pintype "passive"))
      (node (ref "U27") (pin "7") (pinfunction "S4_7") (pintype "bidirectional"))
    )
    (net (code "96") (name "ISENSE_MUX_D") (class "Default")
      (node (ref "D2") (pin "C") (pinfunction "C_C") (pintype "passive"))
      (node (ref "U1") (pin "~AD13") (pinfunction "~{AD13(I2SBCLK/RX1})_~AD13") (pintype "bidirectional"))
      (node (ref "U27") (pin "8") (pinfunction "D_8") (pintype "bidirectional"))
    )
    (net (code "97") (name "Net-(C15-Pad1)") (class "Default")
      (node (ref "C15") (pin "1") (pinfunction "1_1") (pintype "passive"))
      (node (ref "D8") (pin "C") (pinfunction "C_C") (pintype "passive"))
      (node (ref "R11") (pin "1") (pinfunction "1_1") (pintype "passive"))
      (node (ref "R12") (pin "2") (pinfunction "2_2") (pintype "passive"))
      (node (ref "U9") (pin "G") (pinfunction "G_G") (pintype "bidirectional"))
    )
    (net (code "98") (name "Net-(C21-Pad1)") (class "Default")
      (node (ref "C21") (pin "1") (pinfunction "1_1") (pintype "passive"))
      (node (ref "D12") (pin "C") (pinfunction "C_C") (pintype "passive"))
      (node (ref "R17") (pin "1") (pinfunction "1_1") (pintype "passive"))
      (node (ref "R18") (pin "2") (pinfunction "2_2") (pintype "passive"))
      (node (ref "U13") (pin "G") (pinfunction "G_G") (pintype "bidirectional"))
    )
    (net (code "99") (name "Net-(C27-Pad1)") (class "Default")
      (node (ref "C27") (pin "1") (pinfunction "1_1") (pintype "passive"))
      (node (ref "D16") (pin "C") (pinfunction "C_C") (pintype "passive"))
      (node (ref "R23") (pin "1") (pinfunction "1_1") (pintype "passive"))
      (node (ref "R24") (pin "2") (pinfunction "2_2") (pintype "passive"))
      (node (ref "U18") (pin "G") (pinfunction "G_G") (pintype "bidirectional"))
    )
    (net (code "100") (name "Net-(C39-Pad1)") (class "Default")
      (node (ref "C39") (pin "1") (pinfunction "1_1") (pintype "passive"))
      (node (ref "D24") (pin "C") (pinfunction "C_C") (pintype "passive"))
      (node (ref "R35") (pin "1") (pinfunction "1_1") (pintype "passive"))
      (node (ref "R36") (pin "2") (pinfunction "2_2") (pintype "passive"))
      (node (ref "U26") (pin "G") (pinfunction "G_G") (pintype "bidirectional"))
    )
    (net (code "101") (name "Net-(D1-A)") (class "Default")
      (node (ref "D1") (pin "1") (pinfunction "A_1") (pintype "passive"))
      (node (ref "JP1") (pin "1") (pinfunction "1_1") (pintype "passive"))
    )
    (net (code "102") (name "Net-(D9-PadC)") (class "Default")
      (node (ref "D9") (pin "C") (pinfunction "C_C") (pintype "passive"))
      (node (ref "R7") (pin "2") (pinfunction "2_2") (pintype "passive"))
      (node (ref "U6") (pin "P$1") (pinfunction "P$1_P$1") (pintype "bidirectional"))
    )
    (net (code "103") (name "Net-(D13-PadC)") (class "Default")
      (node (ref "D13") (pin "C") (pinfunction "C_C") (pintype "passive"))
      (node (ref "R13") (pin "2") (pinfunction "2_2") (pintype "passive"))
      (node (ref "U10") (pin "P$1") (pinfunction "P$1_P$1") (pintype "bidirectional"))
    )
    (net (code "104") (name "Net-(D17-PadC)") (class "Default")
      (node (ref "D17") (pin "C") (pinfunction "C_C") (pintype "passive"))
      (node (ref "R19") (pin "2") (pinfunction "2_2") (pintype "passive"))
      (node (ref "U15") (pin "P$1") (pinfunction "P$1_P$1") (pintype "bidirectional"))
    )
    (net (code "105") (name "Net-(D25-PadC)") (class "Default")
      (node (ref "D25") (pin "C") (pinfunction "C_C") (pintype "passive"))
      (node (ref "R31") (pin "2") (pinfunction "2_2") (pintype "passive"))
      (node (ref "U23") (pin "P$1") (pinfunction "P$1_P$1") (pintype "bidirectional"))
    )
    (net (code "106") (name "Net-(JP3-+)") (class "Default")
      (node (ref "JP3") (pin "1") (pinfunction "+_1") (pintype "bidirectional"))
      (node (ref "U6") (pin "P$3") (pinfunction "P$3_P$3") (pintype "bidirectional"))
      (node (ref "U7") (pin "P$3") (pinfunction "P$3_P$3") (pintype "bidirectional"))
    )
    (net (code "107") (name "Net-(JP3--)") (class "Default")
      (node (ref "JP3") (pin "2") (pinfunction "-_2") (pintype "bidirectional"))
      (node (ref "R11") (pin "2") (pinfunction "2_2") (pintype "passive"))
      (node (ref "U6") (pin "P$4") (pinfunction "P$4_P$4") (pintype "bidirectional"))
      (node (ref "U7") (pin "P$4") (pinfunction "P$4_P$4") (pintype "bidirectional"))
    )
    (net (code "108") (name "Net-(JP4-+)") (class "Default")
      (node (ref "JP4") (pin "1") (pinfunction "+_1") (pintype "bidirectional"))
      (node (ref "U10") (pin "P$3") (pinfunction "P$3_P$3") (pintype "bidirectional"))
      (node (ref "U11") (pin "P$3") (pinfunction "P$3_P$3") (pintype "bidirectional"))
    )
    (net (code "109") (name "Net-(JP4--)") (class "Default")
      (node (ref "JP4") (pin "2") (pinfunction "-_2") (pintype "bidirectional"))
      (node (ref "R17") (pin "2") (pinfunction "2_2") (pintype "passive"))
      (node (ref "U10") (pin "P$4") (pinfunction "P$4_P$4") (pintype "bidirectional"))
      (node (ref "U11") (pin "P$4") (pinfunction "P$4_P$4") (pintype "bidirectional"))
    )
    (net (code "110") (name "Net-(JP9-+)") (class "Default")
      (node (ref "JP9") (pin "1") (pinfunction "+_1") (pintype "bidirectional"))
      (node (ref "U15") (pin "P$3") (pinfunction "P$3_P$3") (pintype "bidirectional"))
      (node (ref "U16") (pin "P$3") (pinfunction "P$3_P$3") (pintype "bidirectional"))
    )
    (net (code "111") (name "Net-(JP9--)") (class "Default")
      (node (ref "JP9") (pin "2") (pinfunction "-_2") (pintype "bidirectional"))
      (node (ref "R23") (pin "2") (pinfunction "2_2") (pintype "passive"))
      (node (ref "U15") (pin "P$4") (pinfunction "P$4_P$4") (pintype "bidirectional"))
      (node (ref "U16") (pin "P$4") (pinfunction "P$4_P$4") (pintype "bidirectional"))
    )
    (net (code "112") (name "Net-(JP11-+)") (class "Default")
      (node (ref "JP11") (pin "1") (pinfunction "+_1") (pintype "bidirectional"))
      (node (ref "U23") (pin "P$3") (pinfunction "P$3_P$3") (pintype "bidirectional"))
      (node (ref "U24") (pin "P$3") (pinfunction "P$3_P$3") (pintype "bidirectional"))
    )
    (net (code "113") (name "Net-(JP11--)") (class "Default")
      (node (ref "JP11") (pin "2") (pinfunction "-_2") (pintype "bidirectional"))
      (node (ref "R35") (pin "2") (pinfunction "2_2") (pintype "passive"))
      (node (ref "U23") (pin "P$4") (pinfunction "P$4_P$4") (pintype "bidirectional"))
      (node (ref "U24") (pin "P$4") (pinfunction "P$4_P$4") (pintype "bidirectional"))
    )
    (net (code "114") (name "Net-(LED1-PadA)") (class "Default")
      (node (ref "LED1") (pin "A") (pinfunction "A_A") (pintype "passive"))
      (node (ref "R73") (pin "2") (pinfunction "2_2") (pintype "passive"))
    )
    (net (code "115") (name "Net-(LED2-PadA)") (class "Default")
      (node (ref "LED2") (pin "A") (pinfunction "A_A") (pintype "passive"))
      (node (ref "R72") (pin "2") (pinfunction "2_2") (pintype "passive"))
    )
    (net (code "116") (name "Net-(LED3-PadA)") (class "Default")
      (node (ref "LED3") (pin "A") (pinfunction "A_A") (pintype "passive"))
      (node (ref "R74") (pin "2") (pinfunction "2_2") (pintype "passive"))
    )
    (net (code "117") (name "Net-(LED4-PadA)") (class "Default")
      (node (ref "LED4") (pin "A") (pinfunction "A_A") (pintype "passive"))
      (node (ref "R75") (pin "2") (pinfunction "2_2") (pintype "passive"))
    )
    (net (code "118") (name "Net-(U1-(SCL3{slash}SCK3{slash}TX1)~{D42})") (class "Default")
      (node (ref "R72") (pin "1") (pinfunction "1_1") (pintype "passive"))
      (node (ref "U1") (pin "~D42") (pinfunction "(SCL3/SCK3/TX1)~{D42}_~D42") (pintype "bidirectional"))
    )
    (net (code "119") (name "Net-(U1-(SDA3{slash}SDI3{slash}RX1)~{D43})") (class "Default")
      (node (ref "R73") (pin "1") (pinfunction "1_1") (pintype "passive"))
      (node (ref "U1") (pin "~D43") (pinfunction "(SDA3/SDI3/RX1)~{D43}_~D43") (pintype "bidirectional"))
    )
    (net (code "120") (name "Net-(U1-(SDO3{slash}RX1)D38)") (class "Default")
      (node (ref "SW3") (pin "P$1") (pinfunction "P$1_P$1") (pintype "bidirectional"))
      (node (ref "SW3") (pin "P$2") (pinfunction "P$2_P$2") (pintype "bidirectional"))
      (node (ref "U1") (pin "D38") (pinfunction "(SDO3/RX1)D38_D38") (pintype "bidirectional"))
    )
    (net (code "121") (name "Net-(U1-(SDO4)~{D44})") (class "Default")
      (node (ref "R74") (pin "1") (pinfunction "1_1") (pintype "passive"))
      (node (ref "U1") (pin "~D44") (pinfunction "(SDO4)~{D44}_~D44") (pintype "bidirectional"))
    )
    (net (code "122") (name "Net-(U1-(TX1{slash}PDMCLK{slash}SCCIO)~{D37})") (class "Default")
      (node (ref "SW2") (pin "P$1") (pinfunction "P$1_P$1") (pintype "bidirectional"))
      (node (ref "SW2") (pin "P$2") (pinfunction "P$2_P$2") (pintype "bidirectional"))
      (node (ref "U1") (pin "~D37") (pinfunction "(TX1/PDMCLK/SCCIO)~{D37}_~D37") (pintype "bidirectional"))
    )
    (net (code "123") (name "Net-(U2-RXD)") (class "Default")
      (node (ref "U2") (pin "25") (pinfunction "RXD_25") (pintype "input"))
      (node (ref "U21") (pin "3") (pinfunction "A_3") (pintype "bidirectional"))
    )
    (net (code "124") (name "Net-(U2-TXD)") (class "Default")
      (node (ref "U2") (pin "26") (pinfunction "TXD_26") (pintype "output"))
      (node (ref "U3") (pin "3") (pinfunction "A_3") (pintype "bidirectional"))
    )
    (net (code "125") (name "Net-(U2-~{SUSPEND})") (class "Default")
      (node (ref "LED4") (pin "C") (pinfunction "C_C") (pintype "passive"))
      (node (ref "U2") (pin "11") (pinfunction "~{SUSPEND}_11") (pintype "output"))
    )
    (net (code "126") (name "Net-(U3-B)") (class "Default")
      (node (ref "JP15") (pin "2") (pinfunction "2_2") (pintype "passive"))
      (node (ref "U3") (pin "4") (pinfunction "B_4") (pintype "bidirectional"))
    )
    (net (code "127") (name "Net-(U8-OUT)") (class "Default")
      (node (ref "R10") (pin "2") (pinfunction "2_2") (pintype "passive"))
      (node (ref "U8") (pin "3") (pinfunction "OUT_3") (pintype "bidirectional"))
    )
    (net (code "128") (name "Net-(U8-RS+)") (class "Default")
      (node (ref "R9") (pin "1") (pinfunction "1_1") (pintype "passive"))
      (node (ref "U7") (pin "P$1") (pinfunction "P$1_P$1") (pintype "bidirectional"))
      (node (ref "U8") (pin "5") (pinfunction "RS+_5") (pintype "bidirectional"))
    )
    (net (code "129") (name "Net-(U12-OUT)") (class "Default")
      (node (ref "R16") (pin "2") (pinfunction "2_2") (pintype "passive"))
      (node (ref "U12") (pin "3") (pinfunction "OUT_3") (pintype "bidirectional"))
    )
    (net (code "130") (name "Net-(U12-RS+)") (class "Default")
      (node (ref "R15") (pin "1") (pinfunction "1_1") (pintype "passive"))
      (node (ref "U11") (pin "P$1") (pinfunction "P$1_P$1") (pintype "bidirectional"))
      (node (ref "U12") (pin "5") (pinfunction "RS+_5") (pintype "bidirectional"))
    )
    (net (code "131") (name "Net-(U17-OUT)") (class "Default")
      (node (ref "R22") (pin "2") (pinfunction "2_2") (pintype "passive"))
      (node (ref "U17") (pin "3") (pinfunction "OUT_3") (pintype "bidirectional"))
    )
    (net (code "132") (name "Net-(U17-RS+)") (class "Default")
      (node (ref "R21") (pin "1") (pinfunction "1_1") (pintype "passive"))
      (node (ref "U16") (pin "P$1") (pinfunction "P$1_P$1") (pintype "bidirectional"))
      (node (ref "U17") (pin "5") (pinfunction "RS+_5") (pintype "bidirectional"))
    )
    (net (code "133") (name "Net-(U21-B)") (class "Default")
      (node (ref "JP16") (pin "2") (pinfunction "2_2") (pintype "passive"))
      (node (ref "U21") (pin "4") (pinfunction "B_4") (pintype "bidirectional"))
    )
    (net (code "134") (name "Net-(U25-OUT)") (class "Default")
      (node (ref "R34") (pin "2") (pinfunction "2_2") (pintype "passive"))
      (node (ref "U25") (pin "3") (pinfunction "OUT_3") (pintype "bidirectional"))
    )
    (net (code "135") (name "Net-(U25-RS+)") (class "Default")
      (node (ref "R33") (pin "1") (pinfunction "1_1") (pintype "passive"))
      (node (ref "U24") (pin "P$1") (pinfunction "P$1_P$1") (pintype "bidirectional"))
      (node (ref "U25") (pin "5") (pinfunction "RS+_5") (pintype "bidirectional"))
    )
    (net (code "136") (name "Net-(U29-FB)") (class "Default")
      (node (ref "C47") (pin "2") (pinfunction "2_2") (pintype "passive"))
      (node (ref "R3") (pin "1") (pinfunction "1_1") (pintype "passive"))
      (node (ref "R4") (pin "2") (pinfunction "2_2") (pintype "passive"))
      (node (ref "U29") (pin "5") (pinfunction "FB_5") (pintype "bidirectional"))
    )
    (net (code "137") (name "Net-(U29-SW)") (class "Default")
      (node (ref "L1") (pin "P$1") (pinfunction "P$1_P$1") (pintype "bidirectional"))
      (node (ref "U29") (pin "7") (pinfunction "SW_7") (pintype "bidirectional"))
    )
    (net (code "138") (name "SENSE_MUX_A0") (class "Default")
      (node (ref "U1") (pin "D10") (pinfunction "(SDO1/TX1/PDMCLK)D10_D10") (pintype "bidirectional"))
      (node (ref "U22") (pin "1") (pinfunction "A0_1") (pintype "bidirectional"))
      (node (ref "U27") (pin "1") (pinfunction "A0_1") (pintype "bidirectional"))
      (node (ref "U28") (pin "1") (pinfunction "A0_1") (pintype "bidirectional"))
      (node (ref "U37") (pin "1") (pinfunction "A0_1") (pintype "bidirectional"))
    )
    (net (code "139") (name "SENSE_MUX_A1") (class "Default")
      (node (ref "U1") (pin "D9") (pinfunction "(SDA1/SDI1/RX1/SCCIO)D9_D9") (pintype "bidirectional"))
      (node (ref "U22") (pin "10") (pinfunction "A1_10") (pintype "bidirectional"))
      (node (ref "U27") (pin "10") (pinfunction "A1_10") (pintype "bidirectional"))
      (node (ref "U28") (pin "10") (pinfunction "A1_10") (pintype "bidirectional"))
      (node (ref "U37") (pin "10") (pinfunction "A1_10") (pintype "bidirectional"))
    )
    (net (code "140") (name "SENSE_MUX_EN") (class "Default")
      (node (ref "U1") (pin "D8") (pinfunction "(SCL1/SCK1/TX1/SCCLK)D8_D8") (pintype "bidirectional"))
      (node (ref "U22") (pin "5") (pinfunction "EN_5") (pintype "bidirectional"))
      (node (ref "U27") (pin "5") (pinfunction "EN_5") (pintype "bidirectional"))
      (node (ref "U28") (pin "5") (pinfunction "EN_5") (pintype "bidirectional"))
      (node (ref "U37") (pin "5") (pinfunction "EN_5") (pintype "bidirectional"))
    )
    (net (code "141") (name "SWDCK") (class "Default")
      (node (ref "J2") (pin "P$4") (pinfunction "P$4_P$4") (pintype "bidirectional"))
      (node (ref "U1") (pin "SWDCK") (pinfunction "D20(SWDCK/TX1)_SWDCK") (pintype "bidirectional"))
    )
    (net (code "142") (name "SWDIO") (class "Default")
      (node (ref "J2") (pin "P$2") (pinfunction "P$2_P$2") (pintype "bidirectional"))
      (node (ref "U1") (pin "SWDIO") (pinfunction "D21(SWDIO/RX1/SCCRST)_SWDIO") (pintype "bidirectional"))
    )
    (net (code "143") (name "VCC") (class "Default")
      (node (ref "C43") (pin "1") (pinfunction "1_1") (pintype "passive"))
      (node (ref "C44") (pin "1") (pinfunction "1_1") (pintype "passive"))
      (node (ref "C45") (pin "1") (pinfunction "1_1") (pintype "passive"))
      (node (ref "C47") (pin "1") (pinfunction "1_1") (pintype "passive"))
      (node (ref "C48") (pin "1") (pinfunction "1_1") (pintype "passive"))
      (node (ref "C53") (pin "1") (pinfunction "1_1") (pintype "passive"))
      (node (ref "C54") (pin "1") (pinfunction "1_1") (pintype "passive"))
      (node (ref "C61") (pin "1") (pinfunction "1_1") (pintype "passive"))
      (node (ref "C62") (pin "1") (pinfunction "1_1") (pintype "passive"))
      (node (ref "C63") (pin "1") (pinfunction "1_1") (pintype "passive"))
      (node (ref "J2") (pin "P$1") (pinfunction "P$1_P$1") (pintype "bidirectional"))
      (node (ref "JP17") (pin "1") (pinfunction "1_1") (pintype "passive"))
      (node (ref "JP7") (pin "2") (pinfunction "2_2") (pintype "passive"))
      (node (ref "JP7") (pin "4") (pinfunction "4_4") (pintype "passive"))
      (node (ref "JP7") (pin "5") (pinfunction "5_5") (pintype "passive"))
      (node (ref "L1") (pin "P$2") (pinfunction "P$2_P$2") (pintype "bidirectional"))
      (node (ref "R3") (pin "2") (pinfunction "2_2") (pintype "passive"))
      (node (ref "R49") (pin "2") (pinfunction "2_2") (pintype "passive"))
      (node (ref "R50") (pin "2") (pinfunction "2_2") (pintype "passive"))
      (node (ref "R51") (pin "2") (pinfunction "2_2") (pintype "passive"))
      (node (ref "R52") (pin "2") (pinfunction "2_2") (pintype "passive"))
      (node (ref "U1") (pin "VDD@36") (pinfunction "VDD*2_VDD@36") (pintype "bidirectional"))
      (node (ref "U1") (pin "VDD@37") (pinfunction "VDD*2_VDD@37") (pintype "bidirectional"))
      (node (ref "U22") (pin "6") (pinfunction "VDD_6") (pintype "bidirectional"))
      (node (ref "U27") (pin "6") (pinfunction "VDD_6") (pintype "bidirectional"))
      (node (ref "U28") (pin "6") (pinfunction "VDD_6") (pintype "bidirectional"))
      (node (ref "U29") (pin "4") (pinfunction "SGND_4") (pintype "bidirectional"))
      (node (ref "U29") (pin "8") (pinfunction "VOUT_8") (pintype "bidirectional"))
      (node (ref "U30") (pin "P$11") (pinfunction "VDD_P$11") (pintype "bidirectional"))
      (node (ref "U34") (pin "P$11") (pinfunction "VDD_P$11") (pintype "bidirectional"))
      (node (ref "U35") (pin "P$11") (pinfunction "VDD_P$11") (pintype "bidirectional"))
      (node (ref "U36") (pin "P$11") (pinfunction "VDD_P$11") (pintype "bidirectional"))
      (node (ref "U37") (pin "6") (pinfunction "VDD_6") (pintype "bidirectional"))
    )
    (net (code "144") (name "VCC_JUMPERED") (class "Default")
      (node (ref "C41") (pin "1") (pinfunction "1_1") (pintype "passive"))
      (node (ref "C42") (pin "1") (pinfunction "1_1") (pintype "passive"))
      (node (ref "JP17") (pin "2") (pinfunction "2_2") (pintype "passive"))
      (node (ref "U21") (pin "6") (pinfunction "VCCB_6") (pintype "bidirectional"))
      (node (ref "U3") (pin "6") (pinfunction "VCCB_6") (pintype "bidirectional"))
    )
    (net (code "145") (name "VHARVEST0") (class "Default")
      (node (ref "C12") (pin "1") (pinfunction "1_1") (pintype "passive"))
      (node (ref "C13") (pin "+") (pinfunction "+_+") (pintype "passive"))
      (node (ref "C14") (pin "1") (pinfunction "1_1") (pintype "passive"))
      (node (ref "D6") (pin "1") (pinfunction "A_1") (pintype "passive"))
      (node (ref "D7") (pin "C") (pinfunction "C_C") (pintype "passive"))
      (node (ref "R6") (pin "2") (pinfunction "2_2") (pintype "passive"))
      (node (ref "R9") (pin "2") (pinfunction "2_2") (pintype "passive"))
      (node (ref "U8") (pin "4") (pinfunction "RS-_4") (pintype "bidirectional"))
    )
    (net (code "146") (name "VHARVEST0_SCALED") (class "Default")
      (node (ref "D3") (pin "C") (pinfunction "C_C") (pintype "passive"))
      (node (ref "R6") (pin "1") (pinfunction "1_1") (pintype "passive"))
      (node (ref "R65") (pin "2") (pinfunction "2_2") (pintype "passive"))
      (node (ref "U28") (pin "2") (pinfunction "S1_2") (pintype "bidirectional"))
    )
    (net (code "147") (name "VHARVEST1") (class "Default")
      (node (ref "C18") (pin "1") (pinfunction "1_1") (pintype "passive"))
      (node (ref "C19") (pin "+") (pinfunction "+_+") (pintype "passive"))
      (node (ref "C20") (pin "1") (pinfunction "1_1") (pintype "passive"))
      (node (ref "D10") (pin "1") (pinfunction "A_1") (pintype "passive"))
      (node (ref "D11") (pin "C") (pinfunction "C_C") (pintype "passive"))
      (node (ref "R15") (pin "2") (pinfunction "2_2") (pintype "passive"))
      (node (ref "R66") (pin "2") (pinfunction "2_2") (pintype "passive"))
      (node (ref "U12") (pin "4") (pinfunction "RS-_4") (pintype "bidirectional"))
    )
    (net (code "148") (name "VHARVEST1_SCALED") (class "Default")
      (node (ref "D30") (pin "C") (pinfunction "C_C") (pintype "passive"))
      (node (ref "R66") (pin "1") (pinfunction "1_1") (pintype "passive"))
      (node (ref "R67") (pin "2") (pinfunction "2_2") (pintype "passive"))
      (node (ref "U28") (pin "9") (pinfunction "S2_9") (pintype "bidirectional"))
    )
    (net (code "149") (name "VHARVEST2") (class "Default")
      (node (ref "C24") (pin "1") (pinfunction "1_1") (pintype "passive"))
      (node (ref "C25") (pin "+") (pinfunction "+_+") (pintype "passive"))
      (node (ref "C26") (pin "1") (pinfunction "1_1") (pintype "passive"))
      (node (ref "D14") (pin "1") (pinfunction "A_1") (pintype "passive"))
      (node (ref "D15") (pin "C") (pinfunction "C_C") (pintype "passive"))
      (node (ref "R21") (pin "2") (pinfunction "2_2") (pintype "passive"))
      (node (ref "R68") (pin "2") (pinfunction "2_2") (pintype "passive"))
      (node (ref "U17") (pin "4") (pinfunction "RS-_4") (pintype "bidirectional"))
    )
    (net (code "150") (name "VHARVEST2_SCALED") (class "Default")
      (node (ref "D37") (pin "C") (pinfunction "C_C") (pintype "passive"))
      (node (ref "R68") (pin "1") (pinfunction "1_1") (pintype "passive"))
      (node (ref "R69") (pin "2") (pinfunction "2_2") (pintype "passive"))
      (node (ref "U28") (pin "4") (pinfunction "S3_4") (pintype "bidirectional"))
    )
    (net (code "151") (name "VHARVEST3") (class "Default")
      (node (ref "C36") (pin "1") (pinfunction "1_1") (pintype "passive"))
      (node (ref "C37") (pin "+") (pinfunction "+_+") (pintype "passive"))
      (node (ref "C38") (pin "1") (pinfunction "1_1") (pintype "passive"))
      (node (ref "D22") (pin "1") (pinfunction "A_1") (pintype "passive"))
      (node (ref "D23") (pin "C") (pinfunction "C_C") (pintype "passive"))
      (node (ref "R33") (pin "2") (pinfunction "2_2") (pintype "passive"))
      (node (ref "R70") (pin "2") (pinfunction "2_2") (pintype "passive"))
      (node (ref "U25") (pin "4") (pinfunction "RS-_4") (pintype "bidirectional"))
    )
    (net (code "152") (name "VHARVEST3_SCALED") (class "Default")
      (node (ref "D38") (pin "C") (pinfunction "C_C") (pintype "passive"))
      (node (ref "R70") (pin "1") (pinfunction "1_1") (pintype "passive"))
      (node (ref "R71") (pin "2") (pinfunction "2_2") (pintype "passive"))
      (node (ref "U28") (pin "7") (pinfunction "S4_7") (pintype "bidirectional"))
    )
    (net (code "153") (name "VHARVEST_MUX_D") (class "Default")
      (node (ref "U1") (pin "~AD32") (pinfunction "~{AD32(SCCIO})_~AD32") (pintype "bidirectional"))
      (node (ref "U28") (pin "8") (pinfunction "D_8") (pintype "bidirectional"))
    )
    (net (code "154") (name "VHARVEST_OR") (class "Default")
      (node (ref "C46") (pin "1") (pinfunction "1_1") (pintype "passive"))
      (node (ref "C49") (pin "1") (pinfunction "1_1") (pintype "passive"))
      (node (ref "D1") (pin "3") (pinfunction "C_3") (pintype "passive"))
      (node (ref "D10") (pin "3") (pinfunction "C_3") (pintype "passive"))
      (node (ref "D14") (pin "3") (pinfunction "C_3") (pintype "passive"))
      (node (ref "D22") (pin "3") (pinfunction "C_3") (pintype "passive"))
      (node (ref "D6") (pin "3") (pinfunction "C_3") (pintype "passive"))
      (node (ref "JP21") (pin "1") (pinfunction "1_1") (pintype "passive"))
      (node (ref "JP21") (pin "2") (pinfunction "2_2") (pintype "passive"))
      (node (ref "JP7") (pin "8") (pinfunction "8_8") (pintype "passive"))
      (node (ref "U14") (pin "P$1") (pinfunction "P$1_P$1") (pintype "bidirectional"))
      (node (ref "U19") (pin "P$1") (pinfunction "P$1_P$1") (pintype "bidirectional"))
      (node (ref "U20") (pin "P$1") (pinfunction "P$1_P$1") (pintype "bidirectional"))
      (node (ref "U29") (pin "1") (pinfunction "VIN_1") (pintype "bidirectional"))
      (node (ref "U29") (pin "3") (pinfunction "EN_3") (pintype "bidirectional"))
      (node (ref "U31") (pin "P$1") (pinfunction "P$1_P$1") (pintype "bidirectional"))
      (node (ref "U32") (pin "P$1") (pinfunction "P$1_P$1") (pintype "bidirectional"))
      (node (ref "U33") (pin "P$1") (pinfunction "P$1_P$1") (pintype "bidirectional"))
      (node (ref "U4") (pin "P$1") (pinfunction "P$1_P$1") (pintype "bidirectional"))
      (node (ref "U5") (pin "P$1") (pinfunction "P$1_P$1") (pintype "bidirectional"))
    )
    (net (code "155") (name "VSENSE0") (class "Default")
      (node (ref "C10") (pin "1") (pinfunction "1_1") (pintype "passive"))
      (node (ref "R7") (pin "1") (pinfunction "1_1") (pintype "passive"))
      (node (ref "R8") (pin "2") (pinfunction "2_2") (pintype "passive"))
      (node (ref "U22") (pin "2") (pinfunction "S1_2") (pintype "bidirectional"))
    )
    (net (code "156") (name "VSENSE1") (class "Default")
      (node (ref "C16") (pin "1") (pinfunction "1_1") (pintype "passive"))
      (node (ref "R13") (pin "1") (pinfunction "1_1") (pintype "passive"))
      (node (ref "R14") (pin "2") (pinfunction "2_2") (pintype "passive"))
      (node (ref "U22") (pin "9") (pinfunction "S2_9") (pintype "bidirectional"))
    )
    (net (code "157") (name "VSENSE2") (class "Default")
      (node (ref "C22") (pin "1") (pinfunction "1_1") (pintype "passive"))
      (node (ref "R19") (pin "1") (pinfunction "1_1") (pintype "passive"))
      (node (ref "R20") (pin "2") (pinfunction "2_2") (pintype "passive"))
      (node (ref "U22") (pin "4") (pinfunction "S3_4") (pintype "bidirectional"))
    )
    (net (code "158") (name "VSENSE3") (class "Default")
      (node (ref "C34") (pin "1") (pinfunction "1_1") (pintype "passive"))
      (node (ref "R31") (pin "1") (pinfunction "1_1") (pintype "passive"))
      (node (ref "R32") (pin "2") (pinfunction "2_2") (pintype "passive"))
      (node (ref "U22") (pin "7") (pinfunction "S4_7") (pintype "bidirectional"))
    )
    (net (code "159") (name "VSENSE_MUX_D") (class "Default")
      (node (ref "U1") (pin "~AD12") (pinfunction "~{AD12(PDMCLK/TX1})_~AD12") (pintype "bidirectional"))
      (node (ref "U22") (pin "8") (pinfunction "D_8") (pintype "bidirectional"))
    )
    (net (code "160") (name "VUSB") (class "Default")
      (node (ref "C1") (pin "1") (pinfunction "1_1") (pintype "passive"))
      (node (ref "C2") (pin "1") (pinfunction "1_1") (pintype "passive"))
      (node (ref "J1") (pin "1") (pinfunction "1_1") (pintype "power_in"))
      (node (ref "JP1") (pin "2") (pinfunction "2_2") (pintype "passive"))
      (node (ref "TVS1") (pin "P$6") (pinfunction "DVBUS_P$6") (pintype "bidirectional"))
      (node (ref "U2") (pin "7") (pinfunction "REGIN_7") (pintype "passive"))
      (node (ref "U2") (pin "8") (pinfunction "VBUS_8") (pintype "input"))
    )
    (net (code "161") (name "unconnected-(J1-Pad4)") (class "Default")
      (node (ref "J1") (pin "4") (pinfunction "4_4") (pintype "bidirectional"))
    )
    (net (code "162") (name "unconnected-(J2-PadP$8)") (class "Default")
      (node (ref "J2") (pin "P$8") (pinfunction "P$8_P$8") (pintype "bidirectional"))
    )
    (net (code "163") (name "unconnected-(JP5-Pad3)") (class "Default")
      (node (ref "JP5") (pin "3") (pinfunction "3_3") (pintype "passive"))
    )
    (net (code "164") (name "unconnected-(JP7-Pad1)") (class "Default")
      (node (ref "JP7") (pin "1") (pinfunction "1_1") (pintype "passive"))
    )
    (net (code "165") (name "unconnected-(TVS1-D3-PadP$3)") (class "Default")
      (node (ref "TVS1") (pin "P$3") (pinfunction "D3_P$3") (pintype "bidirectional"))
    )
    (net (code "166") (name "unconnected-(TVS1-NC-PadP$4)") (class "Default")
      (node (ref "TVS1") (pin "P$4") (pinfunction "NC_P$4") (pintype "bidirectional"))
    )
    (net (code "167") (name "unconnected-(TVS1-NC-PadP$5)") (class "Default")
      (node (ref "TVS1") (pin "P$5") (pinfunction "NC_P$5") (pintype "bidirectional"))
    )
    (net (code "168") (name "unconnected-(U1-(ADCD1P{slash}TX1{slash}PDMCLK)D14-PadD14)") (class "Default")
      (node (ref "U1") (pin "D14") (pinfunction "(ADCD1P/TX1/PDMCLK)D14_D14") (pintype "bidirectional"))
    )
    (net (code "169") (name "unconnected-(U1-PadXI)") (class "Default")
      (node (ref "U1") (pin "XI") (pinfunction "XI_XI") (pintype "bidirectional"))
    )
    (net (code "170") (name "unconnected-(U1-PadXO)") (class "Default")
      (node (ref "U1") (pin "XO") (pinfunction "XO_XO") (pintype "bidirectional"))
    )
    (net (code "171") (name "unconnected-(U2-CTS-Pad23)") (class "Default")
      (node (ref "U2") (pin "23") (pinfunction "CTS_23") (pintype "input"))
    )
    (net (code "172") (name "unconnected-(U2-DCD-Pad1)") (class "Default")
      (node (ref "U2") (pin "1") (pinfunction "DCD_1") (pintype "input"))
    )
    (net (code "173") (name "unconnected-(U2-DSR-Pad27)") (class "Default")
      (node (ref "U2") (pin "27") (pinfunction "DSR_27") (pintype "input"))
    )
    (net (code "174") (name "unconnected-(U2-DTR-Pad28)") (class "Default")
      (node (ref "U2") (pin "28") (pinfunction "DTR_28") (pintype "output"))
    )
    (net (code "175") (name "unconnected-(U2-RI-Pad2)") (class "Default")
      (node (ref "U2") (pin "2") (pinfunction "RI_2") (pintype "input"))
    )
    (net (code "176") (name "unconnected-(U2-SUSPEND-Pad12)") (class "Default")
      (node (ref "U2") (pin "12") (pinfunction "SUSPEND_12") (pintype "output"))
    )
    (net (code "177") (name "unconnected-(U2-~{RST}-Pad9)") (class "Default")
      (node (ref "U2") (pin "9") (pinfunction "~{RST}_9") (pintype "bidirectional"))
    )
    (net (code "178") (name "unconnected-(U29-PG-Pad6)") (class "Default")
      (node (ref "U29") (pin "6") (pinfunction "PG_6") (pintype "bidirectional"))
    )
    (net (code "179") (name "~{D0{slash}RXI-1}") (class "Default")
      (node (ref "JP2") (pin "8") (pinfunction "8_8") (pintype "passive"))
      (node (ref "U1") (pin "~D25") (pinfunction "(SDA2/SDI2/RX1)~{D25}_~D25") (pintype "bidirectional"))
    )
    (net (code "180") (name "~{D1{slash}TXO-1}") (class "Default")
      (node (ref "JP2") (pin "7") (pinfunction "7_7") (pintype "passive"))
      (node (ref "U1") (pin "~D24") (pinfunction "(TX1/32KHZ/SWO)~{D24}_~D24") (pintype "bidirectional"))
    )
    (net (code "181") (name "~{D2{slash}A6}") (class "Default")
      (node (ref "JP2") (pin "6") (pinfunction "6_6") (pintype "passive"))
      (node (ref "U1") (pin "~AD35") (pinfunction "~{AD35(TX1/I2SDAT/PDMCLK})_~AD35") (pintype "bidirectional"))
    )
    (net (code "182") (name "~{D3}") (class "Default")
      (node (ref "JP2") (pin "5") (pinfunction "5_5") (pintype "passive"))
      (node (ref "U1") (pin "~D4") (pinfunction "(RX1/SLINT)~{D4}_~D4") (pintype "bidirectional"))
    )
    (net (code "183") (name "~{D4}") (class "Default")
      (node (ref "JP2") (pin "4") (pinfunction "4_4") (pintype "passive"))
      (node (ref "U1") (pin "~D22") (pinfunction "(PDMCLK/SWO)~{D22}_~D22") (pintype "bidirectional"))
    )
    (net (code "184") (name "~{D5}") (class "Default")
      (node (ref "JP2") (pin "3") (pinfunction "3_3") (pintype "passive"))
      (node (ref "U1") (pin "~D23") (pinfunction "(I2SWCLK/CMPOUT)~{D23}_~D23") (pintype "bidirectional"))
    )
    (net (code "185") (name "~{D6}") (class "Default")
      (node (ref "JP2") (pin "2") (pinfunction "2_2") (pintype "passive"))
      (node (ref "U1") (pin "~D27") (pinfunction "(SCL2/SCK2)~{D27}_~D27") (pintype "bidirectional"))
    )
    (net (code "186") (name "~{D7}") (class "Default")
      (node (ref "JP2") (pin "1") (pinfunction "1_1") (pintype "passive"))
      (node (ref "U1") (pin "~D28") (pinfunction "(SDO2/I2SWCLK)~{D28}_~D28") (pintype "bidirectional"))
    )
    (net (code "187") (name "~{D8}") (class "Default")
      (node (ref "JP5") (pin "10") (pinfunction "10_10") (pintype "passive"))
      (node (ref "U1") (pin "~D19") (pinfunction "(CMPRF0/SCCCLK/I2SBCLK)~{D19}_~D19") (pintype "bidirectional"))
    )
    (net (code "188") (name "~{D9}") (class "Default")
      (node (ref "JP5") (pin "9") (pinfunction "9_9") (pintype "passive"))
      (node (ref "U1") (pin "~D26") (pinfunction "(SCCRST)~{D26}_~D26") (pintype "bidirectional"))
    )
    (net (code "189") (name "~{D10}") (class "Default")
      (node (ref "JP5") (pin "8") (pinfunction "8_8") (pintype "passive"))
      (node (ref "U1") (pin "D36") (pinfunction "(RX1/TRIG1/PDMDATA)D36_D36") (pintype "bidirectional"))
    )
    (net (code "190") (name "~{D11{slash}COPI}") (class "Default")
      (node (ref "JP5") (pin "7") (pinfunction "7_7") (pintype "passive"))
      (node (ref "U1") (pin "D7") (pinfunction "(SDO0/CLKOUT)~{D7}_D7") (pintype "bidirectional"))
    )
    (net (code "191") (name "~{D12{slash}CIPO}") (class "Default")
      (node (ref "JP5") (pin "6") (pinfunction "6_6") (pintype "passive"))
      (node (ref "U1") (pin "~D6") (pinfunction "(SDA0/SDI0/I2SDAT)~{D6}_~D6") (pintype "bidirectional"))
    )
    (net (code "192") (name "~{D13{slash}SCK}") (class "Default")
      (node (ref "JP5") (pin "5") (pinfunction "5_5") (pintype "passive"))
      (node (ref "U1") (pin "~D5") (pinfunction "(SCL0/SCK0)~{D5}_~D5") (pintype "bidirectional"))
    )
    (net (code "193") (name "~{D15{slash}SCL}") (class "Default")
      (node (ref "JP5") (pin "1") (pinfunction "1_1") (pintype "passive"))
      (node (ref "U1") (pin "~D39") (pinfunction "(SCL4/SCK4/TX1)~{D39}_~D39") (pintype "bidirectional"))
    )
    (net (code "194") (name "~{RESET}") (class "Default")
      (node (ref "C51") (pin "2") (pinfunction "2_2") (pintype "passive"))
      (node (ref "C52") (pin "1") (pinfunction "1_1") (pintype "passive"))
      (node (ref "J2") (pin "P$10") (pinfunction "P$10_P$10") (pintype "bidirectional"))
      (node (ref "JP7") (pin "3") (pinfunction "3_3") (pintype "passive"))
      (node (ref "R49") (pin "1") (pinfunction "1_1") (pintype "passive"))
      (node (ref "SW1") (pin "P$3") (pinfunction "P$3_P$3") (pintype "bidirectional"))
      (node (ref "SW1") (pin "P$4") (pinfunction "P$4_P$4") (pintype "bidirectional"))
      (node (ref "U1") (pin "~RST") (pinfunction "~{RST}_~RST") (pintype "bidirectional"))
    )
    (net (code "195") (name "~{RTS}") (class "Default")
      (node (ref "C50") (pin "1") (pinfunction "1_1") (pintype "passive"))
      (node (ref "C51") (pin "1") (pinfunction "1_1") (pintype "passive"))
      (node (ref "U2") (pin "24") (pinfunction "RTS_24") (pintype "output"))
    )
  )
)
